# VNA.net
KiCad netlist of a schematic drawn in EAGLE
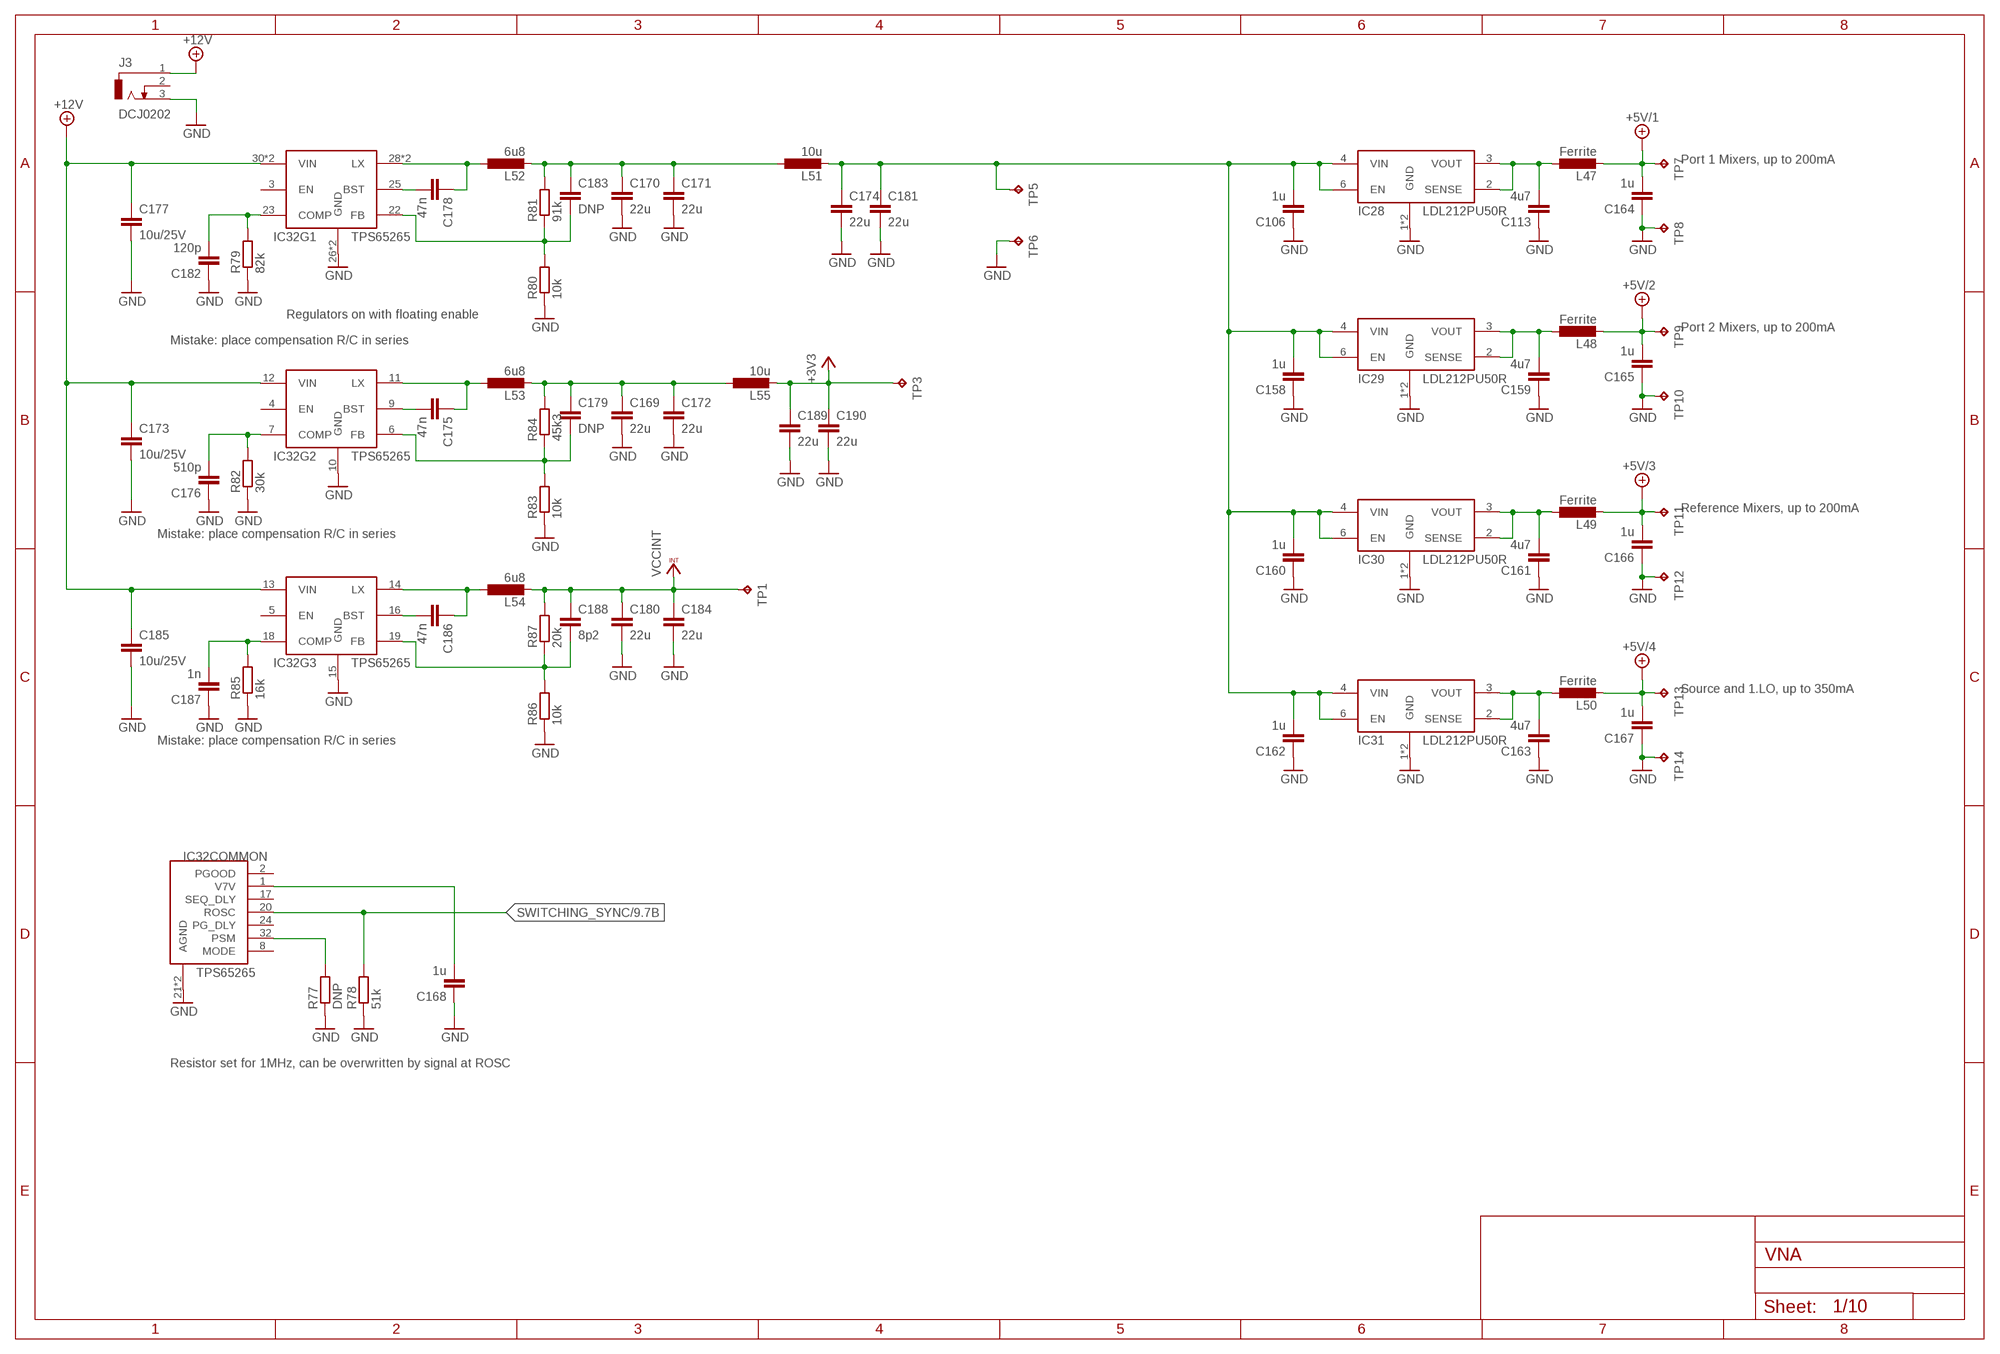
[diagram p0: schematic, sheet 1]
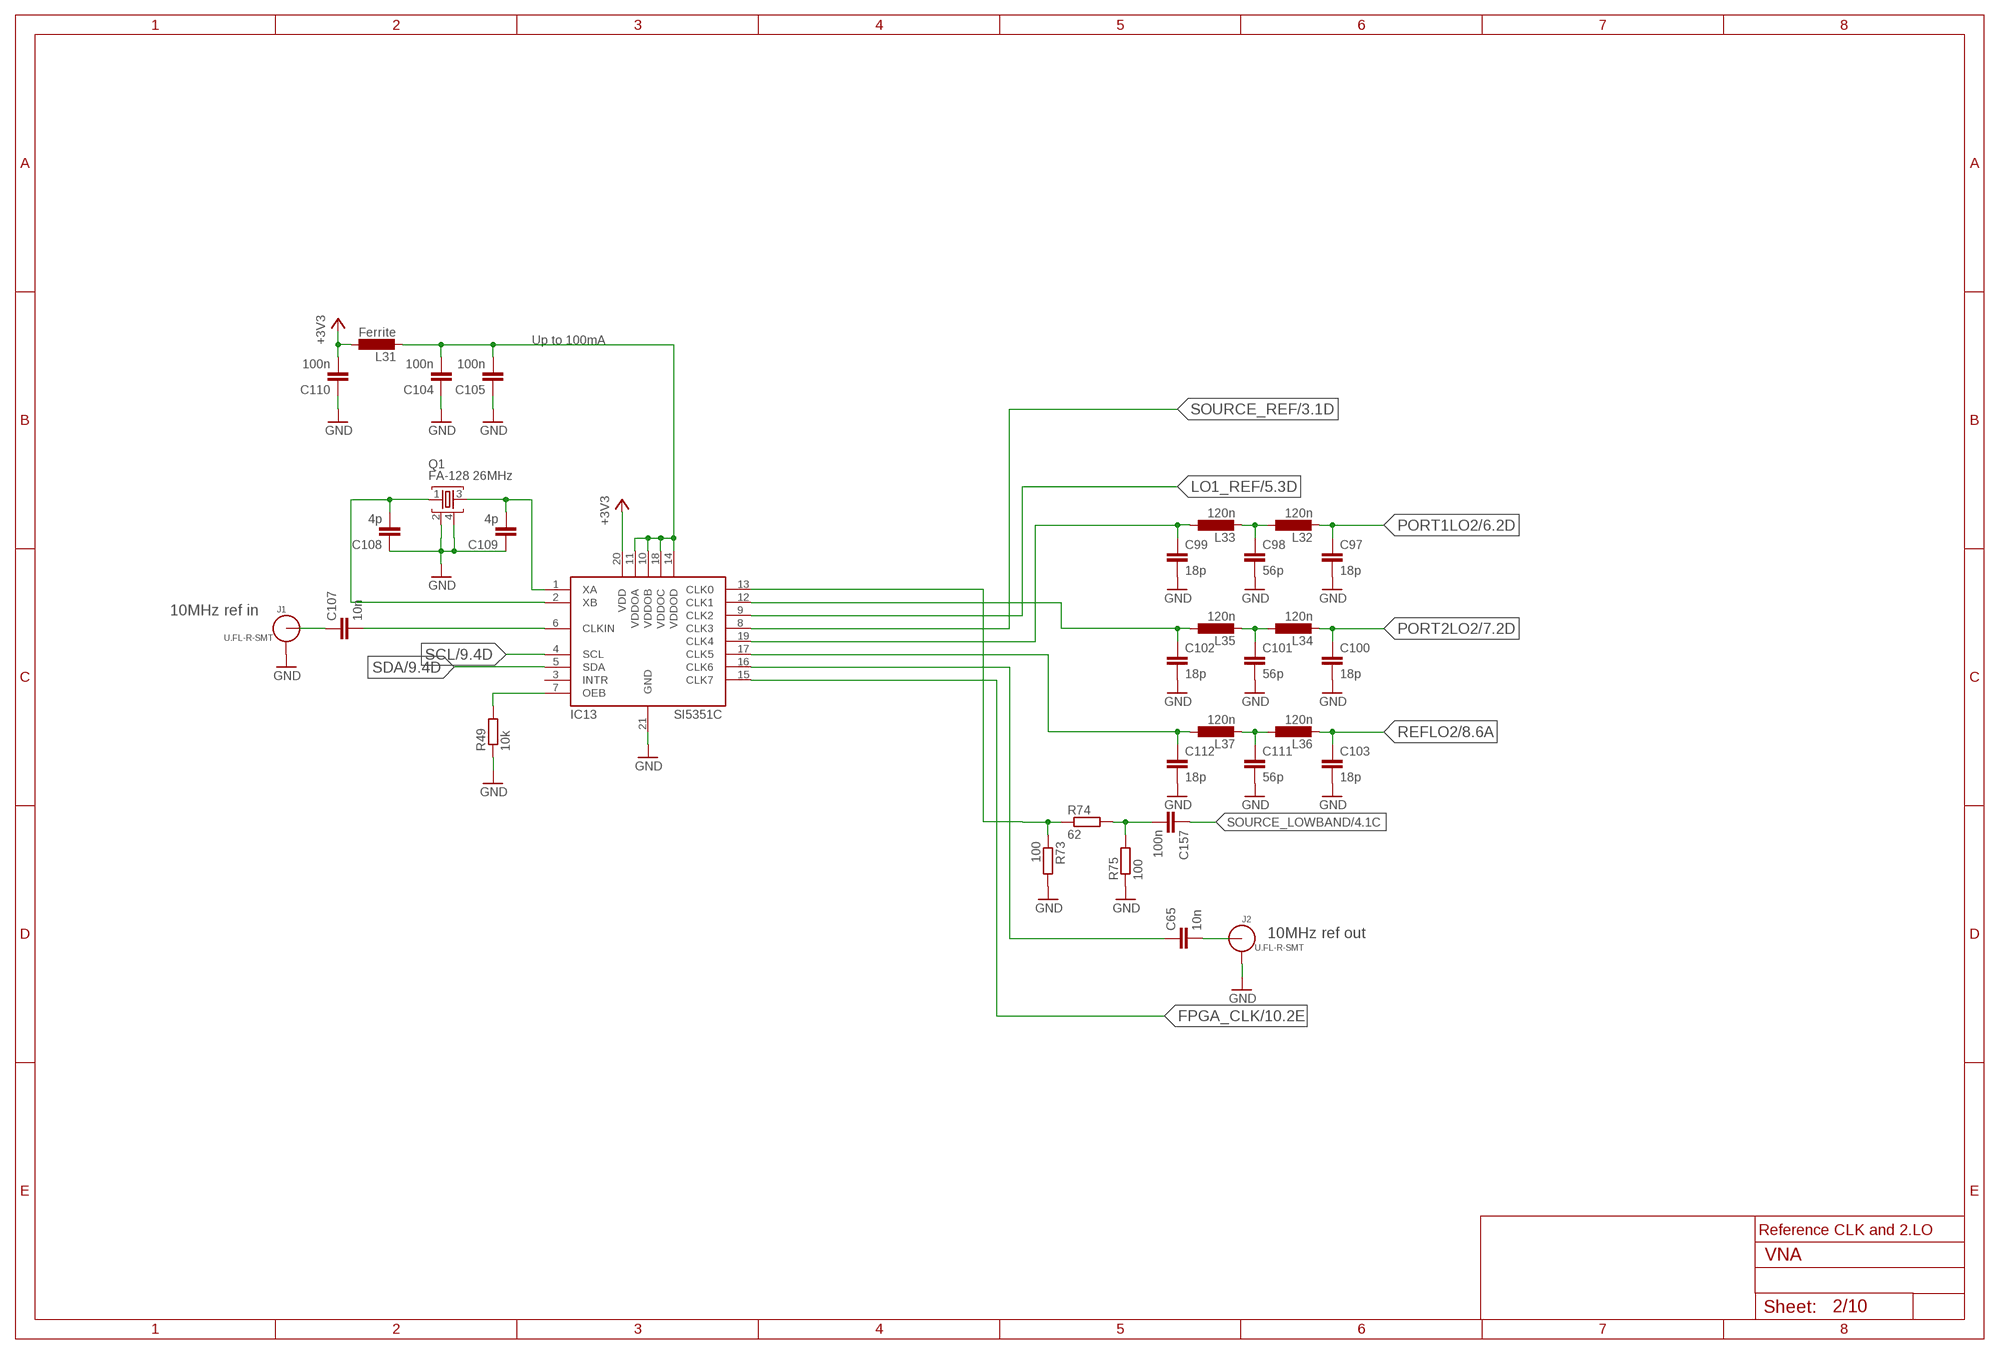
[diagram p1: schematic, sheet 2]
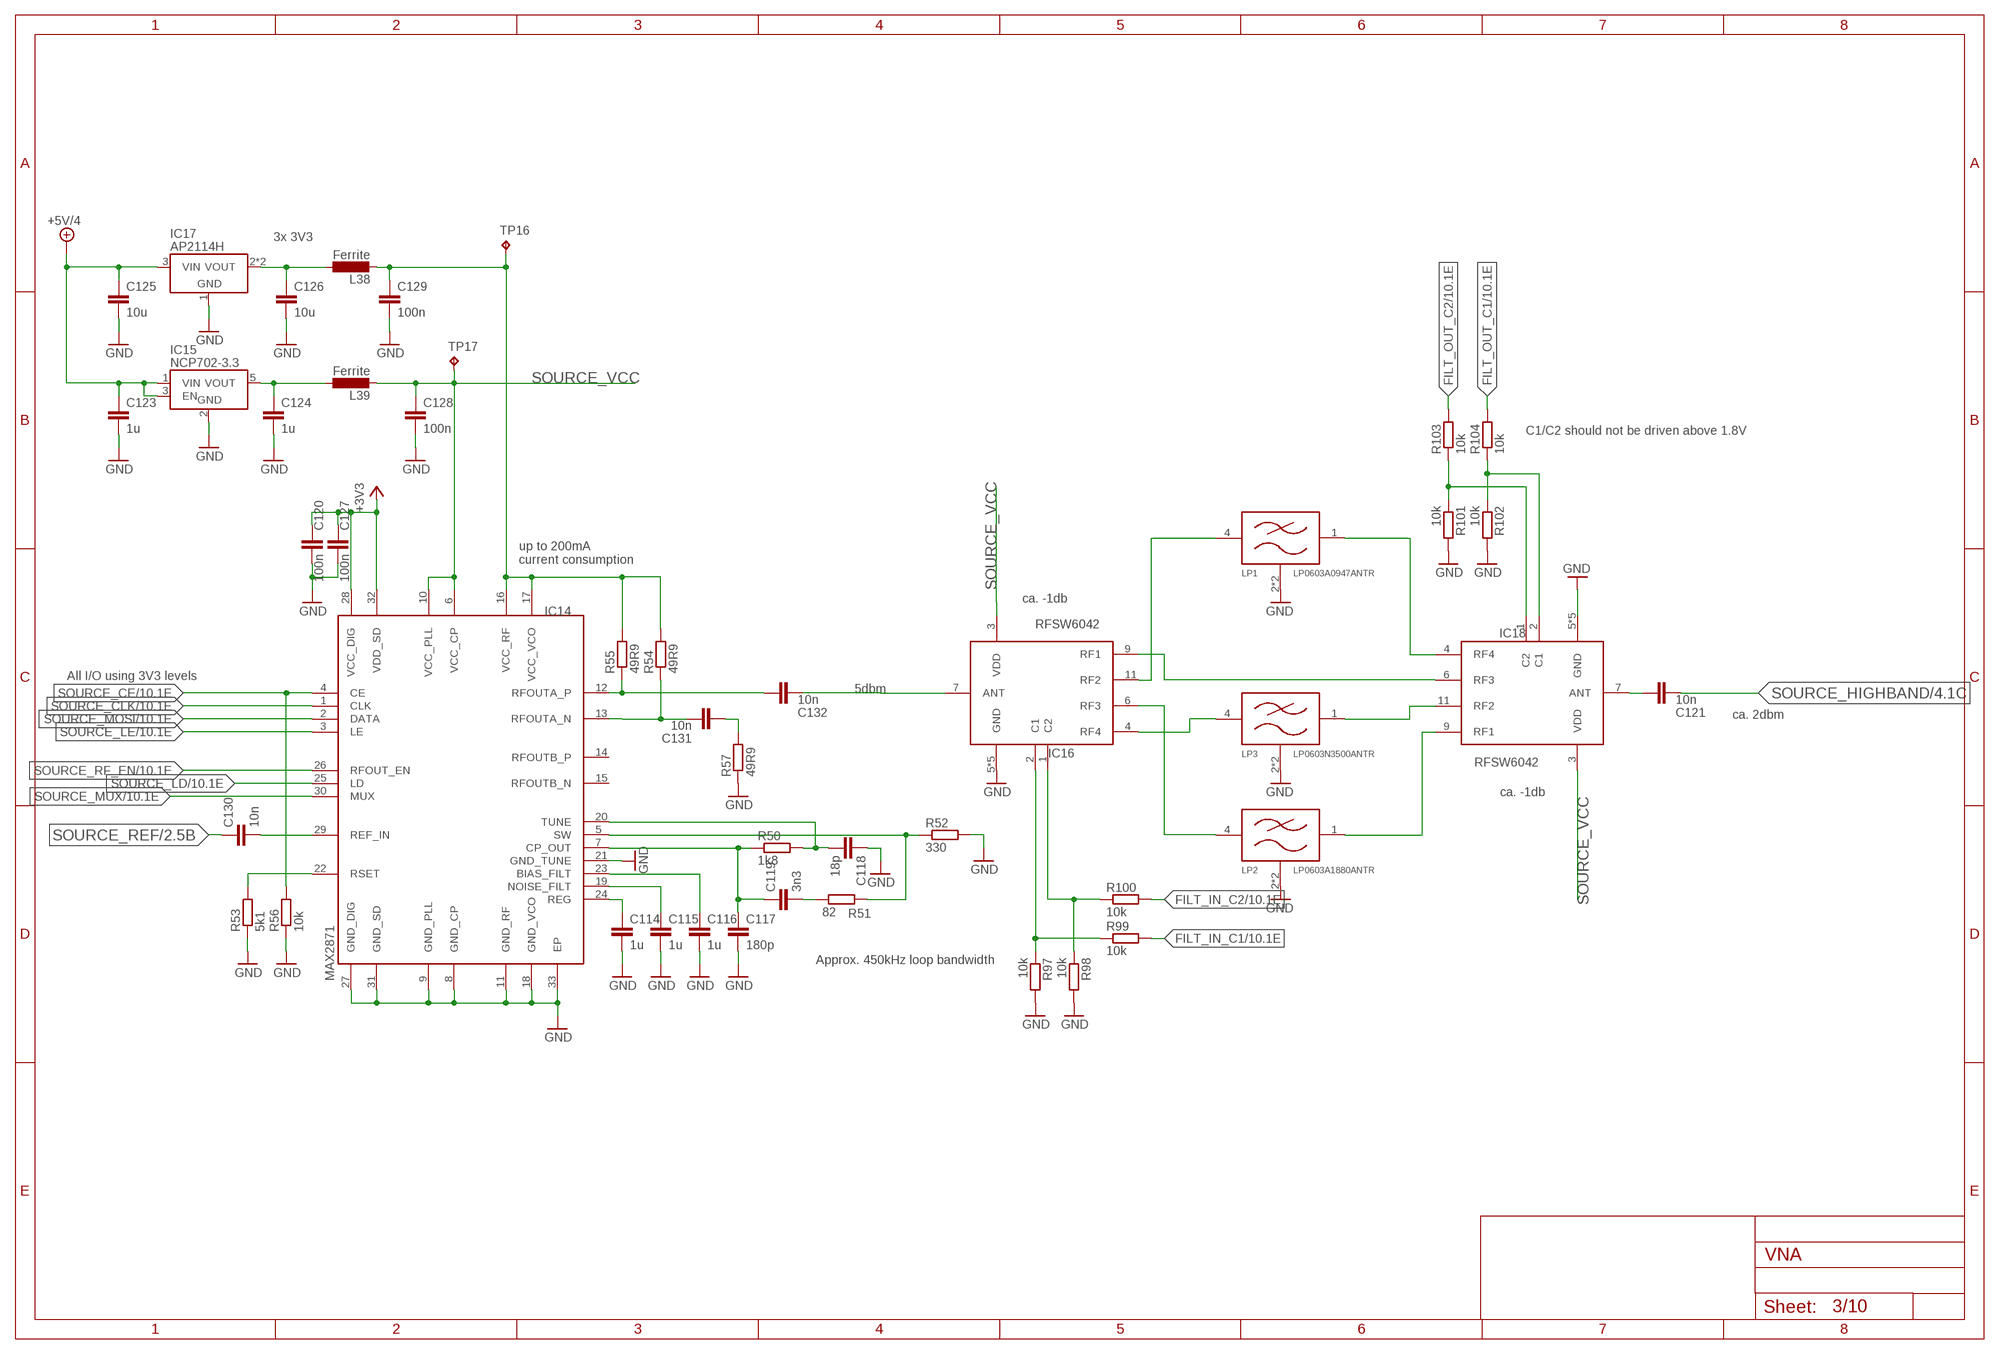
[diagram p2: schematic, sheet 3]
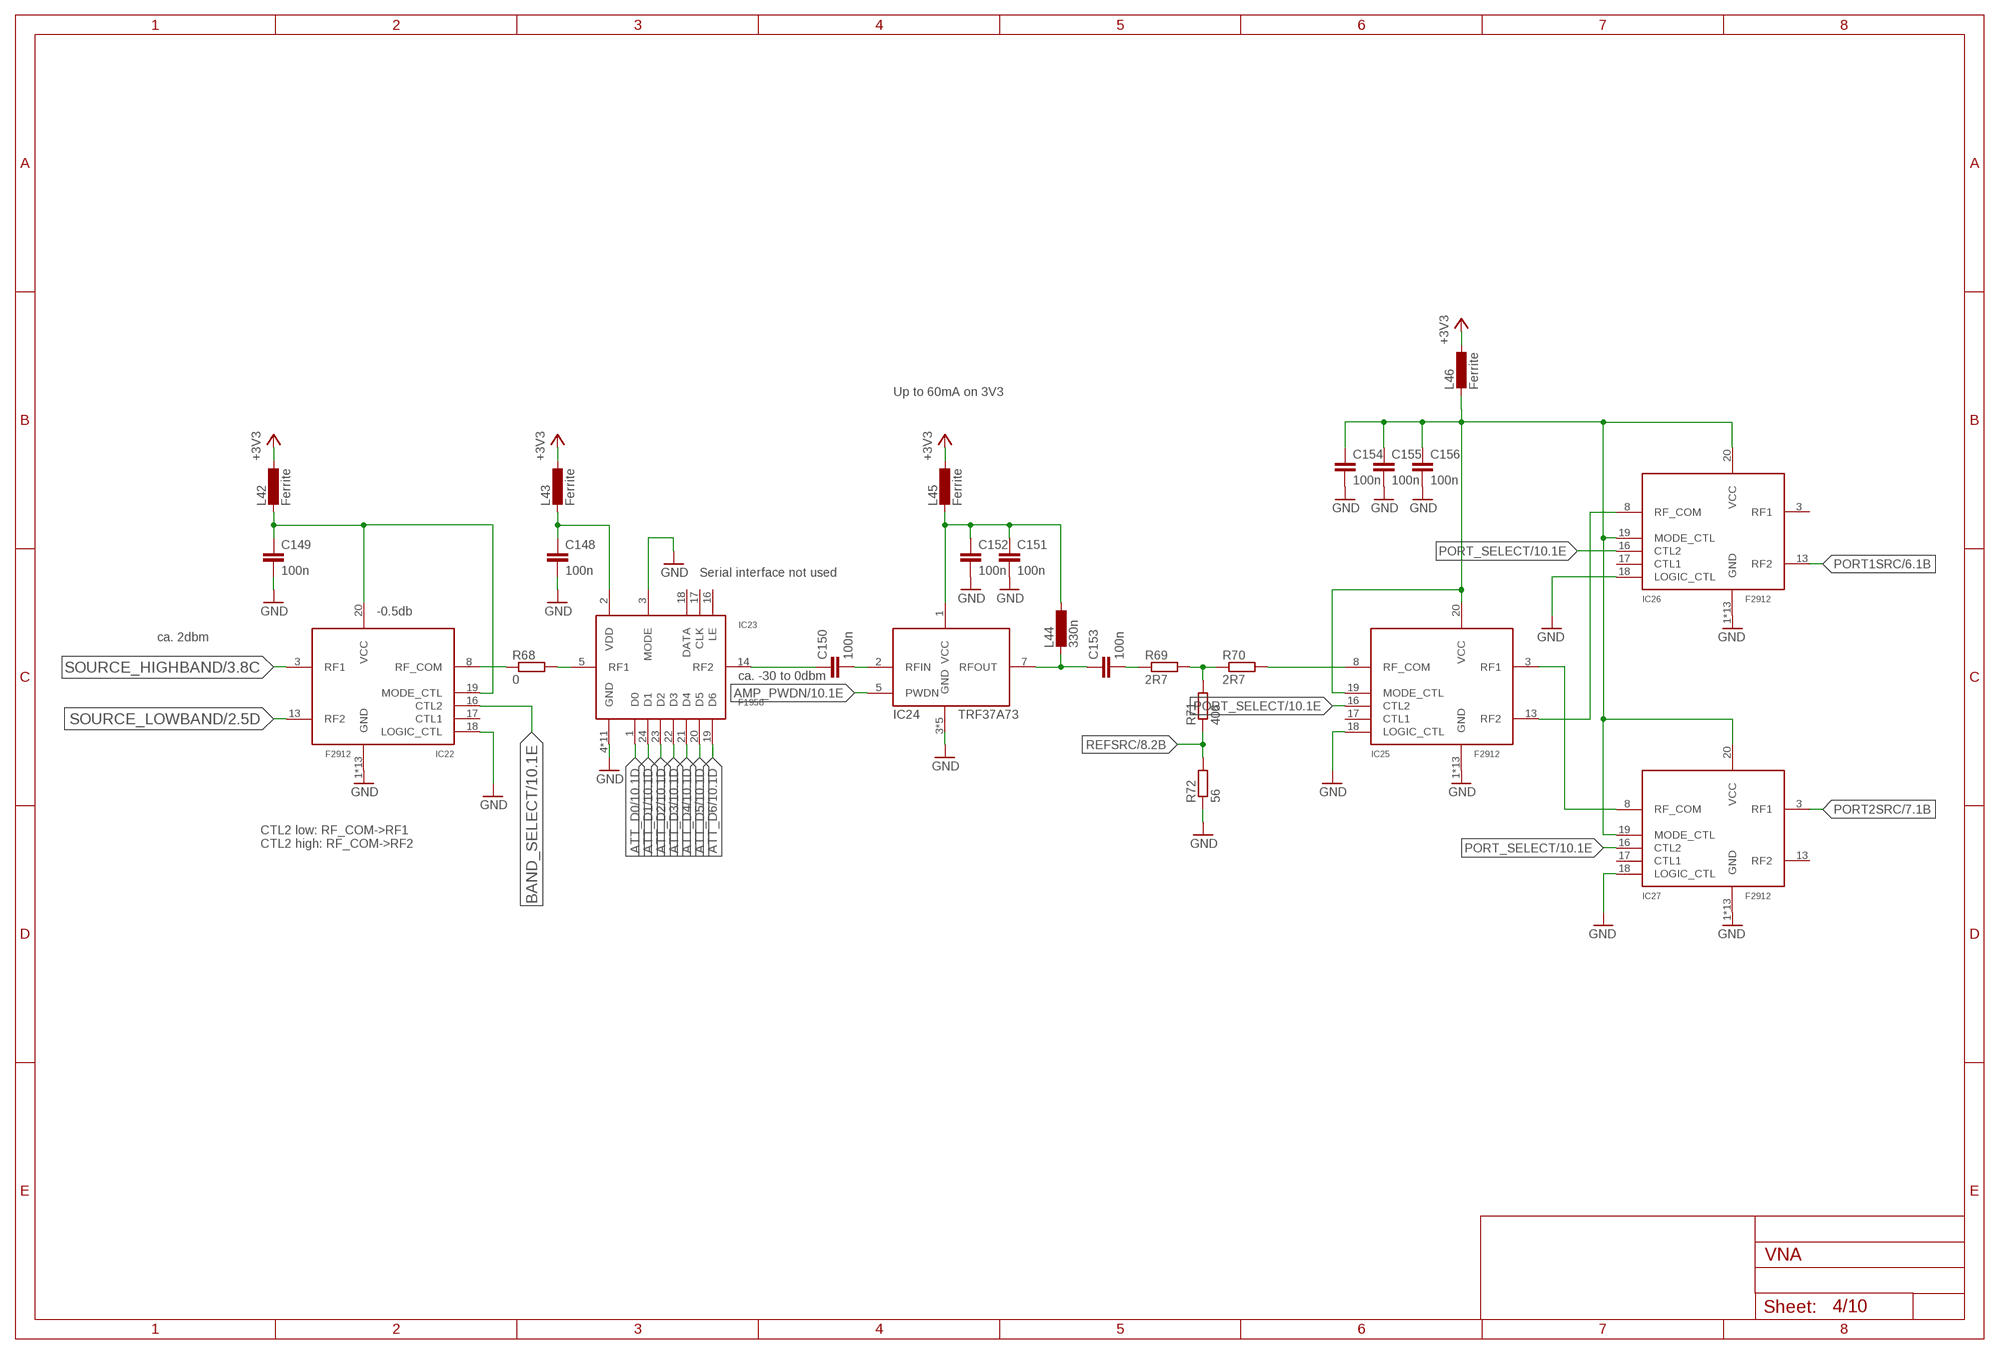
[diagram p3: schematic, sheet 4]
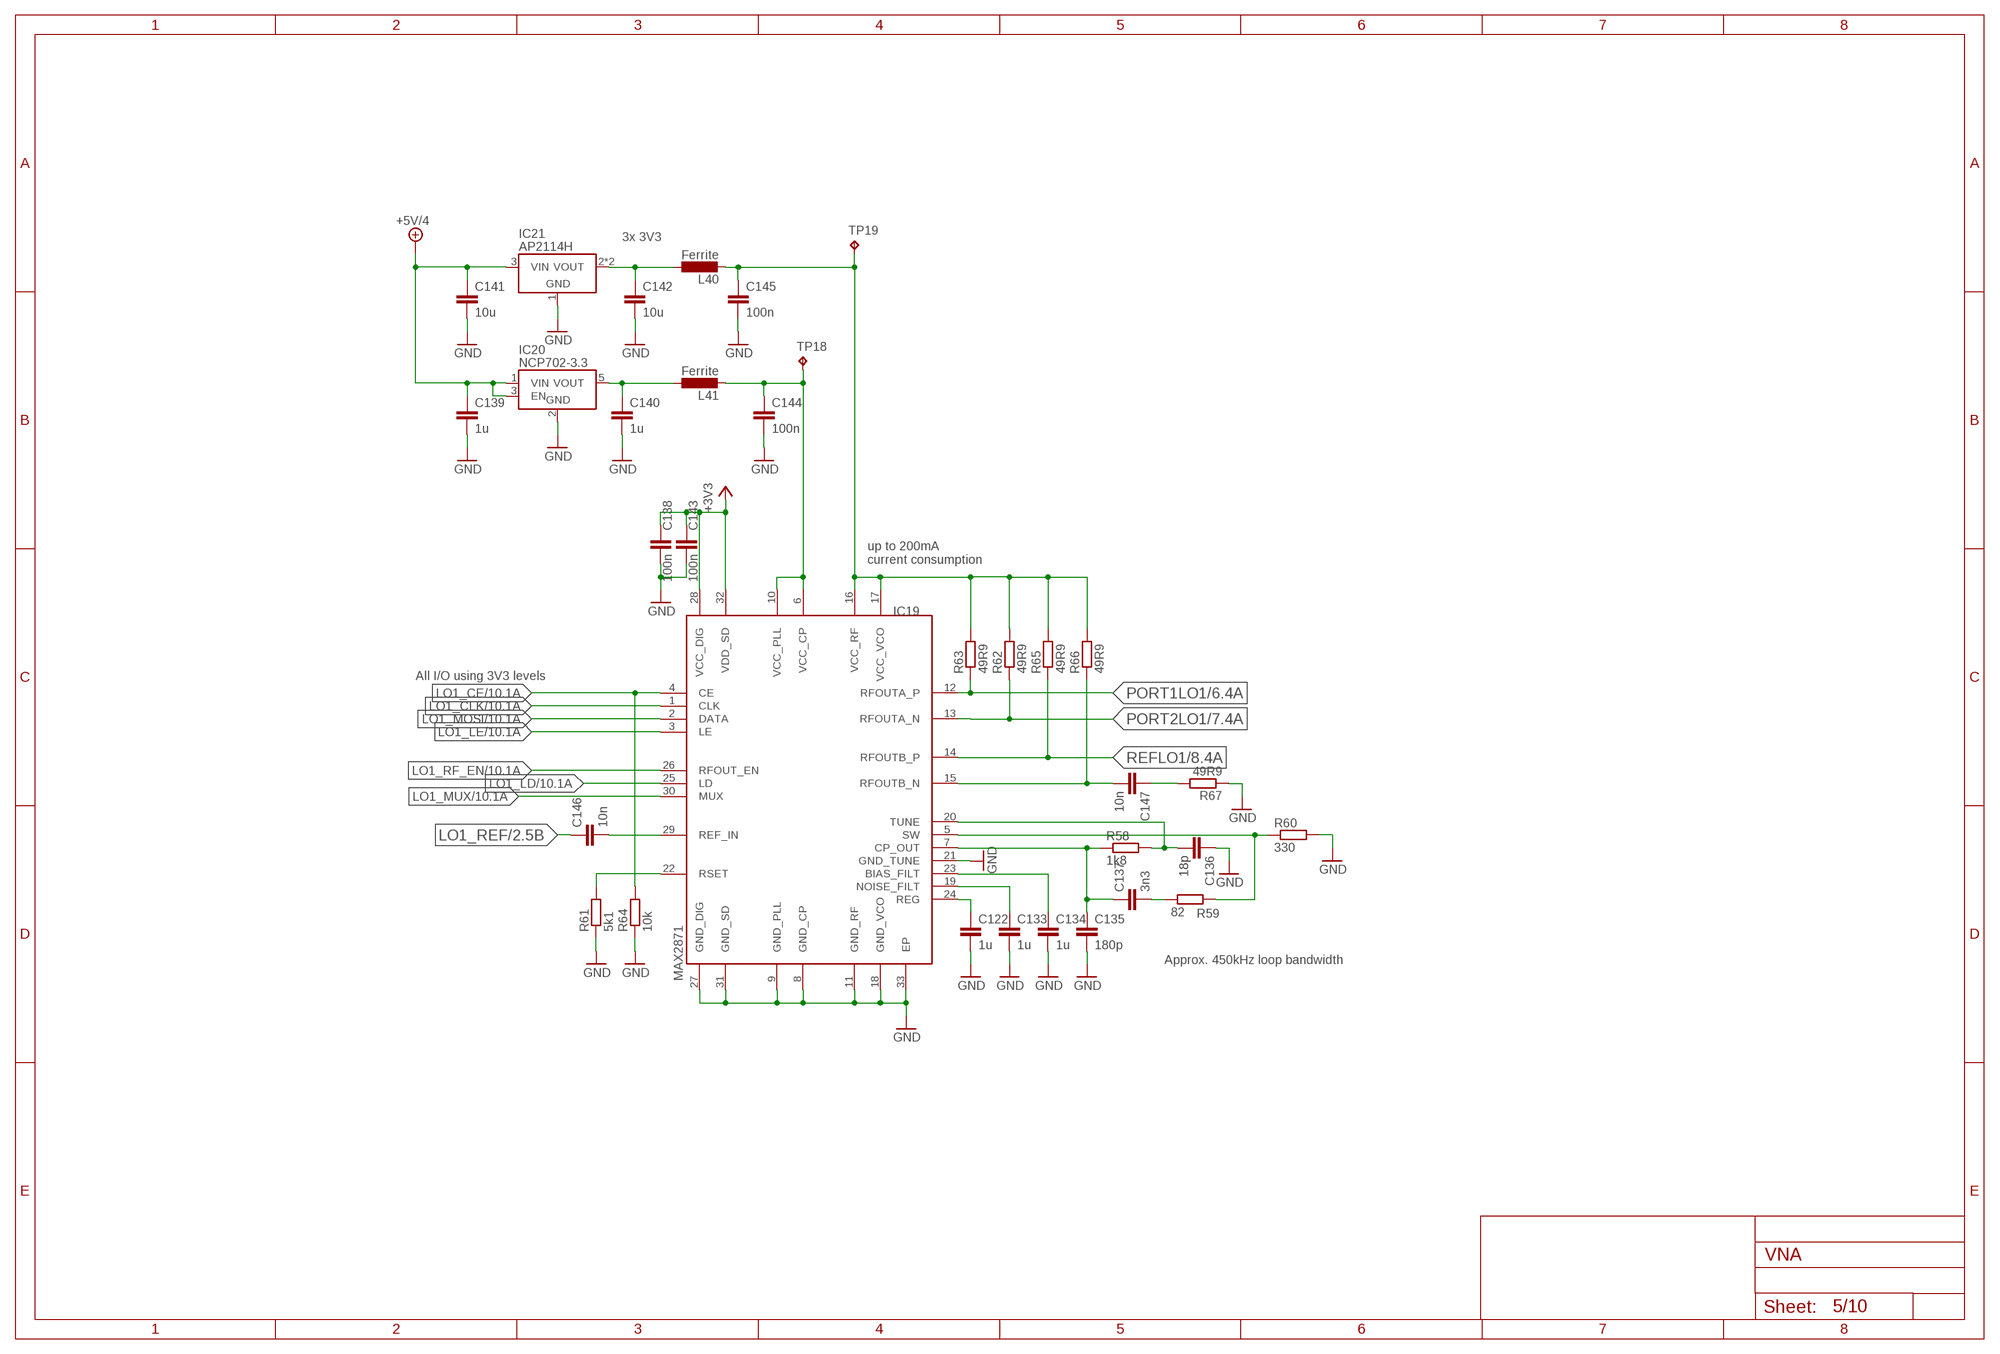
[diagram p4: schematic, sheet 5]
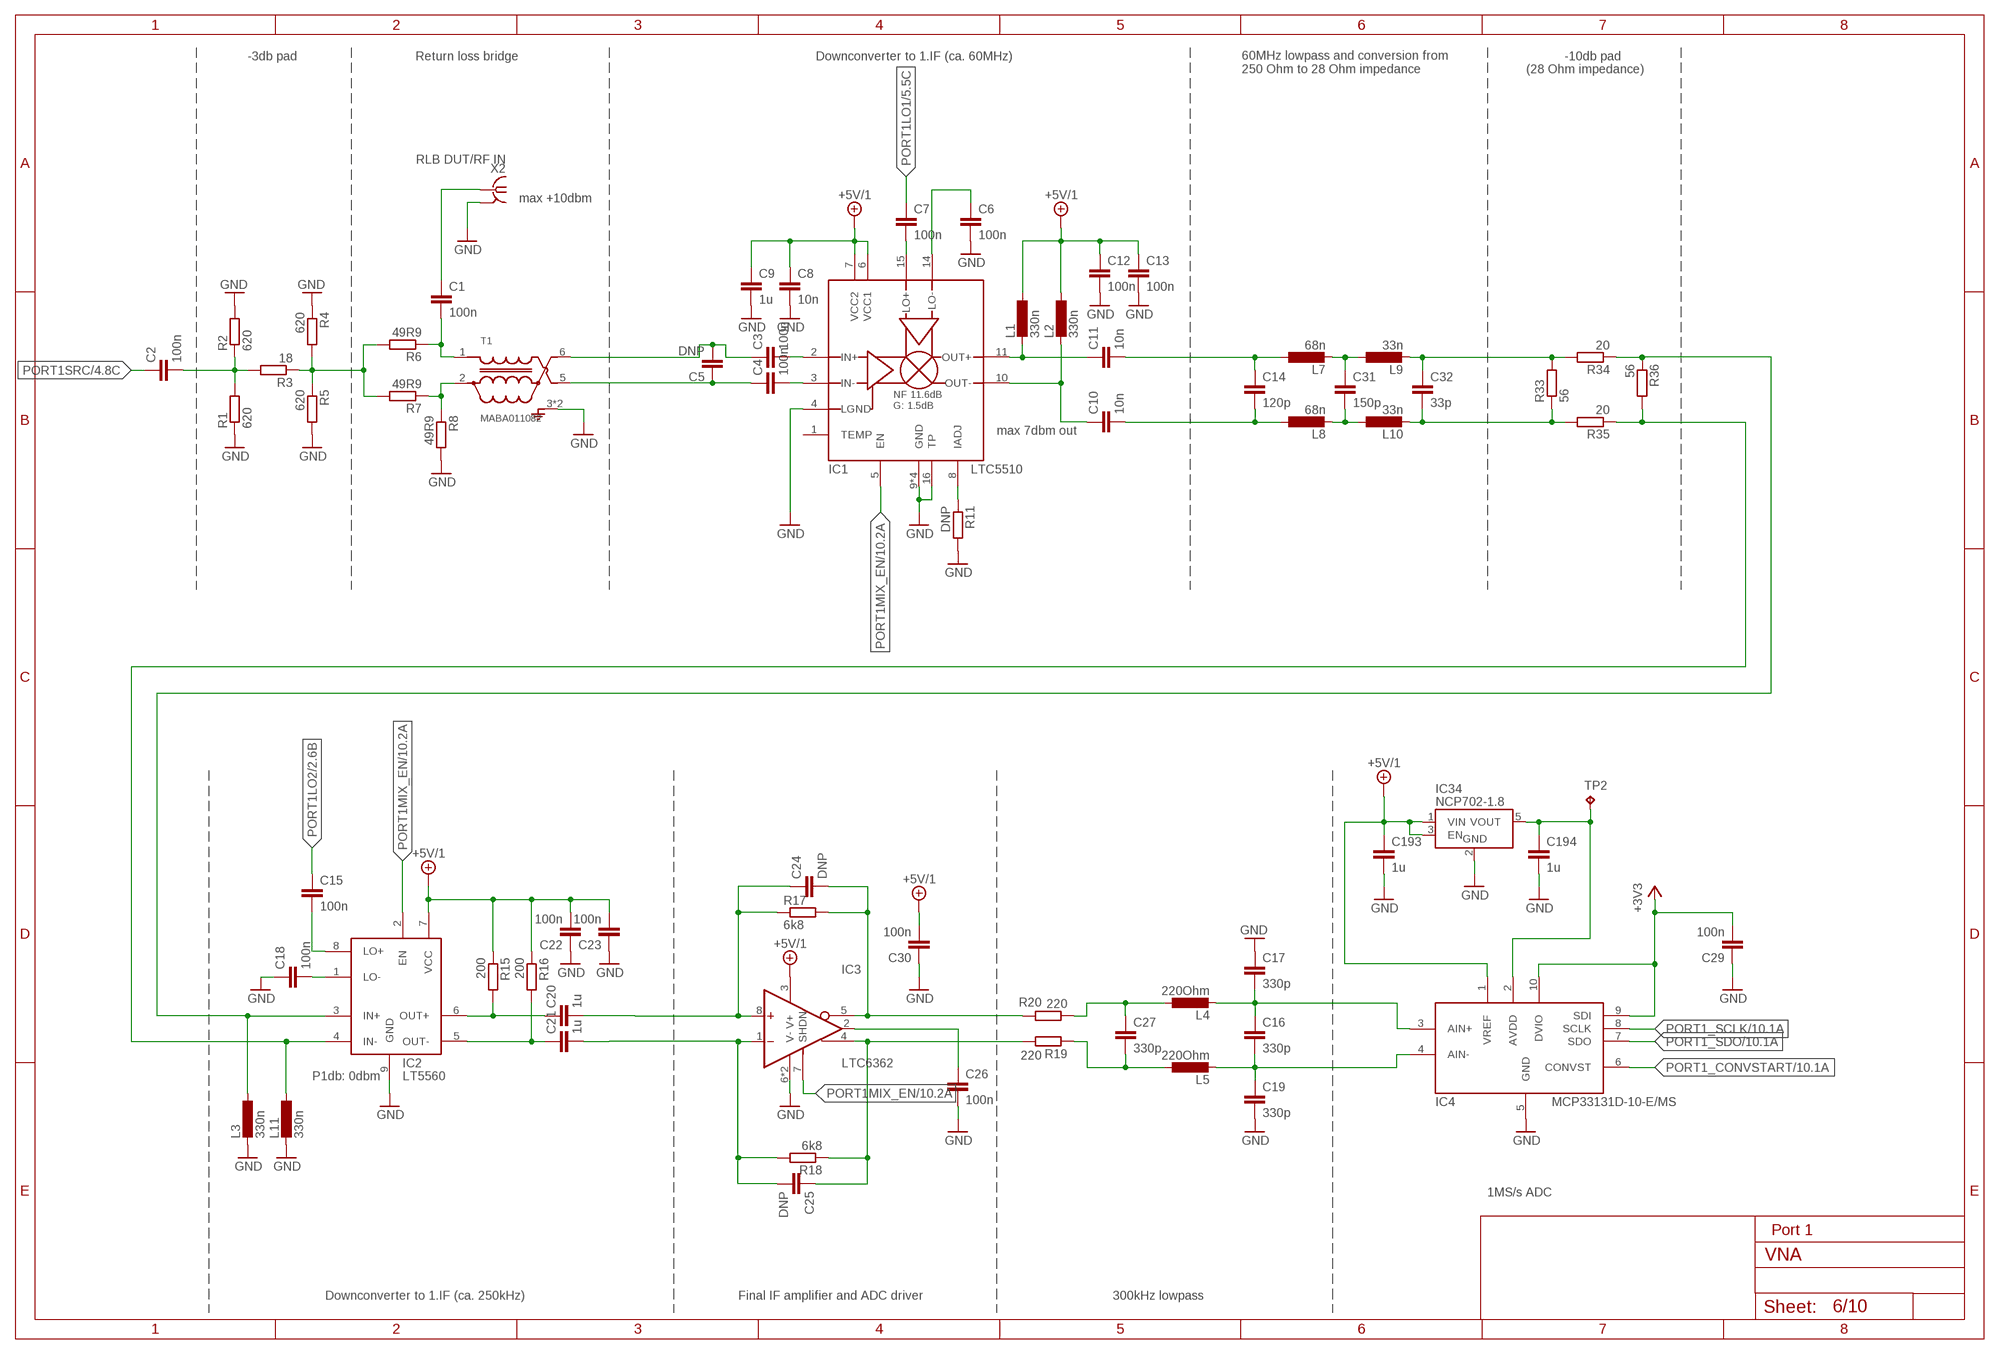
[diagram p5: schematic, sheet 6]
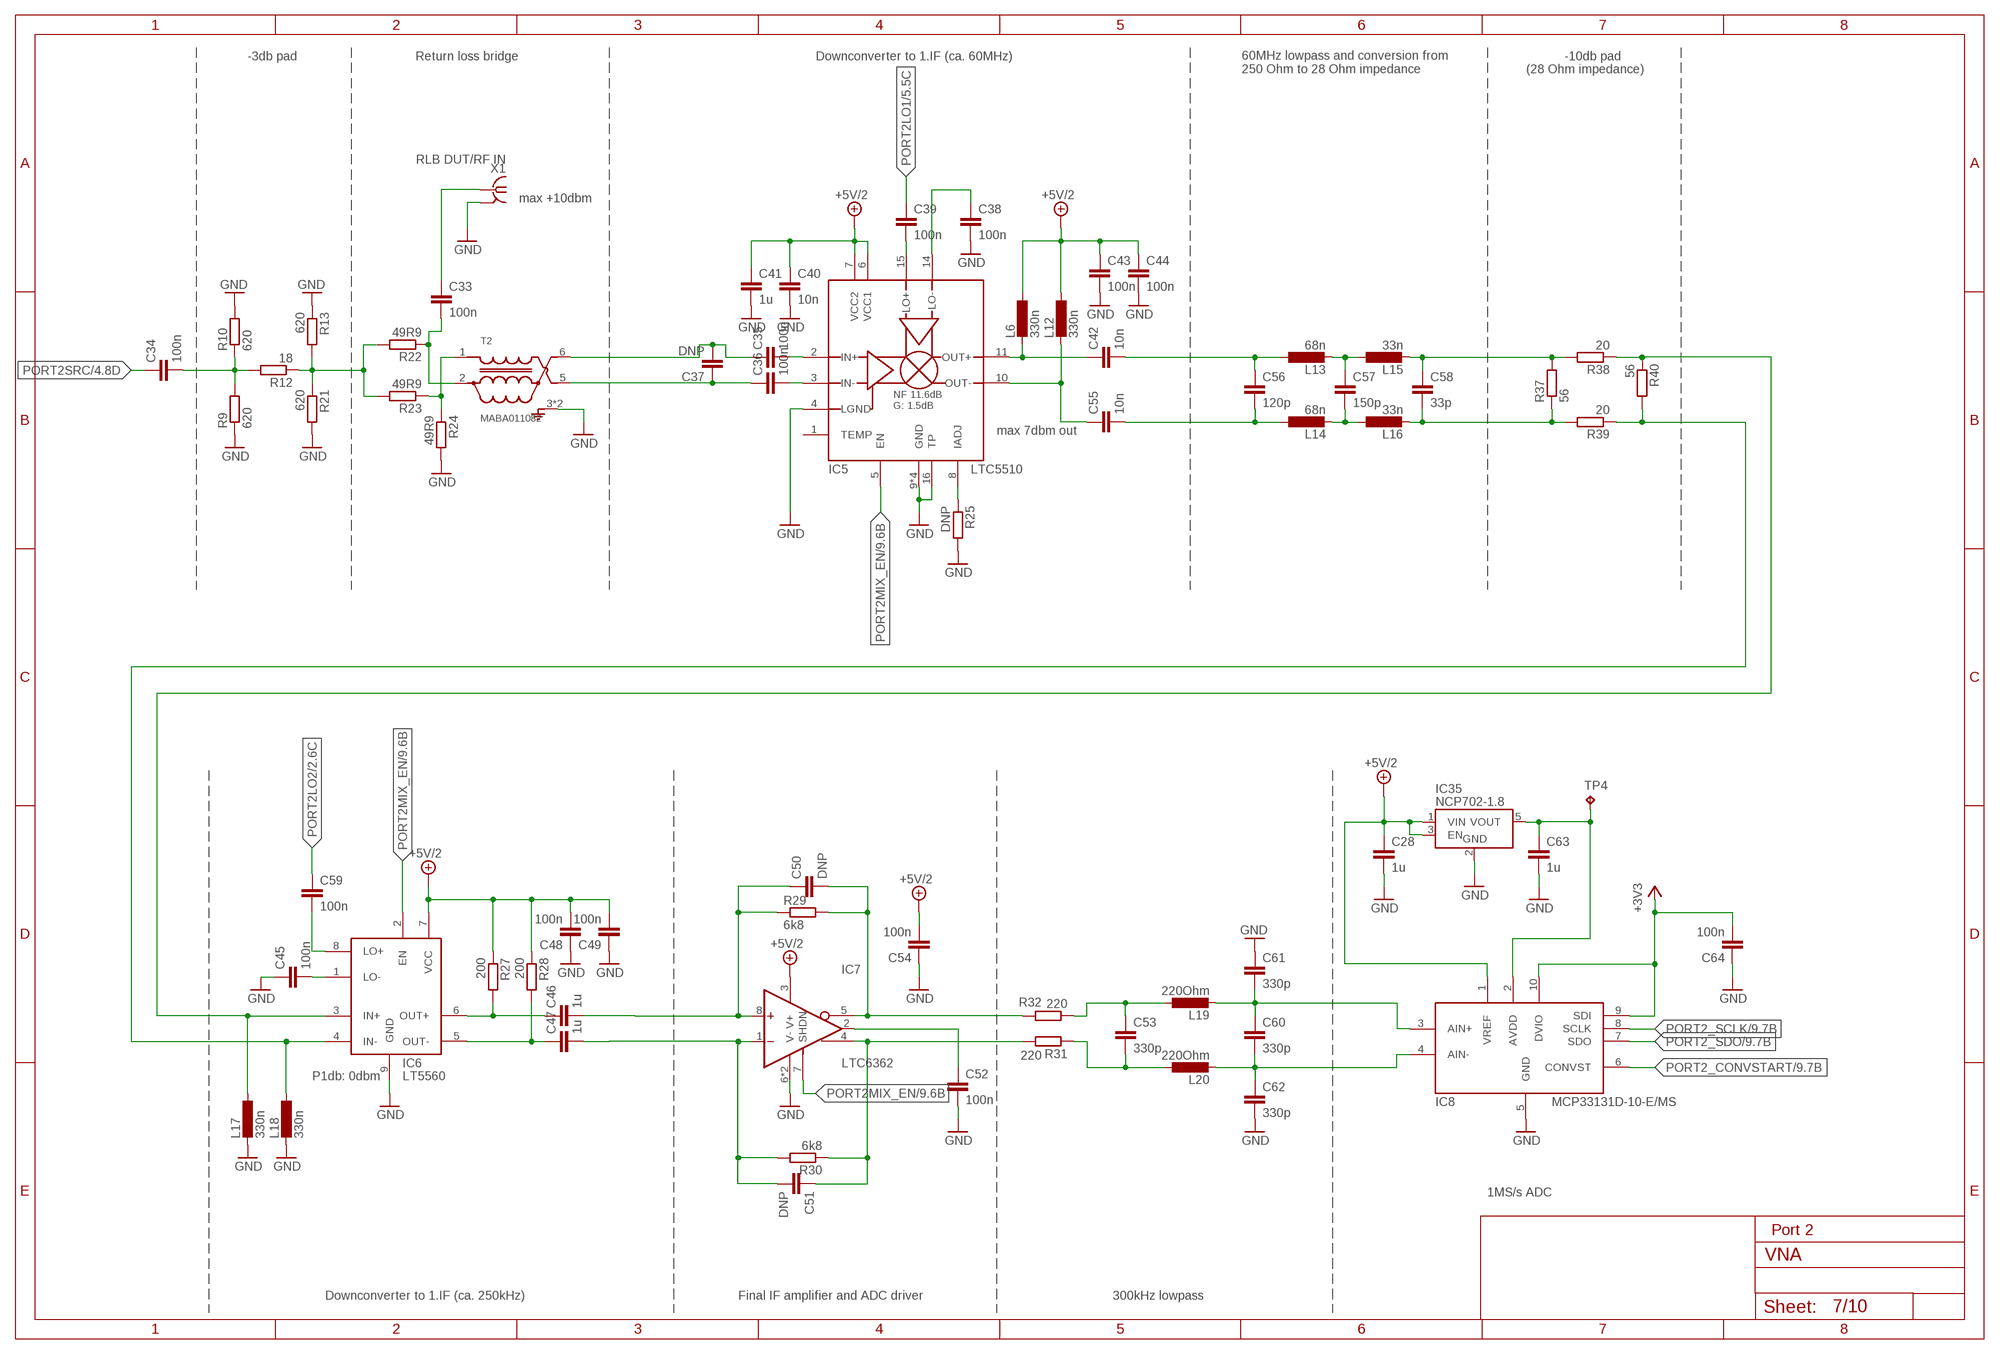
[diagram p6: schematic, sheet 7]
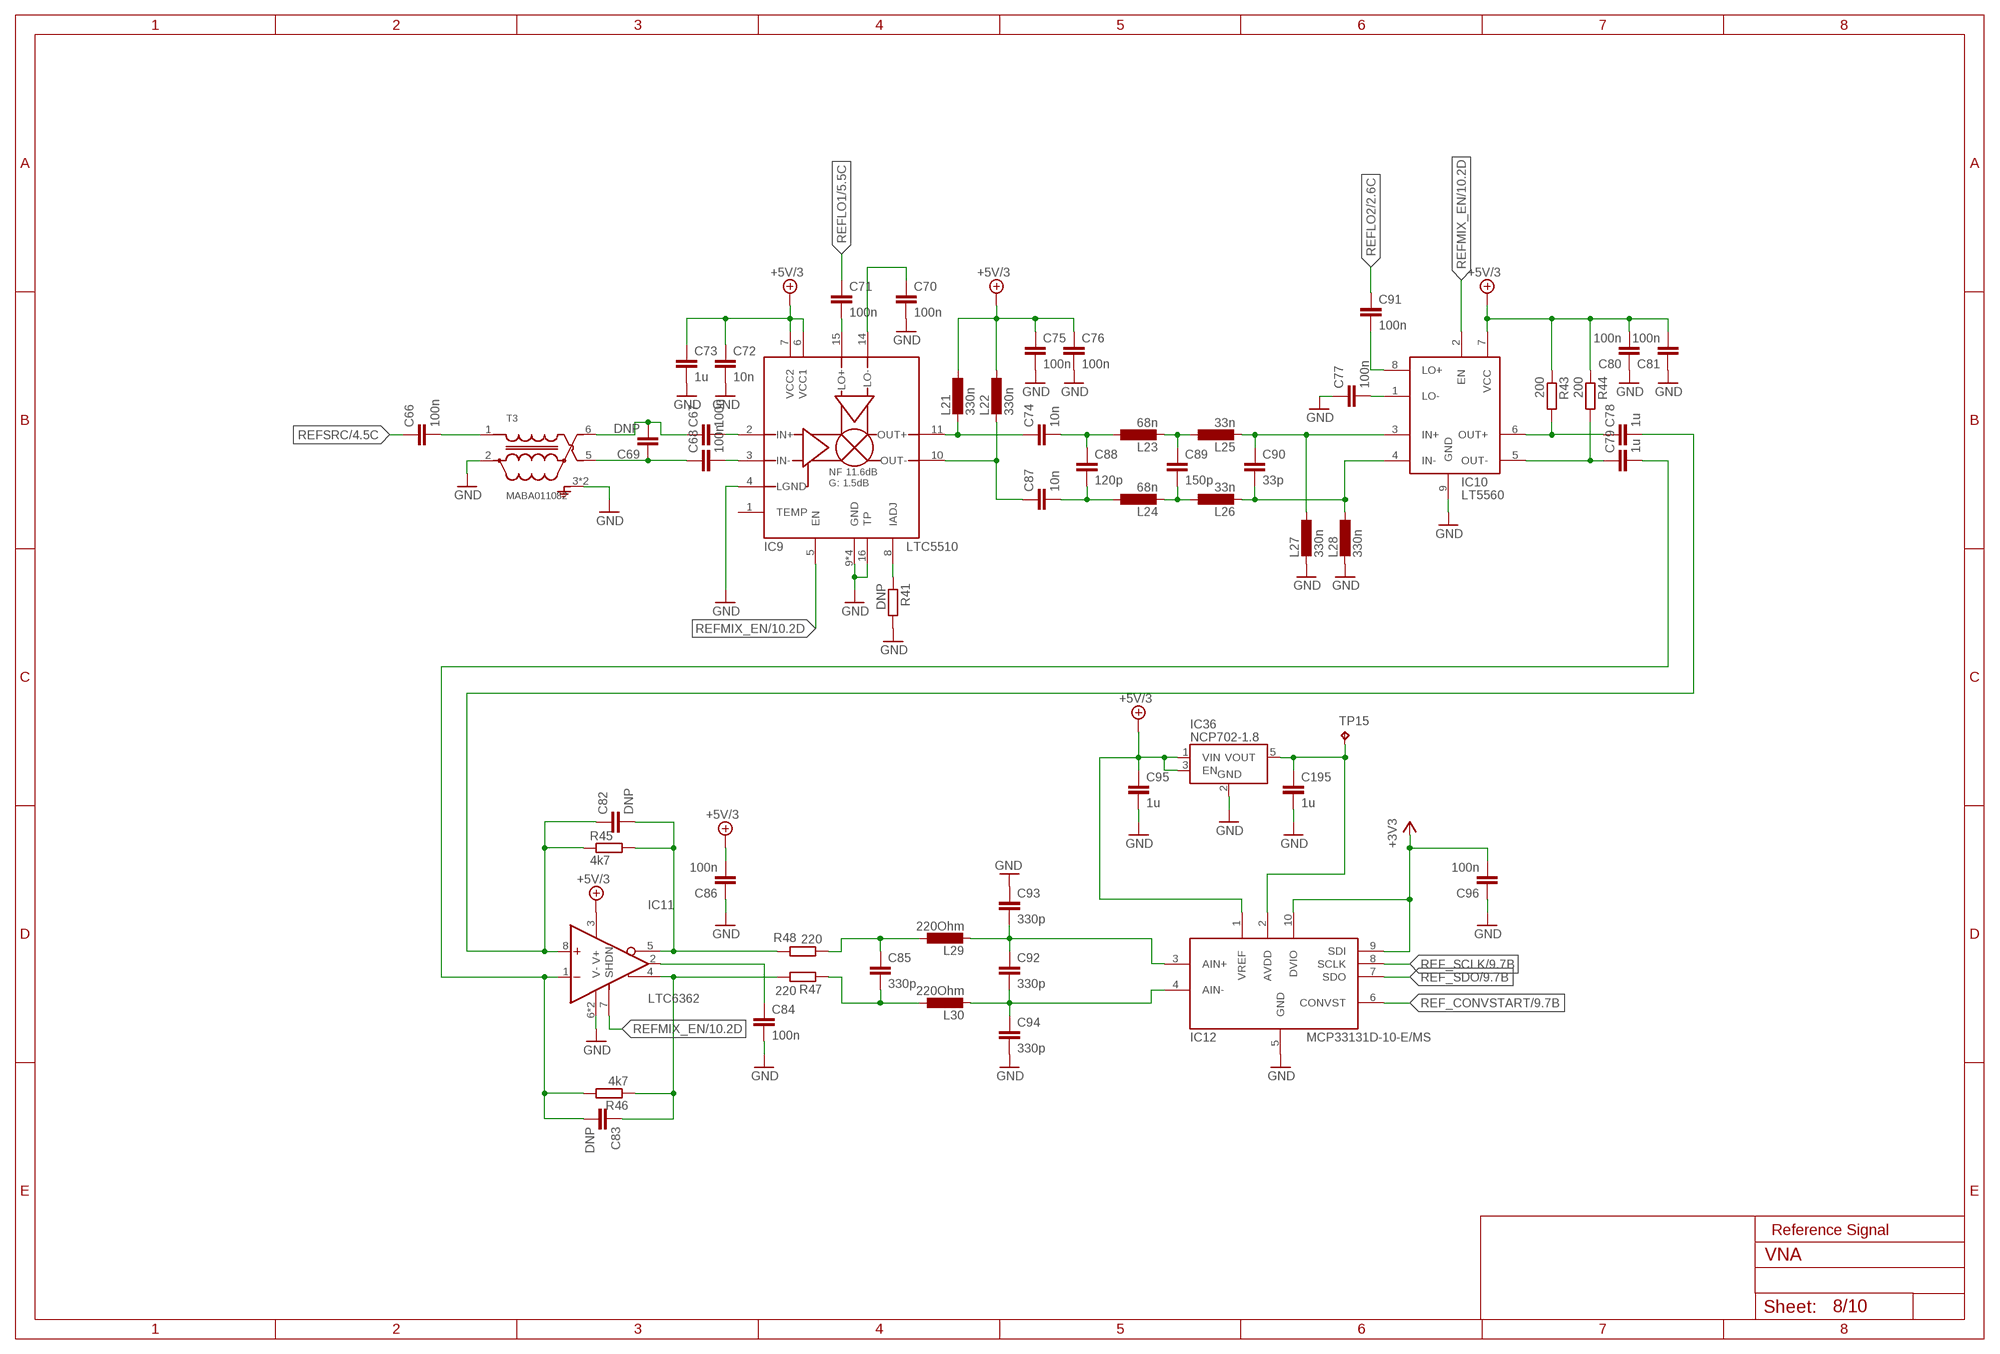
[diagram p7: schematic, sheet 8]
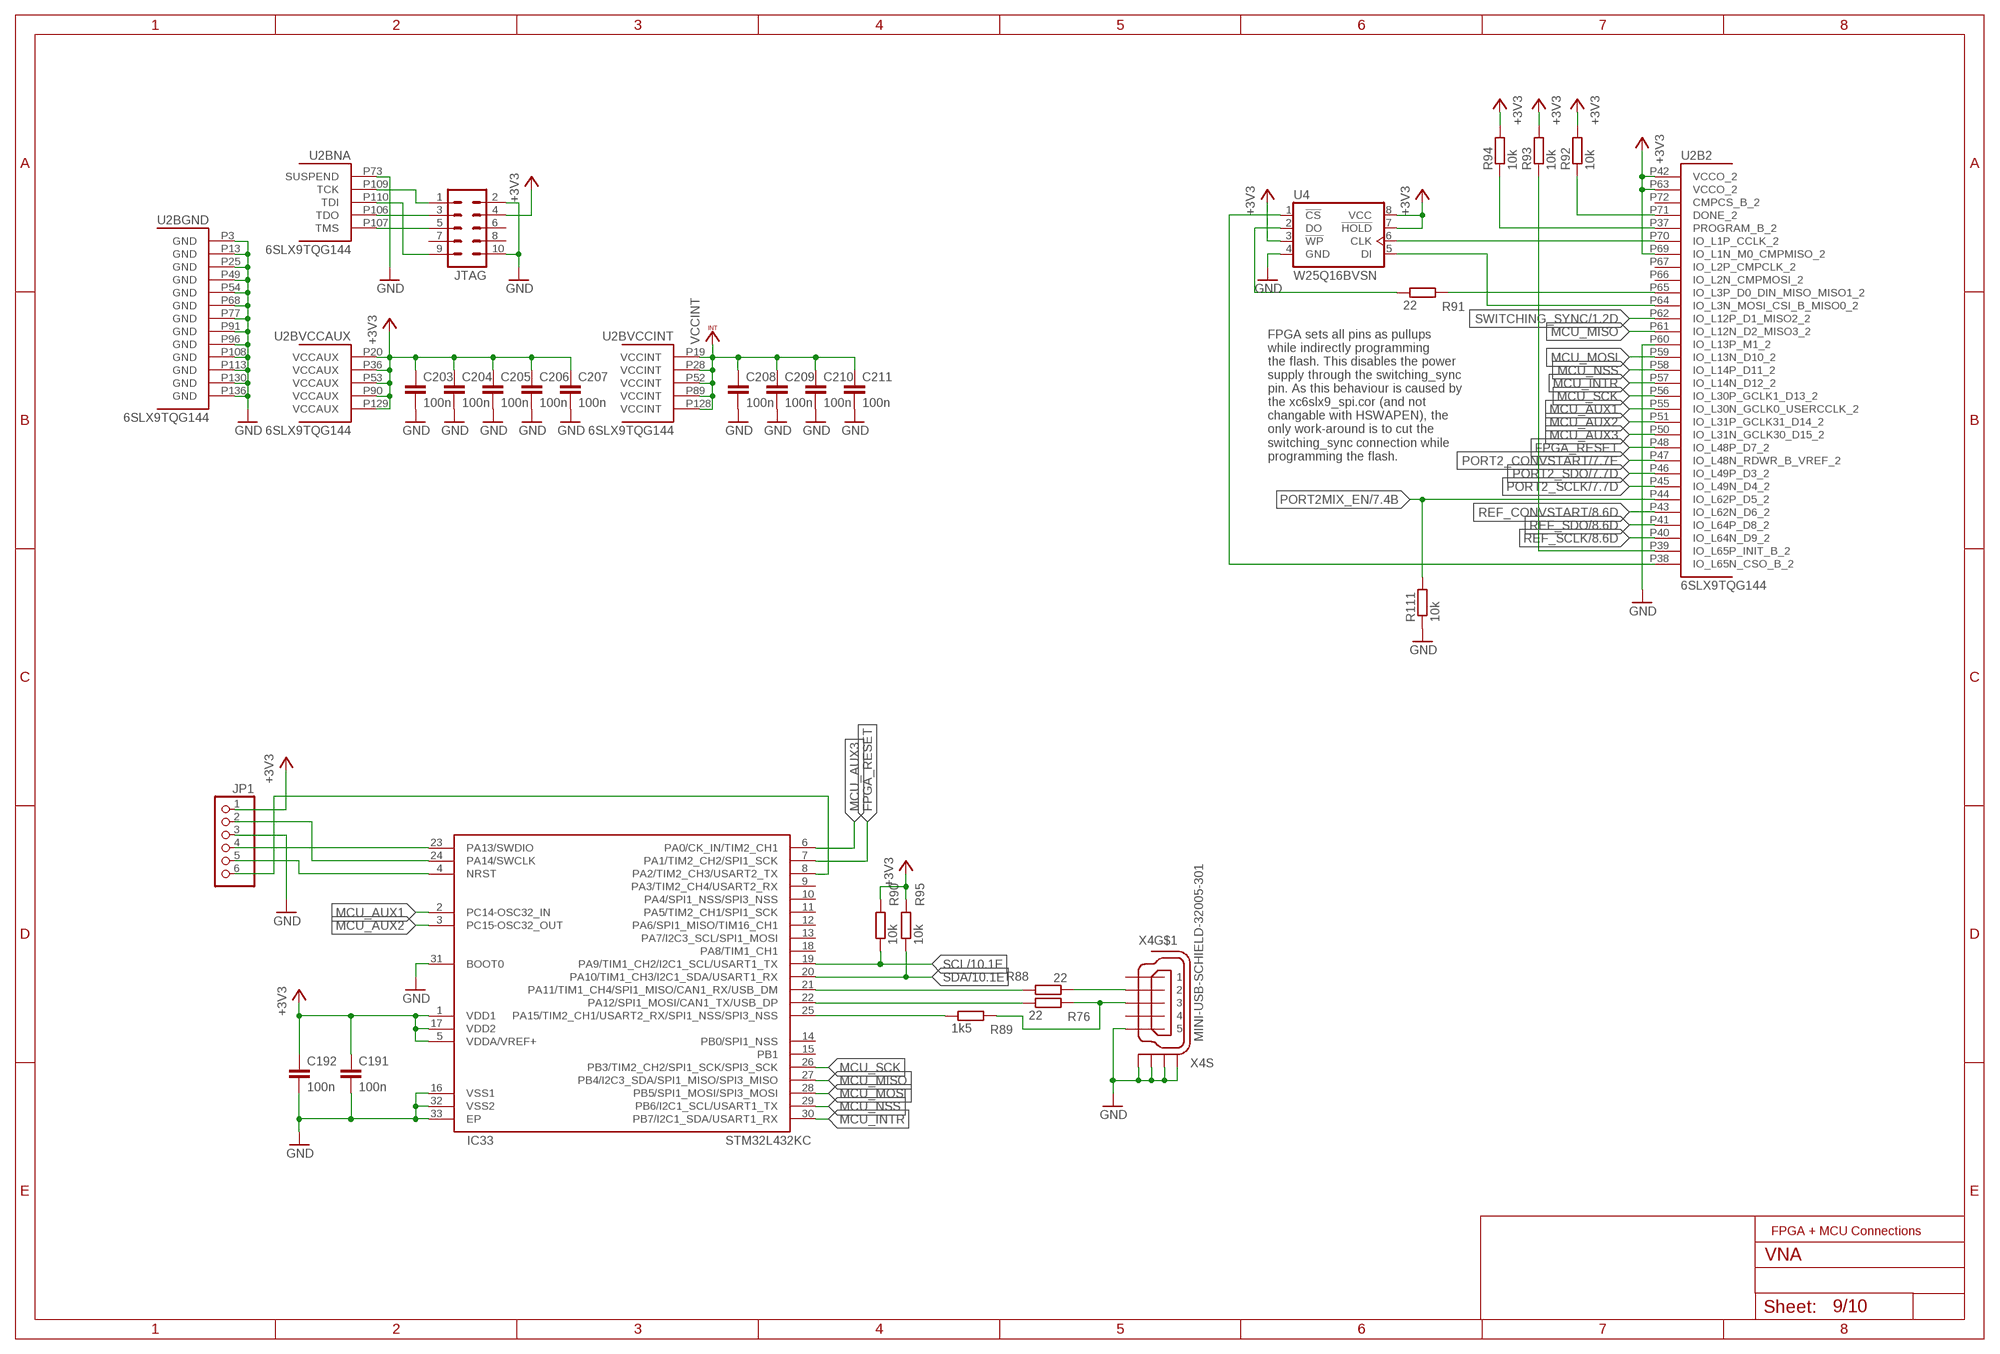
[diagram p8: schematic, sheet 9]
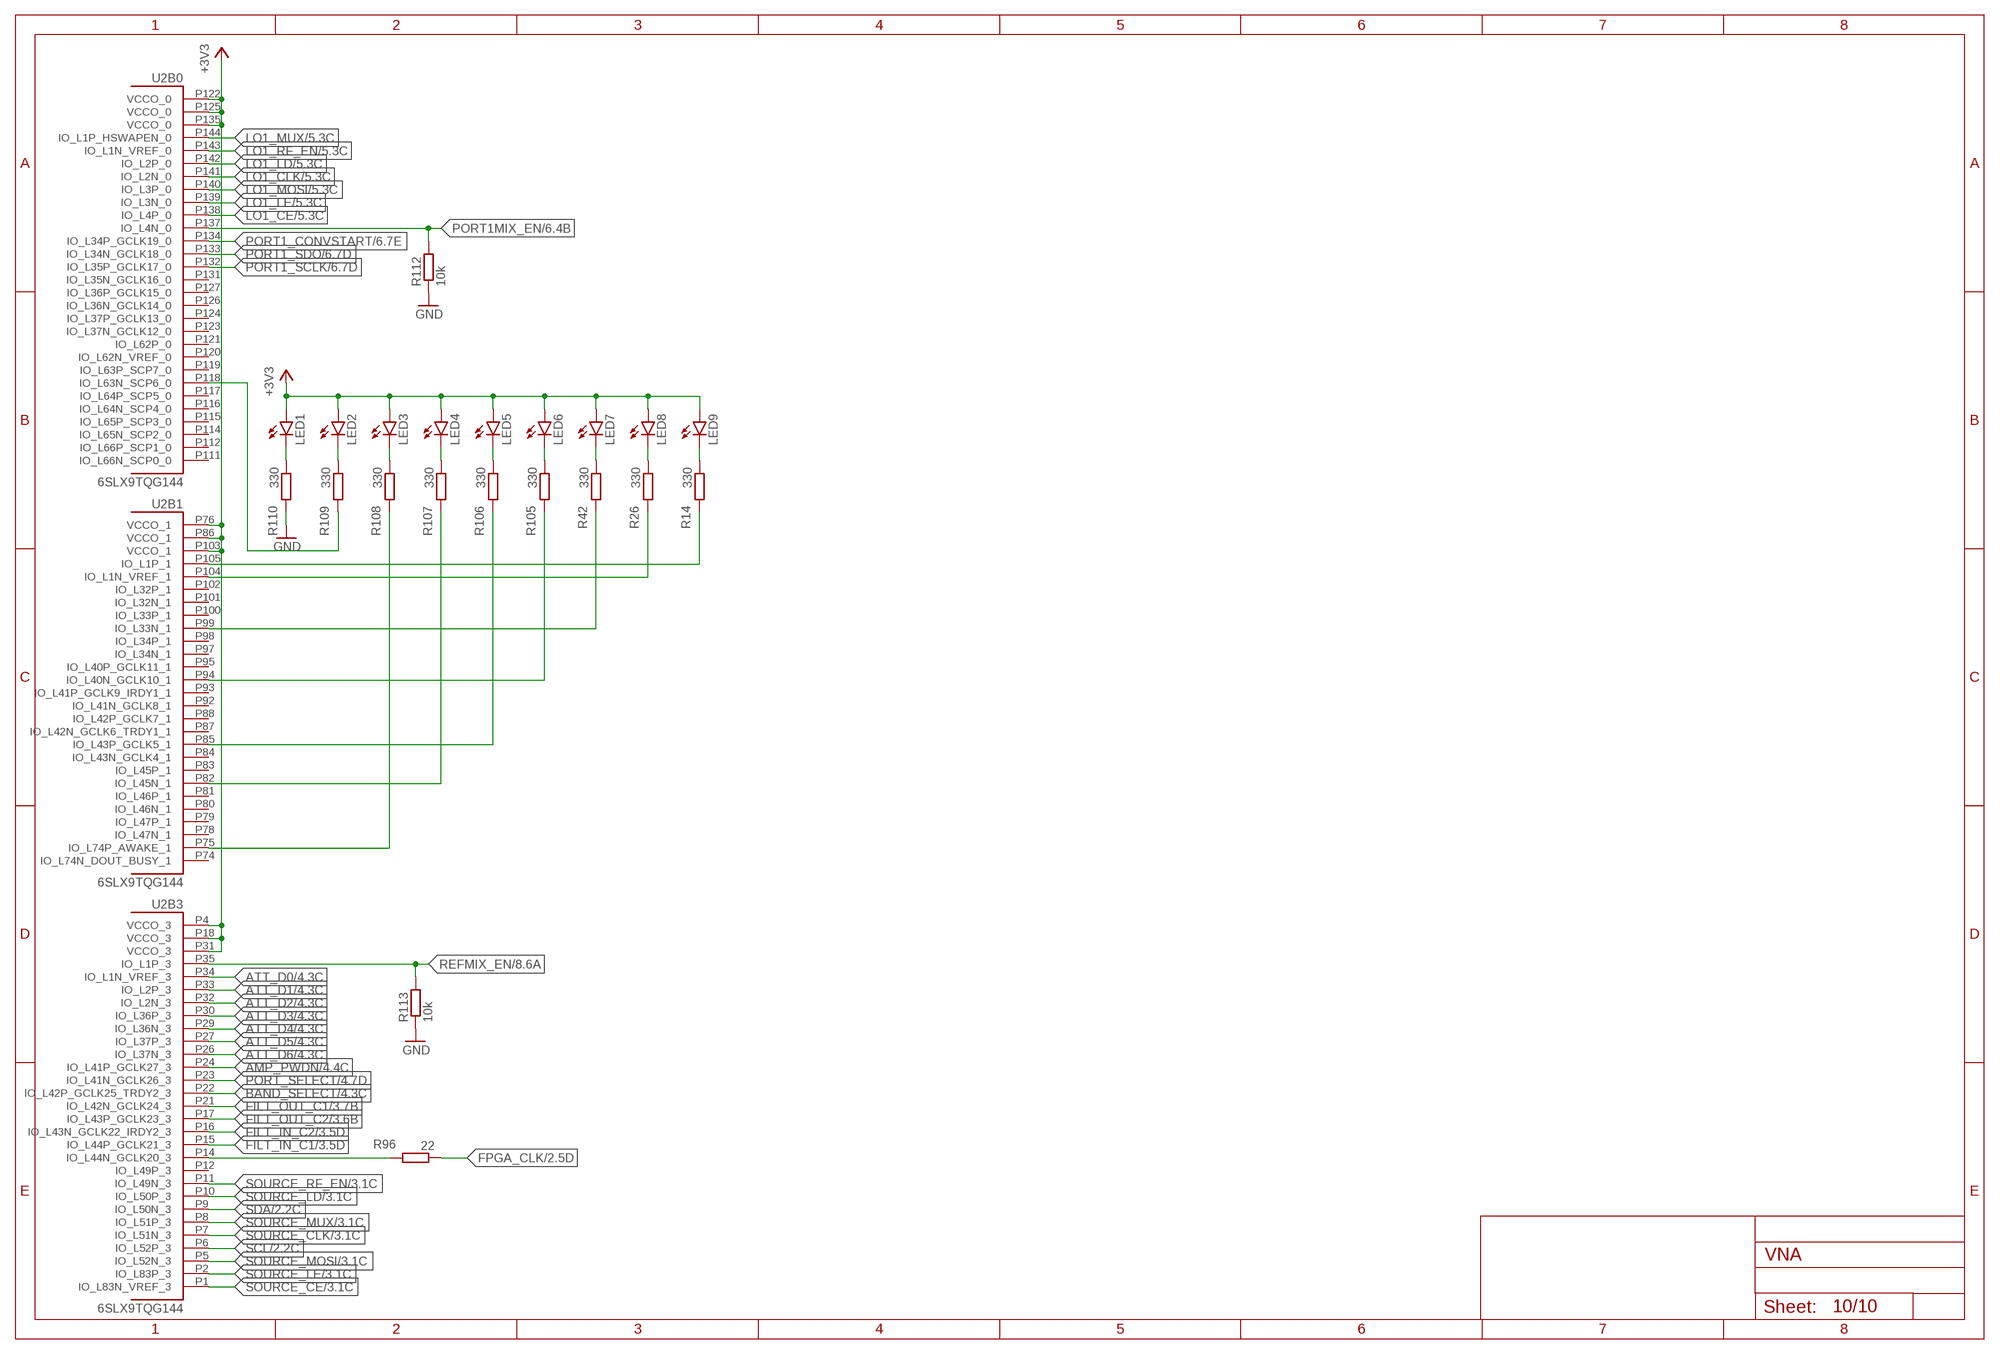
[diagram p9: schematic, sheet 10]

(export (version "E")
  (design (tool "Eeschema 10.0.6"))
  (components
    (comp (ref "C1")
      (value "100n")
      (footprint "eagle-import:C0603")
      (libsource (lib "eagle-import") (part "C-EU?C0603"))
    )
    (comp (ref "C2")
      (value "100n")
      (footprint "eagle-import:C0603")
      (libsource (lib "eagle-import") (part "C-EU?C0603"))
    )
    (comp (ref "C3")
      (value "100n")
      (footprint "eagle-import:C0603")
      (libsource (lib "eagle-import") (part "C-EU?C0603"))
    )
    (comp (ref "C4")
      (value "100n")
      (footprint "eagle-import:C0603")
      (libsource (lib "eagle-import") (part "C-EU?C0603"))
    )
    (comp (ref "C5")
      (value "DNP")
      (footprint "eagle-import:C0603")
      (libsource (lib "eagle-import") (part "C-EU?C0603"))
    )
    (comp (ref "C6")
      (value "100n")
      (footprint "eagle-import:C0603")
      (libsource (lib "eagle-import") (part "C-EU?C0603"))
    )
    (comp (ref "C7")
      (value "100n")
      (footprint "eagle-import:C0603")
      (libsource (lib "eagle-import") (part "C-EU?C0603"))
    )
    (comp (ref "C8")
      (value "10n")
      (footprint "eagle-import:C0603")
      (libsource (lib "eagle-import") (part "C-EU?C0603"))
    )
    (comp (ref "C9")
      (value "1u")
      (footprint "eagle-import:C0603")
      (libsource (lib "eagle-import") (part "C-EU?C0603"))
    )
    (comp (ref "C10")
      (value "10n")
      (footprint "eagle-import:C0603")
      (libsource (lib "eagle-import") (part "C-EU?C0603"))
    )
    (comp (ref "C11")
      (value "10n")
      (footprint "eagle-import:C0603")
      (libsource (lib "eagle-import") (part "C-EU?C0603"))
    )
    (comp (ref "C12")
      (value "100n")
      (footprint "eagle-import:C0603")
      (libsource (lib "eagle-import") (part "C-EU?C0603"))
    )
    (comp (ref "C13")
      (value "100n")
      (footprint "eagle-import:C0603")
      (libsource (lib "eagle-import") (part "C-EU?C0603"))
    )
    (comp (ref "C14")
      (value "120p")
      (footprint "eagle-import:C0603")
      (libsource (lib "eagle-import") (part "C-EU?C0603"))
    )
    (comp (ref "C15")
      (value "100n")
      (footprint "eagle-import:C0603")
      (libsource (lib "eagle-import") (part "C-EU?C0603"))
    )
    (comp (ref "C16")
      (value "330p")
      (footprint "eagle-import:C0603")
      (libsource (lib "eagle-import") (part "C-EU?C0603"))
    )
    (comp (ref "C17")
      (value "330p")
      (footprint "eagle-import:C0603")
      (libsource (lib "eagle-import") (part "C-EU?C0603"))
    )
    (comp (ref "C18")
      (value "100n")
      (footprint "eagle-import:C0603")
      (libsource (lib "eagle-import") (part "C-EU?C0603"))
    )
    (comp (ref "C19")
      (value "330p")
      (footprint "eagle-import:C0603")
      (libsource (lib "eagle-import") (part "C-EU?C0603"))
    )
    (comp (ref "C20")
      (value "1u")
      (footprint "eagle-import:C0603")
      (libsource (lib "eagle-import") (part "C-EU?C0603"))
    )
    (comp (ref "C21")
      (value "1u")
      (footprint "eagle-import:C0603")
      (libsource (lib "eagle-import") (part "C-EU?C0603"))
    )
    (comp (ref "C22")
      (value "100n")
      (footprint "eagle-import:C0603")
      (libsource (lib "eagle-import") (part "C-EU?C0603"))
    )
    (comp (ref "C23")
      (value "100n")
      (footprint "eagle-import:C0603")
      (libsource (lib "eagle-import") (part "C-EU?C0603"))
    )
    (comp (ref "C24")
      (value "DNP")
      (footprint "eagle-import:C0603")
      (libsource (lib "eagle-import") (part "C-EU?C0603"))
    )
    (comp (ref "C25")
      (value "DNP")
      (footprint "eagle-import:C0603")
      (libsource (lib "eagle-import") (part "C-EU?C0603"))
    )
    (comp (ref "C26")
      (value "100n")
      (footprint "eagle-import:C0603")
      (libsource (lib "eagle-import") (part "C-EU?C0603"))
    )
    (comp (ref "C27")
      (value "330p")
      (footprint "eagle-import:C0603")
      (libsource (lib "eagle-import") (part "C-EU?C0603"))
    )
    (comp (ref "C29")
      (value "100n")
      (footprint "eagle-import:C0603")
      (libsource (lib "eagle-import") (part "C-EU?C0603"))
    )
    (comp (ref "C30")
      (value "100n")
      (footprint "eagle-import:C0603")
      (libsource (lib "eagle-import") (part "C-EU?C0603"))
    )
    (comp (ref "C31")
      (value "150p")
      (footprint "eagle-import:C0603")
      (libsource (lib "eagle-import") (part "C-EU?C0603"))
    )
    (comp (ref "C32")
      (value "33p")
      (footprint "eagle-import:C0603")
      (libsource (lib "eagle-import") (part "C-EU?C0603"))
    )
    (comp (ref "C193")
      (value "1u")
      (footprint "eagle-import:C0603")
      (libsource (lib "eagle-import") (part "C-EU?C0603"))
    )
    (comp (ref "C194")
      (value "1u")
      (footprint "eagle-import:C0603")
      (libsource (lib "eagle-import") (part "C-EU?C0603"))
    )
    (comp (ref "IC1")
      (value "LTC5510")
      (footprint "eagle-import:QFN65P400X400X75-17T215N")
      (libsource (lib "eagle-import") (part "LTC5510"))
    )
    (comp (ref "IC2")
      (value "LT5560")
      (footprint "eagle-import:SON50P300X300X80-9T165X238")
      (libsource (lib "eagle-import") (part "LT5560"))
    )
    (comp (ref "IC3")
      (value "LTC6362")
      (footprint "eagle-import:SON50P300X300X80-9T165X238")
      (libsource (lib "eagle-import") (part "LTC6362"))
    )
    (comp (ref "IC4")
      (value "MCP33131D-10-E/MS")
      (footprint "eagle-import:SOP50P490X110-10N")
      (libsource (lib "eagle-import") (part "MCP33131D-10-E/MS"))
    )
    (comp (ref "IC34")
      (value "NCP702-1.8")
      (footprint "eagle-import:SOT95P240X110-5")
      (libsource (lib "eagle-import") (part "NCP702"))
    )
    (comp (ref "L1")
      (value "330n")
      (footprint "eagle-import:R0603")
      (libsource (lib "eagle-import") (part "INDUCTOR0603"))
    )
    (comp (ref "L2")
      (value "330n")
      (footprint "eagle-import:R0603")
      (libsource (lib "eagle-import") (part "INDUCTOR0603"))
    )
    (comp (ref "L3")
      (value "330n")
      (footprint "eagle-import:R0603")
      (libsource (lib "eagle-import") (part "INDUCTOR0603"))
    )
    (comp (ref "L4")
      (value "220Ohm")
      (footprint "eagle-import:R0603")
      (libsource (lib "eagle-import") (part "INDUCTOR0603"))
    )
    (comp (ref "L5")
      (value "220Ohm")
      (footprint "eagle-import:R0603")
      (libsource (lib "eagle-import") (part "INDUCTOR0603"))
    )
    (comp (ref "L7")
      (value "68n")
      (footprint "eagle-import:R0603")
      (libsource (lib "eagle-import") (part "INDUCTOR0603"))
    )
    (comp (ref "L8")
      (value "68n")
      (footprint "eagle-import:R0603")
      (libsource (lib "eagle-import") (part "INDUCTOR0603"))
    )
    (comp (ref "L9")
      (value "33n")
      (footprint "eagle-import:R0603")
      (libsource (lib "eagle-import") (part "INDUCTOR0603"))
    )
    (comp (ref "L10")
      (value "33n")
      (footprint "eagle-import:R0603")
      (libsource (lib "eagle-import") (part "INDUCTOR0603"))
    )
    (comp (ref "L11")
      (value "330n")
      (footprint "eagle-import:R0603")
      (libsource (lib "eagle-import") (part "INDUCTOR0603"))
    )
    (comp (ref "R1")
      (value "620")
      (footprint "eagle-import:R0603")
      (libsource (lib "eagle-import") (part "R-EU_R0603"))
    )
    (comp (ref "R2")
      (value "620")
      (footprint "eagle-import:R0603")
      (libsource (lib "eagle-import") (part "R-EU_R0603"))
    )
    (comp (ref "R3")
      (value "18")
      (footprint "eagle-import:R0603")
      (libsource (lib "eagle-import") (part "R-EU_R0603"))
    )
    (comp (ref "R4")
      (value "620")
      (footprint "eagle-import:R0603")
      (libsource (lib "eagle-import") (part "R-EU_R0603"))
    )
    (comp (ref "R5")
      (value "620")
      (footprint "eagle-import:R0603")
      (libsource (lib "eagle-import") (part "R-EU_R0603"))
    )
    (comp (ref "R6")
      (value "49R9")
      (footprint "eagle-import:R0603")
      (libsource (lib "eagle-import") (part "R-EU_R0603"))
    )
    (comp (ref "R7")
      (value "49R9")
      (footprint "eagle-import:R0603")
      (libsource (lib "eagle-import") (part "R-EU_R0603"))
    )
    (comp (ref "R8")
      (value "49R9")
      (footprint "eagle-import:R0603")
      (libsource (lib "eagle-import") (part "R-EU_R0603"))
    )
    (comp (ref "R11")
      (value "DNP")
      (footprint "eagle-import:R0603")
      (libsource (lib "eagle-import") (part "R-EU_R0603"))
    )
    (comp (ref "R15")
      (value "200")
      (footprint "eagle-import:R0603")
      (libsource (lib "eagle-import") (part "R-EU_R0603"))
    )
    (comp (ref "R16")
      (value "200")
      (footprint "eagle-import:R0603")
      (libsource (lib "eagle-import") (part "R-EU_R0603"))
    )
    (comp (ref "R17")
      (value "6k8")
      (footprint "eagle-import:R0603")
      (libsource (lib "eagle-import") (part "R-EU_R0603"))
    )
    (comp (ref "R18")
      (value "6k8")
      (footprint "eagle-import:R0603")
      (libsource (lib "eagle-import") (part "R-EU_R0603"))
    )
    (comp (ref "R19")
      (value "220")
      (footprint "eagle-import:R0603")
      (libsource (lib "eagle-import") (part "R-EU_R0603"))
    )
    (comp (ref "R20")
      (value "220")
      (footprint "eagle-import:R0603")
      (libsource (lib "eagle-import") (part "R-EU_R0603"))
    )
    (comp (ref "R33")
      (value "56")
      (footprint "eagle-import:R0603")
      (libsource (lib "eagle-import") (part "R-EU_R0603"))
    )
    (comp (ref "R34")
      (value "20")
      (footprint "eagle-import:R0603")
      (libsource (lib "eagle-import") (part "R-EU_R0603"))
    )
    (comp (ref "R35")
      (value "20")
      (footprint "eagle-import:R0603")
      (libsource (lib "eagle-import") (part "R-EU_R0603"))
    )
    (comp (ref "R36")
      (value "56")
      (footprint "eagle-import:R0603")
      (libsource (lib "eagle-import") (part "R-EU_R0603"))
    )
    (comp (ref "T1")
      (value "MABA011082")
      (footprint "eagle-import:MACOM_BALUN")
      (libsource (lib "eagle-import") (part "MABA011082"))
    )
    (comp (ref "TP2")
      (value "TPB1,27")
      (footprint "eagle-import:B1,27")
      (libsource (lib "eagle-import") (part "TPB1,27"))
    )
    (comp (ref "X2")
      (value "RLB DUT/RF IN")
      (footprint "eagle-import:J502-ND-142-0711-821_826")
      (libsource (lib "eagle-import") (part "SMA_CONNECTOR"))
    )
    (comp (ref "C28")
      (value "1u")
      (footprint "eagle-import:C0603")
      (libsource (lib "eagle-import") (part "C-EU?C0603"))
    )
    (comp (ref "C33")
      (value "100n")
      (footprint "eagle-import:C0603")
      (libsource (lib "eagle-import") (part "C-EU?C0603"))
    )
    (comp (ref "C34")
      (value "100n")
      (footprint "eagle-import:C0603")
      (libsource (lib "eagle-import") (part "C-EU?C0603"))
    )
    (comp (ref "C35")
      (value "100n")
      (footprint "eagle-import:C0603")
      (libsource (lib "eagle-import") (part "C-EU?C0603"))
    )
    (comp (ref "C36")
      (value "100n")
      (footprint "eagle-import:C0603")
      (libsource (lib "eagle-import") (part "C-EU?C0603"))
    )
    (comp (ref "C37")
      (value "DNP")
      (footprint "eagle-import:C0603")
      (libsource (lib "eagle-import") (part "C-EU?C0603"))
    )
    (comp (ref "C38")
      (value "100n")
      (footprint "eagle-import:C0603")
      (libsource (lib "eagle-import") (part "C-EU?C0603"))
    )
    (comp (ref "C39")
      (value "100n")
      (footprint "eagle-import:C0603")
      (libsource (lib "eagle-import") (part "C-EU?C0603"))
    )
    (comp (ref "C40")
      (value "10n")
      (footprint "eagle-import:C0603")
      (libsource (lib "eagle-import") (part "C-EU?C0603"))
    )
    (comp (ref "C41")
      (value "1u")
      (footprint "eagle-import:C0603")
      (libsource (lib "eagle-import") (part "C-EU?C0603"))
    )
    (comp (ref "C42")
      (value "10n")
      (footprint "eagle-import:C0603")
      (libsource (lib "eagle-import") (part "C-EU?C0603"))
    )
    (comp (ref "C43")
      (value "100n")
      (footprint "eagle-import:C0603")
      (libsource (lib "eagle-import") (part "C-EU?C0603"))
    )
    (comp (ref "C44")
      (value "100n")
      (footprint "eagle-import:C0603")
      (libsource (lib "eagle-import") (part "C-EU?C0603"))
    )
    (comp (ref "C45")
      (value "100n")
      (footprint "eagle-import:C0603")
      (libsource (lib "eagle-import") (part "C-EU?C0603"))
    )
    (comp (ref "C46")
      (value "1u")
      (footprint "eagle-import:C0603")
      (libsource (lib "eagle-import") (part "C-EU?C0603"))
    )
    (comp (ref "C47")
      (value "1u")
      (footprint "eagle-import:C0603")
      (libsource (lib "eagle-import") (part "C-EU?C0603"))
    )
    (comp (ref "C48")
      (value "100n")
      (footprint "eagle-import:C0603")
      (libsource (lib "eagle-import") (part "C-EU?C0603"))
    )
    (comp (ref "C49")
      (value "100n")
      (footprint "eagle-import:C0603")
      (libsource (lib "eagle-import") (part "C-EU?C0603"))
    )
    (comp (ref "C50")
      (value "DNP")
      (footprint "eagle-import:C0603")
      (libsource (lib "eagle-import") (part "C-EU?C0603"))
    )
    (comp (ref "C51")
      (value "DNP")
      (footprint "eagle-import:C0603")
      (libsource (lib "eagle-import") (part "C-EU?C0603"))
    )
    (comp (ref "C52")
      (value "100n")
      (footprint "eagle-import:C0603")
      (libsource (lib "eagle-import") (part "C-EU?C0603"))
    )
    (comp (ref "C53")
      (value "330p")
      (footprint "eagle-import:C0603")
      (libsource (lib "eagle-import") (part "C-EU?C0603"))
    )
    (comp (ref "C54")
      (value "100n")
      (footprint "eagle-import:C0603")
      (libsource (lib "eagle-import") (part "C-EU?C0603"))
    )
    (comp (ref "C55")
      (value "10n")
      (footprint "eagle-import:C0603")
      (libsource (lib "eagle-import") (part "C-EU?C0603"))
    )
    (comp (ref "C56")
      (value "120p")
      (footprint "eagle-import:C0603")
      (libsource (lib "eagle-import") (part "C-EU?C0603"))
    )
    (comp (ref "C57")
      (value "150p")
      (footprint "eagle-import:C0603")
      (libsource (lib "eagle-import") (part "C-EU?C0603"))
    )
    (comp (ref "C58")
      (value "33p")
      (footprint "eagle-import:C0603")
      (libsource (lib "eagle-import") (part "C-EU?C0603"))
    )
    (comp (ref "C59")
      (value "100n")
      (footprint "eagle-import:C0603")
      (libsource (lib "eagle-import") (part "C-EU?C0603"))
    )
    (comp (ref "C60")
      (value "330p")
      (footprint "eagle-import:C0603")
      (libsource (lib "eagle-import") (part "C-EU?C0603"))
    )
    (comp (ref "C61")
      (value "330p")
      (footprint "eagle-import:C0603")
      (libsource (lib "eagle-import") (part "C-EU?C0603"))
    )
    (comp (ref "C62")
      (value "330p")
      (footprint "eagle-import:C0603")
      (libsource (lib "eagle-import") (part "C-EU?C0603"))
    )
    (comp (ref "C63")
      (value "1u")
      (footprint "eagle-import:C0603")
      (libsource (lib "eagle-import") (part "C-EU?C0603"))
    )
    (comp (ref "C64")
      (value "100n")
      (footprint "eagle-import:C0603")
      (libsource (lib "eagle-import") (part "C-EU?C0603"))
    )
    (comp (ref "IC5")
      (value "LTC5510")
      (footprint "eagle-import:QFN65P400X400X75-17T215N")
      (libsource (lib "eagle-import") (part "LTC5510"))
    )
    (comp (ref "IC6")
      (value "LT5560")
      (footprint "eagle-import:SON50P300X300X80-9T165X238")
      (libsource (lib "eagle-import") (part "LT5560"))
    )
    (comp (ref "IC7")
      (value "LTC6362")
      (footprint "eagle-import:SON50P300X300X80-9T165X238")
      (libsource (lib "eagle-import") (part "LTC6362"))
    )
    (comp (ref "IC8")
      (value "MCP33131D-10-E/MS")
      (footprint "eagle-import:SOP50P490X110-10N")
      (libsource (lib "eagle-import") (part "MCP33131D-10-E/MS"))
    )
    (comp (ref "IC35")
      (value "NCP702-1.8")
      (footprint "eagle-import:SOT95P240X110-5")
      (libsource (lib "eagle-import") (part "NCP702"))
    )
    (comp (ref "L6")
      (value "330n")
      (footprint "eagle-import:R0603")
      (libsource (lib "eagle-import") (part "INDUCTOR0603"))
    )
    (comp (ref "L12")
      (value "330n")
      (footprint "eagle-import:R0603")
      (libsource (lib "eagle-import") (part "INDUCTOR0603"))
    )
    (comp (ref "L13")
      (value "68n")
      (footprint "eagle-import:R0603")
      (libsource (lib "eagle-import") (part "INDUCTOR0603"))
    )
    (comp (ref "L14")
      (value "68n")
      (footprint "eagle-import:R0603")
      (libsource (lib "eagle-import") (part "INDUCTOR0603"))
    )
    (comp (ref "L15")
      (value "33n")
      (footprint "eagle-import:R0603")
      (libsource (lib "eagle-import") (part "INDUCTOR0603"))
    )
    (comp (ref "L16")
      (value "33n")
      (footprint "eagle-import:R0603")
      (libsource (lib "eagle-import") (part "INDUCTOR0603"))
    )
    (comp (ref "L17")
      (value "330n")
      (footprint "eagle-import:R0603")
      (libsource (lib "eagle-import") (part "INDUCTOR0603"))
    )
    (comp (ref "L18")
      (value "330n")
      (footprint "eagle-import:R0603")
      (libsource (lib "eagle-import") (part "INDUCTOR0603"))
    )
    (comp (ref "L19")
      (value "220Ohm")
      (footprint "eagle-import:R0603")
      (libsource (lib "eagle-import") (part "INDUCTOR0603"))
    )
    (comp (ref "L20")
      (value "220Ohm")
      (footprint "eagle-import:R0603")
      (libsource (lib "eagle-import") (part "INDUCTOR0603"))
    )
    (comp (ref "R9")
      (value "620")
      (footprint "eagle-import:R0603")
      (libsource (lib "eagle-import") (part "R-EU_R0603"))
    )
    (comp (ref "R10")
      (value "620")
      (footprint "eagle-import:R0603")
      (libsource (lib "eagle-import") (part "R-EU_R0603"))
    )
    (comp (ref "R12")
      (value "18")
      (footprint "eagle-import:R0603")
      (libsource (lib "eagle-import") (part "R-EU_R0603"))
    )
    (comp (ref "R13")
      (value "620")
      (footprint "eagle-import:R0603")
      (libsource (lib "eagle-import") (part "R-EU_R0603"))
    )
    (comp (ref "R21")
      (value "620")
      (footprint "eagle-import:R0603")
      (libsource (lib "eagle-import") (part "R-EU_R0603"))
    )
    (comp (ref "R22")
      (value "49R9")
      (footprint "eagle-import:R0603")
      (libsource (lib "eagle-import") (part "R-EU_R0603"))
    )
    (comp (ref "R23")
      (value "49R9")
      (footprint "eagle-import:R0603")
      (libsource (lib "eagle-import") (part "R-EU_R0603"))
    )
    (comp (ref "R24")
      (value "49R9")
      (footprint "eagle-import:R0603")
      (libsource (lib "eagle-import") (part "R-EU_R0603"))
    )
    (comp (ref "R25")
      (value "DNP")
      (footprint "eagle-import:R0603")
      (libsource (lib "eagle-import") (part "R-EU_R0603"))
    )
    (comp (ref "R27")
      (value "200")
      (footprint "eagle-import:R0603")
      (libsource (lib "eagle-import") (part "R-EU_R0603"))
    )
    (comp (ref "R28")
      (value "200")
      (footprint "eagle-import:R0603")
      (libsource (lib "eagle-import") (part "R-EU_R0603"))
    )
    (comp (ref "R29")
      (value "6k8")
      (footprint "eagle-import:R0603")
      (libsource (lib "eagle-import") (part "R-EU_R0603"))
    )
    (comp (ref "R30")
      (value "6k8")
      (footprint "eagle-import:R0603")
      (libsource (lib "eagle-import") (part "R-EU_R0603"))
    )
    (comp (ref "R31")
      (value "220")
      (footprint "eagle-import:R0603")
      (libsource (lib "eagle-import") (part "R-EU_R0603"))
    )
    (comp (ref "R32")
      (value "220")
      (footprint "eagle-import:R0603")
      (libsource (lib "eagle-import") (part "R-EU_R0603"))
    )
    (comp (ref "R37")
      (value "56")
      (footprint "eagle-import:R0603")
      (libsource (lib "eagle-import") (part "R-EU_R0603"))
    )
    (comp (ref "R38")
      (value "20")
      (footprint "eagle-import:R0603")
      (libsource (lib "eagle-import") (part "R-EU_R0603"))
    )
    (comp (ref "R39")
      (value "20")
      (footprint "eagle-import:R0603")
      (libsource (lib "eagle-import") (part "R-EU_R0603"))
    )
    (comp (ref "R40")
      (value "56")
      (footprint "eagle-import:R0603")
      (libsource (lib "eagle-import") (part "R-EU_R0603"))
    )
    (comp (ref "T2")
      (value "MABA011082")
      (footprint "eagle-import:MACOM_BALUN")
      (libsource (lib "eagle-import") (part "MABA011082"))
    )
    (comp (ref "TP4")
      (value "TPB1,27")
      (footprint "eagle-import:B1,27")
      (libsource (lib "eagle-import") (part "TPB1,27"))
    )
    (comp (ref "X1")
      (value "RLB DUT/RF IN")
      (footprint "eagle-import:J502-ND-142-0711-821_826")
      (libsource (lib "eagle-import") (part "SMA_CONNECTOR"))
    )
    (comp (ref "C106")
      (value "1u")
      (footprint "eagle-import:C0603")
      (libsource (lib "eagle-import") (part "C-EUC0603"))
    )
    (comp (ref "C113")
      (value "4u7")
      (footprint "eagle-import:C0603")
      (libsource (lib "eagle-import") (part "C-EU?C0603"))
    )
    (comp (ref "C158")
      (value "1u")
      (footprint "eagle-import:C0603")
      (libsource (lib "eagle-import") (part "C-EU?C0603"))
    )
    (comp (ref "C159")
      (value "4u7")
      (footprint "eagle-import:C0603")
      (libsource (lib "eagle-import") (part "C-EU?C0603"))
    )
    (comp (ref "C160")
      (value "1u")
      (footprint "eagle-import:C0603")
      (libsource (lib "eagle-import") (part "C-EU?C0603"))
    )
    (comp (ref "C161")
      (value "4u7")
      (footprint "eagle-import:C0603")
      (libsource (lib "eagle-import") (part "C-EU?C0603"))
    )
    (comp (ref "C162")
      (value "1u")
      (footprint "eagle-import:C0603")
      (libsource (lib "eagle-import") (part "C-EU?C0603"))
    )
    (comp (ref "C163")
      (value "4u7")
      (footprint "eagle-import:C0603")
      (libsource (lib "eagle-import") (part "C-EU?C0603"))
    )
    (comp (ref "C164")
      (value "1u")
      (footprint "eagle-import:C0603")
      (libsource (lib "eagle-import") (part "C-EU?C0603"))
    )
    (comp (ref "C165")
      (value "1u")
      (footprint "eagle-import:C0603")
      (libsource (lib "eagle-import") (part "C-EU?C0603"))
    )
    (comp (ref "C166")
      (value "1u")
      (footprint "eagle-import:C0603")
      (libsource (lib "eagle-import") (part "C-EU?C0603"))
    )
    (comp (ref "C167")
      (value "1u")
      (footprint "eagle-import:C0603")
      (libsource (lib "eagle-import") (part "C-EU?C0603"))
    )
    (comp (ref "C168")
      (value "1u")
      (footprint "eagle-import:C0603")
      (libsource (lib "eagle-import") (part "C-EU?C0603"))
    )
    (comp (ref "C169")
      (value "22u")
      (footprint "eagle-import:C1206")
      (libsource (lib "eagle-import") (part "C-EUC1206"))
    )
    (comp (ref "C170")
      (value "22u")
      (footprint "eagle-import:C1206")
      (libsource (lib "eagle-import") (part "C-EUC1206"))
    )
    (comp (ref "C171")
      (value "22u")
      (footprint "eagle-import:C1206")
      (libsource (lib "eagle-import") (part "C-EUC1206"))
    )
    (comp (ref "C172")
      (value "22u")
      (footprint "eagle-import:C1206")
      (libsource (lib "eagle-import") (part "C-EUC1206"))
    )
    (comp (ref "C173")
      (value "10u/25V")
      (footprint "eagle-import:C1206")
      (libsource (lib "eagle-import") (part "C-EUC1206"))
    )
    (comp (ref "C174")
      (value "22u")
      (footprint "eagle-import:C1206")
      (libsource (lib "eagle-import") (part "C-EUC1206"))
    )
    (comp (ref "C175")
      (value "47n")
      (footprint "eagle-import:C0603")
      (libsource (lib "eagle-import") (part "C-EU?C0603"))
    )
    (comp (ref "C176")
      (value "510p")
      (footprint "eagle-import:C0603")
      (libsource (lib "eagle-import") (part "C-EU?C0603"))
    )
    (comp (ref "C177")
      (value "10u/25V")
      (footprint "eagle-import:C1206")
      (libsource (lib "eagle-import") (part "C-EUC1206"))
    )
    (comp (ref "C178")
      (value "47n")
      (footprint "eagle-import:C0603")
      (libsource (lib "eagle-import") (part "C-EU?C0603"))
    )
    (comp (ref "C179")
      (value "DNP")
      (footprint "eagle-import:C0603")
      (libsource (lib "eagle-import") (part "C-EU?C0603"))
    )
    (comp (ref "C180")
      (value "22u")
      (footprint "eagle-import:C1206")
      (libsource (lib "eagle-import") (part "C-EUC1206"))
    )
    (comp (ref "C181")
      (value "22u")
      (footprint "eagle-import:C1206")
      (libsource (lib "eagle-import") (part "C-EUC1206"))
    )
    (comp (ref "C182")
      (value "120p")
      (footprint "eagle-import:C0603")
      (libsource (lib "eagle-import") (part "C-EU?C0603"))
    )
    (comp (ref "C183")
      (value "DNP")
      (footprint "eagle-import:C0603")
      (libsource (lib "eagle-import") (part "C-EU?C0603"))
    )
    (comp (ref "C184")
      (value "22u")
      (footprint "eagle-import:C1206")
      (libsource (lib "eagle-import") (part "C-EUC1206"))
    )
    (comp (ref "C185")
      (value "10u/25V")
      (footprint "eagle-import:C1206")
      (libsource (lib "eagle-import") (part "C-EUC1206"))
    )
    (comp (ref "C186")
      (value "47n")
      (footprint "eagle-import:C0603")
      (libsource (lib "eagle-import") (part "C-EU?C0603"))
    )
    (comp (ref "C187")
      (value "1n")
      (footprint "eagle-import:C0603")
      (libsource (lib "eagle-import") (part "C-EU?C0603"))
    )
    (comp (ref "C188")
      (value "8p2")
      (footprint "eagle-import:C0603")
      (libsource (lib "eagle-import") (part "C-EU?C0603"))
    )
    (comp (ref "C189")
      (value "22u")
      (footprint "eagle-import:C1206")
      (libsource (lib "eagle-import") (part "C-EUC1206"))
    )
    (comp (ref "C190")
      (value "22u")
      (footprint "eagle-import:C1206")
      (libsource (lib "eagle-import") (part "C-EUC1206"))
    )
    (comp (ref "IC28")
      (value "LDL212PU50R")
      (footprint "eagle-import:SON95P300X300X100-7T170X240N")
      (libsource (lib "eagle-import") (part "LDL212PU50R"))
    )
    (comp (ref "IC29")
      (value "LDL212PU50R")
      (footprint "eagle-import:SON95P300X300X100-7T170X240N")
      (libsource (lib "eagle-import") (part "LDL212PU50R"))
    )
    (comp (ref "IC30")
      (value "LDL212PU50R")
      (footprint "eagle-import:SON95P300X300X100-7T170X240N")
      (libsource (lib "eagle-import") (part "LDL212PU50R"))
    )
    (comp (ref "IC31")
      (value "LDL212PU50R")
      (footprint "eagle-import:SON95P300X300X100-7T170X240N")
      (libsource (lib "eagle-import") (part "LDL212PU50R"))
    )
    (comp (ref "IC32")
      (value "TPS65265")
      (footprint "eagle-import:QFN50P500X500X100-33T345N")
      (libsource (lib "eagle-import") (part "TPS65265"))
    )
    (comp (ref "J3")
      (value "DCJ0202")
      (footprint "eagle-import:DCJ0202")
      (libsource (lib "eagle-import") (part "DCJ0202"))
    )
    (comp (ref "L47")
      (value "Ferrite")
      (footprint "eagle-import:R0603")
      (libsource (lib "eagle-import") (part "INDUCTOR0603"))
    )
    (comp (ref "L48")
      (value "Ferrite")
      (footprint "eagle-import:R0603")
      (libsource (lib "eagle-import") (part "INDUCTOR0603"))
    )
    (comp (ref "L49")
      (value "Ferrite")
      (footprint "eagle-import:R0603")
      (libsource (lib "eagle-import") (part "INDUCTOR0603"))
    )
    (comp (ref "L50")
      (value "Ferrite")
      (footprint "eagle-import:R0603")
      (libsource (lib "eagle-import") (part "INDUCTOR0603"))
    )
    (comp (ref "L51")
      (value "10u")
      (footprint "eagle-import:SRN5040")
      (libsource (lib "eagle-import") (part "SRN5040"))
    )
    (comp (ref "L52")
      (value "6u8")
      (footprint "eagle-import:SRN5040")
      (libsource (lib "eagle-import") (part "SRN5040"))
    )
    (comp (ref "L53")
      (value "6u8")
      (footprint "eagle-import:SRN5040")
      (libsource (lib "eagle-import") (part "SRN5040"))
    )
    (comp (ref "L54")
      (value "6u8")
      (footprint "eagle-import:SRN5040")
      (libsource (lib "eagle-import") (part "SRN5040"))
    )
    (comp (ref "L55")
      (value "10u")
      (footprint "eagle-import:SRN5040")
      (libsource (lib "eagle-import") (part "SRN5040"))
    )
    (comp (ref "R77")
      (value "DNP")
      (footprint "eagle-import:R0603")
      (libsource (lib "eagle-import") (part "R-EU_R0603"))
    )
    (comp (ref "R78")
      (value "51k")
      (footprint "eagle-import:R0603")
      (libsource (lib "eagle-import") (part "R-EU_R0603"))
    )
    (comp (ref "R79")
      (value "82k")
      (footprint "eagle-import:R0603")
      (libsource (lib "eagle-import") (part "R-EU_R0603"))
    )
    (comp (ref "R80")
      (value "10k")
      (footprint "eagle-import:R0603")
      (libsource (lib "eagle-import") (part "R-EU_R0603"))
    )
    (comp (ref "R81")
      (value "91k")
      (footprint "eagle-import:R0603")
      (libsource (lib "eagle-import") (part "R-EU_R0603"))
    )
    (comp (ref "R82")
      (value "30k")
      (footprint "eagle-import:R0603")
      (libsource (lib "eagle-import") (part "R-EU_R0603"))
    )
    (comp (ref "R83")
      (value "10k")
      (footprint "eagle-import:R0603")
      (libsource (lib "eagle-import") (part "R-EU_R0603"))
    )
    (comp (ref "R84")
      (value "45k3")
      (footprint "eagle-import:R0603")
      (libsource (lib "eagle-import") (part "R-EU_R0603"))
    )
    (comp (ref "R85")
      (value "16k")
      (footprint "eagle-import:R0603")
      (libsource (lib "eagle-import") (part "R-EU_R0603"))
    )
    (comp (ref "R86")
      (value "10k")
      (footprint "eagle-import:R0603")
      (libsource (lib "eagle-import") (part "R-EU_R0603"))
    )
    (comp (ref "R87")
      (value "20k")
      (footprint "eagle-import:R0603")
      (libsource (lib "eagle-import") (part "R-EU_R0603"))
    )
    (comp (ref "TP1")
      (value "TPB1,27")
      (footprint "eagle-import:B1,27")
      (libsource (lib "eagle-import") (part "TPB1,27"))
    )
    (comp (ref "TP3")
      (value "TPB1,27")
      (footprint "eagle-import:B1,27")
      (libsource (lib "eagle-import") (part "TPB1,27"))
    )
    (comp (ref "TP5")
      (value "TPB1,27")
      (footprint "eagle-import:B1,27")
      (libsource (lib "eagle-import") (part "TPB1,27"))
    )
    (comp (ref "TP6")
      (value "TPB1,27")
      (footprint "eagle-import:B1,27")
      (libsource (lib "eagle-import") (part "TPB1,27"))
    )
    (comp (ref "TP7")
      (value "TPB1,27")
      (footprint "eagle-import:B1,27")
      (libsource (lib "eagle-import") (part "TPB1,27"))
    )
    (comp (ref "TP8")
      (value "TPB1,27")
      (footprint "eagle-import:B1,27")
      (libsource (lib "eagle-import") (part "TPB1,27"))
    )
    (comp (ref "TP9")
      (value "TPB1,27")
      (footprint "eagle-import:B1,27")
      (libsource (lib "eagle-import") (part "TPB1,27"))
    )
    (comp (ref "TP10")
      (value "TPB1,27")
      (footprint "eagle-import:B1,27")
      (libsource (lib "eagle-import") (part "TPB1,27"))
    )
    (comp (ref "TP11")
      (value "TPB1,27")
      (footprint "eagle-import:B1,27")
      (libsource (lib "eagle-import") (part "TPB1,27"))
    )
    (comp (ref "TP12")
      (value "TPB1,27")
      (footprint "eagle-import:B1,27")
      (libsource (lib "eagle-import") (part "TPB1,27"))
    )
    (comp (ref "TP13")
      (value "TPB1,27")
      (footprint "eagle-import:B1,27")
      (libsource (lib "eagle-import") (part "TPB1,27"))
    )
    (comp (ref "TP14")
      (value "TPB1,27")
      (footprint "eagle-import:B1,27")
      (libsource (lib "eagle-import") (part "TPB1,27"))
    )
    (comp (ref "LED1")
      (value "LEDCHIPLED_0603")
      (footprint "eagle-import:CHIPLED_0603")
      (libsource (lib "eagle-import") (part "LEDCHIPLED_0603"))
    )
    (comp (ref "LED2")
      (value "LEDCHIPLED_0603")
      (footprint "eagle-import:CHIPLED_0603")
      (libsource (lib "eagle-import") (part "LEDCHIPLED_0603"))
    )
    (comp (ref "LED3")
      (value "LEDCHIPLED_0603")
      (footprint "eagle-import:CHIPLED_0603")
      (libsource (lib "eagle-import") (part "LEDCHIPLED_0603"))
    )
    (comp (ref "LED4")
      (value "LEDCHIPLED_0603")
      (footprint "eagle-import:CHIPLED_0603")
      (libsource (lib "eagle-import") (part "LEDCHIPLED_0603"))
    )
    (comp (ref "LED5")
      (value "LEDCHIPLED_0603")
      (footprint "eagle-import:CHIPLED_0603")
      (libsource (lib "eagle-import") (part "LEDCHIPLED_0603"))
    )
    (comp (ref "LED6")
      (value "LEDCHIPLED_0603")
      (footprint "eagle-import:CHIPLED_0603")
      (libsource (lib "eagle-import") (part "LEDCHIPLED_0603"))
    )
    (comp (ref "LED7")
      (value "LEDCHIPLED_0603")
      (footprint "eagle-import:CHIPLED_0603")
      (libsource (lib "eagle-import") (part "LEDCHIPLED_0603"))
    )
    (comp (ref "LED8")
      (value "LEDCHIPLED_0603")
      (footprint "eagle-import:CHIPLED_0603")
      (libsource (lib "eagle-import") (part "LEDCHIPLED_0603"))
    )
    (comp (ref "LED9")
      (value "LEDCHIPLED_0603")
      (footprint "eagle-import:CHIPLED_0603")
      (libsource (lib "eagle-import") (part "LEDCHIPLED_0603"))
    )
    (comp (ref "R14")
      (value "330")
      (footprint "eagle-import:R0603")
      (libsource (lib "eagle-import") (part "R-EU_R0603"))
    )
    (comp (ref "R26")
      (value "330")
      (footprint "eagle-import:R0603")
      (libsource (lib "eagle-import") (part "R-EU_R0603"))
    )
    (comp (ref "R42")
      (value "330")
      (footprint "eagle-import:R0603")
      (libsource (lib "eagle-import") (part "R-EU_R0603"))
    )
    (comp (ref "R96")
      (value "22")
      (footprint "eagle-import:R0603")
      (libsource (lib "eagle-import") (part "R-EU_R0603"))
    )
    (comp (ref "R105")
      (value "330")
      (footprint "eagle-import:R0603")
      (libsource (lib "eagle-import") (part "R-EU_R0603"))
    )
    (comp (ref "R106")
      (value "330")
      (footprint "eagle-import:R0603")
      (libsource (lib "eagle-import") (part "R-EU_R0603"))
    )
    (comp (ref "R107")
      (value "330")
      (footprint "eagle-import:R0603")
      (libsource (lib "eagle-import") (part "R-EU_R0603"))
    )
    (comp (ref "R108")
      (value "330")
      (footprint "eagle-import:R0603")
      (libsource (lib "eagle-import") (part "R-EU_R0603"))
    )
    (comp (ref "R109")
      (value "330")
      (footprint "eagle-import:R0603")
      (libsource (lib "eagle-import") (part "R-EU_R0603"))
    )
    (comp (ref "R110")
      (value "330")
      (footprint "eagle-import:R0603")
      (libsource (lib "eagle-import") (part "R-EU_R0603"))
    )
    (comp (ref "R112")
      (value "10k")
      (footprint "eagle-import:R0603")
      (libsource (lib "eagle-import") (part "R-EU_R0603"))
    )
    (comp (ref "R113")
      (value "10k")
      (footprint "eagle-import:R0603")
      (libsource (lib "eagle-import") (part "R-EU_R0603"))
    )
    (comp (ref "U2")
      (value "6SLX9TQG144")
      (footprint "eagle-import:TQ144")
      (libsource (lib "eagle-import") (part "6SLX9TQG144"))
    )
    (comp (ref "C122")
      (value "1u")
      (footprint "eagle-import:C0603")
      (libsource (lib "eagle-import") (part "C-EU?C0603"))
    )
    (comp (ref "C133")
      (value "1u")
      (footprint "eagle-import:C0603")
      (libsource (lib "eagle-import") (part "C-EU?C0603"))
    )
    (comp (ref "C134")
      (value "1u")
      (footprint "eagle-import:C0603")
      (libsource (lib "eagle-import") (part "C-EU?C0603"))
    )
    (comp (ref "C135")
      (value "180p")
      (footprint "eagle-import:C0603")
      (libsource (lib "eagle-import") (part "C-EU?C0603"))
    )
    (comp (ref "C136")
      (value "18p")
      (footprint "eagle-import:C0603")
      (libsource (lib "eagle-import") (part "C-EU?C0603"))
    )
    (comp (ref "C137")
      (value "3n3")
      (footprint "eagle-import:C0603")
      (libsource (lib "eagle-import") (part "C-EU?C0603"))
    )
    (comp (ref "C138")
      (value "100n")
      (footprint "eagle-import:C0603")
      (libsource (lib "eagle-import") (part "C-EU?C0603"))
    )
    (comp (ref "C139")
      (value "1u")
      (footprint "eagle-import:C0603")
      (libsource (lib "eagle-import") (part "C-EU?C0603"))
    )
    (comp (ref "C140")
      (value "1u")
      (footprint "eagle-import:C0603")
      (libsource (lib "eagle-import") (part "C-EU?C0603"))
    )
    (comp (ref "C141")
      (value "10u")
      (footprint "eagle-import:C1206")
      (libsource (lib "eagle-import") (part "C-EUC1206"))
    )
    (comp (ref "C142")
      (value "10u")
      (footprint "eagle-import:C1206")
      (libsource (lib "eagle-import") (part "C-EUC1206"))
    )
    (comp (ref "C143")
      (value "100n")
      (footprint "eagle-import:C0603")
      (libsource (lib "eagle-import") (part "C-EU?C0603"))
    )
    (comp (ref "C144")
      (value "100n")
      (footprint "eagle-import:C0603")
      (libsource (lib "eagle-import") (part "C-EU?C0603"))
    )
    (comp (ref "C145")
      (value "100n")
      (footprint "eagle-import:C0603")
      (libsource (lib "eagle-import") (part "C-EU?C0603"))
    )
    (comp (ref "C146")
      (value "10n")
      (footprint "eagle-import:C0603")
      (libsource (lib "eagle-import") (part "C-EU?C0603"))
    )
    (comp (ref "C147")
      (value "10n")
      (footprint "eagle-import:C0603")
      (libsource (lib "eagle-import") (part "C-EU?C0603"))
    )
    (comp (ref "IC19")
      (value "MAX2871")
      (footprint "eagle-import:QFN50P500X500X80-33T310")
      (libsource (lib "eagle-import") (part "MAX2871"))
    )
    (comp (ref "IC20")
      (value "NCP702-3.3")
      (footprint "eagle-import:SOT95P240X110-5")
      (libsource (lib "eagle-import") (part "NCP702"))
    )
    (comp (ref "IC21")
      (value "AP2114H")
      (footprint "eagle-import:SOT230P700X180-4")
      (libsource (lib "eagle-import") (part "AP2114H"))
    )
    (comp (ref "L40")
      (value "Ferrite")
      (footprint "eagle-import:R0603")
      (libsource (lib "eagle-import") (part "INDUCTOR0603"))
    )
    (comp (ref "L41")
      (value "Ferrite")
      (footprint "eagle-import:R0603")
      (libsource (lib "eagle-import") (part "INDUCTOR0603"))
    )
    (comp (ref "R58")
      (value "1k8")
      (footprint "eagle-import:R0603")
      (libsource (lib "eagle-import") (part "R-EU_R0603"))
    )
    (comp (ref "R59")
      (value "82")
      (footprint "eagle-import:R0603")
      (libsource (lib "eagle-import") (part "R-EU_R0603"))
    )
    (comp (ref "R60")
      (value "330")
      (footprint "eagle-import:R0603")
      (libsource (lib "eagle-import") (part "R-EU_R0603"))
    )
    (comp (ref "R61")
      (value "5k1")
      (footprint "eagle-import:R0603")
      (libsource (lib "eagle-import") (part "R-EU_R0603"))
    )
    (comp (ref "R62")
      (value "49R9")
      (footprint "eagle-import:R0603")
      (libsource (lib "eagle-import") (part "R-EU_R0603"))
    )
    (comp (ref "R63")
      (value "49R9")
      (footprint "eagle-import:R0603")
      (libsource (lib "eagle-import") (part "R-EU_R0603"))
    )
    (comp (ref "R64")
      (value "10k")
      (footprint "eagle-import:R0603")
      (libsource (lib "eagle-import") (part "R-EU_R0603"))
    )
    (comp (ref "R65")
      (value "49R9")
      (footprint "eagle-import:R0603")
      (libsource (lib "eagle-import") (part "R-EU_R0603"))
    )
    (comp (ref "R66")
      (value "49R9")
      (footprint "eagle-import:R0603")
      (libsource (lib "eagle-import") (part "R-EU_R0603"))
    )
    (comp (ref "R67")
      (value "49R9")
      (footprint "eagle-import:R0603")
      (libsource (lib "eagle-import") (part "R-EU_R0603"))
    )
    (comp (ref "TP18")
      (value "TPB1,27")
      (footprint "eagle-import:B1,27")
      (libsource (lib "eagle-import") (part "TPB1,27"))
    )
    (comp (ref "TP19")
      (value "TPB1,27")
      (footprint "eagle-import:B1,27")
      (libsource (lib "eagle-import") (part "TPB1,27"))
    )
    (comp (ref "C65")
      (value "10n")
      (footprint "eagle-import:C0603")
      (libsource (lib "eagle-import") (part "C-EU?C0603"))
    )
    (comp (ref "C97")
      (value "18p")
      (footprint "eagle-import:C0603")
      (libsource (lib "eagle-import") (part "C-EU?C0603"))
    )
    (comp (ref "C98")
      (value "56p")
      (footprint "eagle-import:C0603")
      (libsource (lib "eagle-import") (part "C-EU?C0603"))
    )
    (comp (ref "C99")
      (value "18p")
      (footprint "eagle-import:C0603")
      (libsource (lib "eagle-import") (part "C-EU?C0603"))
    )
    (comp (ref "C100")
      (value "18p")
      (footprint "eagle-import:C0603")
      (libsource (lib "eagle-import") (part "C-EU?C0603"))
    )
    (comp (ref "C101")
      (value "56p")
      (footprint "eagle-import:C0603")
      (libsource (lib "eagle-import") (part "C-EU?C0603"))
    )
    (comp (ref "C102")
      (value "18p")
      (footprint "eagle-import:C0603")
      (libsource (lib "eagle-import") (part "C-EU?C0603"))
    )
    (comp (ref "C103")
      (value "18p")
      (footprint "eagle-import:C0603")
      (libsource (lib "eagle-import") (part "C-EU?C0603"))
    )
    (comp (ref "C104")
      (value "100n")
      (footprint "eagle-import:C0603")
      (libsource (lib "eagle-import") (part "C-EU?C0603"))
    )
    (comp (ref "C105")
      (value "100n")
      (footprint "eagle-import:C0603")
      (libsource (lib "eagle-import") (part "C-EU?C0603"))
    )
    (comp (ref "C107")
      (value "10n")
      (footprint "eagle-import:C0603")
      (libsource (lib "eagle-import") (part "C-EU?C0603"))
    )
    (comp (ref "C108")
      (value "4p")
      (footprint "eagle-import:C0603")
      (libsource (lib "eagle-import") (part "C-EU?C0603"))
    )
    (comp (ref "C109")
      (value "4p")
      (footprint "eagle-import:C0603")
      (libsource (lib "eagle-import") (part "C-EU?C0603"))
    )
    (comp (ref "C110")
      (value "100n")
      (footprint "eagle-import:C0603")
      (libsource (lib "eagle-import") (part "C-EU?C0603"))
    )
    (comp (ref "C111")
      (value "56p")
      (footprint "eagle-import:C0603")
      (libsource (lib "eagle-import") (part "C-EU?C0603"))
    )
    (comp (ref "C112")
      (value "18p")
      (footprint "eagle-import:C0603")
      (libsource (lib "eagle-import") (part "C-EU?C0603"))
    )
    (comp (ref "C157")
      (value "100n")
      (footprint "eagle-import:C0603")
      (libsource (lib "eagle-import") (part "C-EU?C0603"))
    )
    (comp (ref "IC13")
      (value "SI5351C")
      (footprint "eagle-import:QFN50P400X400X90-21T270N")
      (libsource (lib "eagle-import") (part "SI5351C"))
    )
    (comp (ref "J1")
      (value "U.FL-R-SMT")
      (footprint "eagle-import:U.FL_SMT")
      (fields (field (name "MANUFACTURER") "Hirose") (field (name "MPN") "U.FL-R-SMT-1(01)"))
      (libsource (lib "eagle-import") (part "U.FL-R-SMT"))
    )
    (comp (ref "J2")
      (value "U.FL-R-SMT")
      (footprint "eagle-import:U.FL_SMT")
      (fields (field (name "MANUFACTURER") "Hirose") (field (name "MPN") "U.FL-R-SMT-1(01)"))
      (libsource (lib "eagle-import") (part "U.FL-R-SMT"))
    )
    (comp (ref "L31")
      (value "Ferrite")
      (footprint "eagle-import:R0603")
      (libsource (lib "eagle-import") (part "INDUCTOR0603"))
    )
    (comp (ref "L32")
      (value "120n")
      (footprint "eagle-import:R0603")
      (libsource (lib "eagle-import") (part "INDUCTOR0603"))
    )
    (comp (ref "L33")
      (value "120n")
      (footprint "eagle-import:R0603")
      (libsource (lib "eagle-import") (part "INDUCTOR0603"))
    )
    (comp (ref "L34")
      (value "120n")
      (footprint "eagle-import:R0603")
      (libsource (lib "eagle-import") (part "INDUCTOR0603"))
    )
    (comp (ref "L35")
      (value "120n")
      (footprint "eagle-import:R0603")
      (libsource (lib "eagle-import") (part "INDUCTOR0603"))
    )
    (comp (ref "L36")
      (value "120n")
      (footprint "eagle-import:R0603")
      (libsource (lib "eagle-import") (part "INDUCTOR0603"))
    )
    (comp (ref "L37")
      (value "120n")
      (footprint "eagle-import:R0603")
      (libsource (lib "eagle-import") (part "INDUCTOR0603"))
    )
    (comp (ref "Q1")
      (value "FA-128 26MHz")
      (footprint "eagle-import:FA-128")
      (libsource (lib "eagle-import") (part "FA-128"))
    )
    (comp (ref "R49")
      (value "10k")
      (footprint "eagle-import:R0603")
      (libsource (lib "eagle-import") (part "R-EU_R0603"))
    )
    (comp (ref "R73")
      (value "100")
      (footprint "eagle-import:R0603")
      (libsource (lib "eagle-import") (part "R-EU_R0603"))
    )
    (comp (ref "R74")
      (value "62")
      (footprint "eagle-import:R0603")
      (libsource (lib "eagle-import") (part "R-EU_R0603"))
    )
    (comp (ref "R75")
      (value "100")
      (footprint "eagle-import:R0603")
      (libsource (lib "eagle-import") (part "R-EU_R0603"))
    )
    (comp (ref "C66")
      (value "100n")
      (footprint "eagle-import:C0603")
      (libsource (lib "eagle-import") (part "C-EU?C0603"))
    )
    (comp (ref "C67")
      (value "100n")
      (footprint "eagle-import:C0603")
      (libsource (lib "eagle-import") (part "C-EU?C0603"))
    )
    (comp (ref "C68")
      (value "100n")
      (footprint "eagle-import:C0603")
      (libsource (lib "eagle-import") (part "C-EU?C0603"))
    )
    (comp (ref "C69")
      (value "DNP")
      (footprint "eagle-import:C0603")
      (libsource (lib "eagle-import") (part "C-EU?C0603"))
    )
    (comp (ref "C70")
      (value "100n")
      (footprint "eagle-import:C0603")
      (libsource (lib "eagle-import") (part "C-EU?C0603"))
    )
    (comp (ref "C71")
      (value "100n")
      (footprint "eagle-import:C0603")
      (libsource (lib "eagle-import") (part "C-EU?C0603"))
    )
    (comp (ref "C72")
      (value "10n")
      (footprint "eagle-import:C0603")
      (libsource (lib "eagle-import") (part "C-EU?C0603"))
    )
    (comp (ref "C73")
      (value "1u")
      (footprint "eagle-import:C0603")
      (libsource (lib "eagle-import") (part "C-EU?C0603"))
    )
    (comp (ref "C74")
      (value "10n")
      (footprint "eagle-import:C0603")
      (libsource (lib "eagle-import") (part "C-EU?C0603"))
    )
    (comp (ref "C75")
      (value "100n")
      (footprint "eagle-import:C0603")
      (libsource (lib "eagle-import") (part "C-EU?C0603"))
    )
    (comp (ref "C76")
      (value "100n")
      (footprint "eagle-import:C0603")
      (libsource (lib "eagle-import") (part "C-EU?C0603"))
    )
    (comp (ref "C77")
      (value "100n")
      (footprint "eagle-import:C0603")
      (libsource (lib "eagle-import") (part "C-EU?C0603"))
    )
    (comp (ref "C78")
      (value "1u")
      (footprint "eagle-import:C0603")
      (libsource (lib "eagle-import") (part "C-EU?C0603"))
    )
    (comp (ref "C79")
      (value "1u")
      (footprint "eagle-import:C0603")
      (libsource (lib "eagle-import") (part "C-EU?C0603"))
    )
    (comp (ref "C80")
      (value "100n")
      (footprint "eagle-import:C0603")
      (libsource (lib "eagle-import") (part "C-EU?C0603"))
    )
    (comp (ref "C81")
      (value "100n")
      (footprint "eagle-import:C0603")
      (libsource (lib "eagle-import") (part "C-EU?C0603"))
    )
    (comp (ref "C82")
      (value "DNP")
      (footprint "eagle-import:C0603")
      (libsource (lib "eagle-import") (part "C-EU?C0603"))
    )
    (comp (ref "C83")
      (value "DNP")
      (footprint "eagle-import:C0603")
      (libsource (lib "eagle-import") (part "C-EU?C0603"))
    )
    (comp (ref "C84")
      (value "100n")
      (footprint "eagle-import:C0603")
      (libsource (lib "eagle-import") (part "C-EU?C0603"))
    )
    (comp (ref "C85")
      (value "330p")
      (footprint "eagle-import:C0603")
      (libsource (lib "eagle-import") (part "C-EU?C0603"))
    )
    (comp (ref "C86")
      (value "100n")
      (footprint "eagle-import:C0603")
      (libsource (lib "eagle-import") (part "C-EU?C0603"))
    )
    (comp (ref "C87")
      (value "10n")
      (footprint "eagle-import:C0603")
      (libsource (lib "eagle-import") (part "C-EU?C0603"))
    )
    (comp (ref "C88")
      (value "120p")
      (footprint "eagle-import:C0603")
      (libsource (lib "eagle-import") (part "C-EU?C0603"))
    )
    (comp (ref "C89")
      (value "150p")
      (footprint "eagle-import:C0603")
      (libsource (lib "eagle-import") (part "C-EU?C0603"))
    )
    (comp (ref "C90")
      (value "33p")
      (footprint "eagle-import:C0603")
      (libsource (lib "eagle-import") (part "C-EU?C0603"))
    )
    (comp (ref "C91")
      (value "100n")
      (footprint "eagle-import:C0603")
      (libsource (lib "eagle-import") (part "C-EU?C0603"))
    )
    (comp (ref "C92")
      (value "330p")
      (footprint "eagle-import:C0603")
      (libsource (lib "eagle-import") (part "C-EU?C0603"))
    )
    (comp (ref "C93")
      (value "330p")
      (footprint "eagle-import:C0603")
      (libsource (lib "eagle-import") (part "C-EU?C0603"))
    )
    (comp (ref "C94")
      (value "330p")
      (footprint "eagle-import:C0603")
      (libsource (lib "eagle-import") (part "C-EU?C0603"))
    )
    (comp (ref "C95")
      (value "1u")
      (footprint "eagle-import:C0603")
      (libsource (lib "eagle-import") (part "C-EU?C0603"))
    )
    (comp (ref "C96")
      (value "100n")
      (footprint "eagle-import:C0603")
      (libsource (lib "eagle-import") (part "C-EU?C0603"))
    )
    (comp (ref "C195")
      (value "1u")
      (footprint "eagle-import:C0603")
      (libsource (lib "eagle-import") (part "C-EU?C0603"))
    )
    (comp (ref "IC9")
      (value "LTC5510")
      (footprint "eagle-import:QFN65P400X400X75-17T215N")
      (libsource (lib "eagle-import") (part "LTC5510"))
    )
    (comp (ref "IC10")
      (value "LT5560")
      (footprint "eagle-import:SON50P300X300X80-9T165X238")
      (libsource (lib "eagle-import") (part "LT5560"))
    )
    (comp (ref "IC11")
      (value "LTC6362")
      (footprint "eagle-import:SON50P300X300X80-9T165X238")
      (libsource (lib "eagle-import") (part "LTC6362"))
    )
    (comp (ref "IC12")
      (value "MCP33131D-10-E/MS")
      (footprint "eagle-import:SOP50P490X110-10N")
      (libsource (lib "eagle-import") (part "MCP33131D-10-E/MS"))
    )
    (comp (ref "IC36")
      (value "NCP702-1.8")
      (footprint "eagle-import:SOT95P240X110-5")
      (libsource (lib "eagle-import") (part "NCP702"))
    )
    (comp (ref "L21")
      (value "330n")
      (footprint "eagle-import:R0603")
      (libsource (lib "eagle-import") (part "INDUCTOR0603"))
    )
    (comp (ref "L22")
      (value "330n")
      (footprint "eagle-import:R0603")
      (libsource (lib "eagle-import") (part "INDUCTOR0603"))
    )
    (comp (ref "L23")
      (value "68n")
      (footprint "eagle-import:R0603")
      (libsource (lib "eagle-import") (part "INDUCTOR0603"))
    )
    (comp (ref "L24")
      (value "68n")
      (footprint "eagle-import:R0603")
      (libsource (lib "eagle-import") (part "INDUCTOR0603"))
    )
    (comp (ref "L25")
      (value "33n")
      (footprint "eagle-import:R0603")
      (libsource (lib "eagle-import") (part "INDUCTOR0603"))
    )
    (comp (ref "L26")
      (value "33n")
      (footprint "eagle-import:R0603")
      (libsource (lib "eagle-import") (part "INDUCTOR0603"))
    )
    (comp (ref "L27")
      (value "330n")
      (footprint "eagle-import:R0603")
      (libsource (lib "eagle-import") (part "INDUCTOR0603"))
    )
    (comp (ref "L28")
      (value "330n")
      (footprint "eagle-import:R0603")
      (libsource (lib "eagle-import") (part "INDUCTOR0603"))
    )
    (comp (ref "L29")
      (value "220Ohm")
      (footprint "eagle-import:R0603")
      (libsource (lib "eagle-import") (part "INDUCTOR0603"))
    )
    (comp (ref "L30")
      (value "220Ohm")
      (footprint "eagle-import:R0603")
      (libsource (lib "eagle-import") (part "INDUCTOR0603"))
    )
    (comp (ref "R41")
      (value "DNP")
      (footprint "eagle-import:R0603")
      (libsource (lib "eagle-import") (part "R-EU_R0603"))
    )
    (comp (ref "R43")
      (value "200")
      (footprint "eagle-import:R0603")
      (libsource (lib "eagle-import") (part "R-EU_R0603"))
    )
    (comp (ref "R44")
      (value "200")
      (footprint "eagle-import:R0603")
      (libsource (lib "eagle-import") (part "R-EU_R0603"))
    )
    (comp (ref "R45")
      (value "4k7")
      (footprint "eagle-import:R0603")
      (libsource (lib "eagle-import") (part "R-EU_R0603"))
    )
    (comp (ref "R46")
      (value "4k7")
      (footprint "eagle-import:R0603")
      (libsource (lib "eagle-import") (part "R-EU_R0603"))
    )
    (comp (ref "R47")
      (value "220")
      (footprint "eagle-import:R0603")
      (libsource (lib "eagle-import") (part "R-EU_R0603"))
    )
    (comp (ref "R48")
      (value "220")
      (footprint "eagle-import:R0603")
      (libsource (lib "eagle-import") (part "R-EU_R0603"))
    )
    (comp (ref "T3")
      (value "MABA011082")
      (footprint "eagle-import:MACOM_BALUN")
      (libsource (lib "eagle-import") (part "MABA011082"))
    )
    (comp (ref "TP15")
      (value "TPB1,27")
      (footprint "eagle-import:B1,27")
      (libsource (lib "eagle-import") (part "TPB1,27"))
    )
    (comp (ref "C148")
      (value "100n")
      (footprint "eagle-import:C0603")
      (libsource (lib "eagle-import") (part "C-EU?C0603"))
    )
    (comp (ref "C149")
      (value "100n")
      (footprint "eagle-import:C0603")
      (libsource (lib "eagle-import") (part "C-EU?C0603"))
    )
    (comp (ref "C150")
      (value "100n")
      (footprint "eagle-import:C0603")
      (libsource (lib "eagle-import") (part "C-EU?C0603"))
    )
    (comp (ref "C151")
      (value "100n")
      (footprint "eagle-import:C0603")
      (libsource (lib "eagle-import") (part "C-EU?C0603"))
    )
    (comp (ref "C152")
      (value "100n")
      (footprint "eagle-import:C0603")
      (libsource (lib "eagle-import") (part "C-EU?C0603"))
    )
    (comp (ref "C153")
      (value "100n")
      (footprint "eagle-import:C0603")
      (libsource (lib "eagle-import") (part "C-EU?C0603"))
    )
    (comp (ref "C154")
      (value "100n")
      (footprint "eagle-import:C0603")
      (libsource (lib "eagle-import") (part "C-EU?C0603"))
    )
    (comp (ref "C155")
      (value "100n")
      (footprint "eagle-import:C0603")
      (libsource (lib "eagle-import") (part "C-EU?C0603"))
    )
    (comp (ref "C156")
      (value "100n")
      (footprint "eagle-import:C0603")
      (libsource (lib "eagle-import") (part "C-EU?C0603"))
    )
    (comp (ref "IC22")
      (value "F2912")
      (footprint "eagle-import:QFN50P400X400X75-21T206")
      (libsource (lib "eagle-import") (part "F2912"))
    )
    (comp (ref "IC23")
      (value "F1958")
      (footprint "eagle-import:QFN50P400X400X75-25T270")
      (libsource (lib "eagle-import") (part "F1958"))
    )
    (comp (ref "IC24")
      (value "TRF37A73")
      (footprint "eagle-import:SON50P200X200X80-9T90X160N")
      (libsource (lib "eagle-import") (part "TRF37A73"))
    )
    (comp (ref "IC25")
      (value "F2912")
      (footprint "eagle-import:QFN50P400X400X75-21T206")
      (libsource (lib "eagle-import") (part "F2912"))
    )
    (comp (ref "IC26")
      (value "F2912")
      (footprint "eagle-import:QFN50P400X400X75-21T206")
      (libsource (lib "eagle-import") (part "F2912"))
    )
    (comp (ref "IC27")
      (value "F2912")
      (footprint "eagle-import:QFN50P400X400X75-21T206")
      (libsource (lib "eagle-import") (part "F2912"))
    )
    (comp (ref "L42")
      (value "Ferrite")
      (footprint "eagle-import:R0603")
      (libsource (lib "eagle-import") (part "INDUCTOR0603"))
    )
    (comp (ref "L43")
      (value "Ferrite")
      (footprint "eagle-import:R0603")
      (libsource (lib "eagle-import") (part "INDUCTOR0603"))
    )
    (comp (ref "L44")
      (value "330n")
      (footprint "eagle-import:R0603")
      (libsource (lib "eagle-import") (part "INDUCTOR0603"))
    )
    (comp (ref "L45")
      (value "Ferrite")
      (footprint "eagle-import:R0603")
      (libsource (lib "eagle-import") (part "INDUCTOR0603"))
    )
    (comp (ref "L46")
      (value "Ferrite")
      (footprint "eagle-import:R0603")
      (libsource (lib "eagle-import") (part "INDUCTOR0603"))
    )
    (comp (ref "R68")
      (value "0")
      (footprint "eagle-import:R0603")
      (libsource (lib "eagle-import") (part "R-EU_R0603"))
    )
    (comp (ref "R69")
      (value "2R7")
      (footprint "eagle-import:R0603")
      (libsource (lib "eagle-import") (part "R-EU_R0603"))
    )
    (comp (ref "R70")
      (value "2R7")
      (footprint "eagle-import:R0603")
      (libsource (lib "eagle-import") (part "R-EU_R0603"))
    )
    (comp (ref "R71")
      (value "406")
      (footprint "eagle-import:R0603")
      (libsource (lib "eagle-import") (part "R-EU_R0603"))
    )
    (comp (ref "R72")
      (value "56")
      (footprint "eagle-import:R0603")
      (libsource (lib "eagle-import") (part "R-EU_R0603"))
    )
    (comp (ref "C114")
      (value "1u")
      (footprint "eagle-import:C0603")
      (libsource (lib "eagle-import") (part "C-EU?C0603"))
    )
    (comp (ref "C115")
      (value "1u")
      (footprint "eagle-import:C0603")
      (libsource (lib "eagle-import") (part "C-EU?C0603"))
    )
    (comp (ref "C116")
      (value "1u")
      (footprint "eagle-import:C0603")
      (libsource (lib "eagle-import") (part "C-EU?C0603"))
    )
    (comp (ref "C117")
      (value "180p")
      (footprint "eagle-import:C0603")
      (libsource (lib "eagle-import") (part "C-EU?C0603"))
    )
    (comp (ref "C118")
      (value "18p")
      (footprint "eagle-import:C0603")
      (libsource (lib "eagle-import") (part "C-EU?C0603"))
    )
    (comp (ref "C119")
      (value "3n3")
      (footprint "eagle-import:C0603")
      (libsource (lib "eagle-import") (part "C-EU?C0603"))
    )
    (comp (ref "C120")
      (value "100n")
      (footprint "eagle-import:C0603")
      (libsource (lib "eagle-import") (part "C-EU?C0603"))
    )
    (comp (ref "C121")
      (value "10n")
      (footprint "eagle-import:C0603")
      (libsource (lib "eagle-import") (part "C-EU?C0603"))
    )
    (comp (ref "C123")
      (value "1u")
      (footprint "eagle-import:C0603")
      (libsource (lib "eagle-import") (part "C-EU?C0603"))
    )
    (comp (ref "C124")
      (value "1u")
      (footprint "eagle-import:C0603")
      (libsource (lib "eagle-import") (part "C-EU?C0603"))
    )
    (comp (ref "C125")
      (value "10u")
      (footprint "eagle-import:C1206")
      (libsource (lib "eagle-import") (part "C-EUC1206"))
    )
    (comp (ref "C126")
      (value "10u")
      (footprint "eagle-import:C1206")
      (libsource (lib "eagle-import") (part "C-EUC1206"))
    )
    (comp (ref "C127")
      (value "100n")
      (footprint "eagle-import:C0603")
      (libsource (lib "eagle-import") (part "C-EU?C0603"))
    )
    (comp (ref "C128")
      (value "100n")
      (footprint "eagle-import:C0603")
      (libsource (lib "eagle-import") (part "C-EU?C0603"))
    )
    (comp (ref "C129")
      (value "100n")
      (footprint "eagle-import:C0603")
      (libsource (lib "eagle-import") (part "C-EU?C0603"))
    )
    (comp (ref "C130")
      (value "10n")
      (footprint "eagle-import:C0603")
      (libsource (lib "eagle-import") (part "C-EU?C0603"))
    )
    (comp (ref "C131")
      (value "10n")
      (footprint "eagle-import:C0603")
      (libsource (lib "eagle-import") (part "C-EU?C0603"))
    )
    (comp (ref "C132")
      (value "10n")
      (footprint "eagle-import:C0603")
      (libsource (lib "eagle-import") (part "C-EU?C0603"))
    )
    (comp (ref "IC14")
      (value "MAX2871")
      (footprint "eagle-import:QFN50P500X500X80-33T310")
      (libsource (lib "eagle-import") (part "MAX2871"))
    )
    (comp (ref "IC15")
      (value "NCP702-3.3")
      (footprint "eagle-import:SOT95P240X110-5")
      (libsource (lib "eagle-import") (part "NCP702"))
    )
    (comp (ref "IC16")
      (value "RFSW6042")
      (footprint "eagle-import:QFN40P180X180X55-13T76N")
      (libsource (lib "eagle-import") (part "RFSW6042"))
    )
    (comp (ref "IC17")
      (value "AP2114H")
      (footprint "eagle-import:SOT230P700X180-4")
      (libsource (lib "eagle-import") (part "AP2114H"))
    )
    (comp (ref "IC18")
      (value "RFSW6042")
      (footprint "eagle-import:QFN40P180X180X55-13T76N")
      (libsource (lib "eagle-import") (part "RFSW6042"))
    )
    (comp (ref "L38")
      (value "Ferrite")
      (footprint "eagle-import:R0603")
      (libsource (lib "eagle-import") (part "INDUCTOR0603"))
    )
    (comp (ref "L39")
      (value "Ferrite")
      (footprint "eagle-import:R0603")
      (libsource (lib "eagle-import") (part "INDUCTOR0603"))
    )
    (comp (ref "LP1")
      (value "LP0603A0947ANTR")
      (footprint "eagle-import:FILTRDFN160X84X70-4N")
      (libsource (lib "eagle-import") (part "LP0603A"))
    )
    (comp (ref "LP2")
      (value "LP0603A1880ANTR")
      (footprint "eagle-import:FILTRDFN160X84X70-4N")
      (libsource (lib "eagle-import") (part "LP0603A"))
    )
    (comp (ref "LP3")
      (value "LP0603N3500ANTR")
      (footprint "eagle-import:FILTRDFN160X84X70-4N")
      (libsource (lib "eagle-import") (part "LP0603A"))
    )
    (comp (ref "R50")
      (value "1k8")
      (footprint "eagle-import:R0603")
      (libsource (lib "eagle-import") (part "R-EU_R0603"))
    )
    (comp (ref "R51")
      (value "82")
      (footprint "eagle-import:R0603")
      (libsource (lib "eagle-import") (part "R-EU_R0603"))
    )
    (comp (ref "R52")
      (value "330")
      (footprint "eagle-import:R0603")
      (libsource (lib "eagle-import") (part "R-EU_R0603"))
    )
    (comp (ref "R53")
      (value "5k1")
      (footprint "eagle-import:R0603")
      (libsource (lib "eagle-import") (part "R-EU_R0603"))
    )
    (comp (ref "R54")
      (value "49R9")
      (footprint "eagle-import:R0603")
      (libsource (lib "eagle-import") (part "R-EU_R0603"))
    )
    (comp (ref "R55")
      (value "49R9")
      (footprint "eagle-import:R0603")
      (libsource (lib "eagle-import") (part "R-EU_R0603"))
    )
    (comp (ref "R56")
      (value "10k")
      (footprint "eagle-import:R0603")
      (libsource (lib "eagle-import") (part "R-EU_R0603"))
    )
    (comp (ref "R57")
      (value "49R9")
      (footprint "eagle-import:R0603")
      (libsource (lib "eagle-import") (part "R-EU_R0603"))
    )
    (comp (ref "R97")
      (value "10k")
      (footprint "eagle-import:R0603")
      (libsource (lib "eagle-import") (part "R-EU_R0603"))
    )
    (comp (ref "R98")
      (value "10k")
      (footprint "eagle-import:R0603")
      (libsource (lib "eagle-import") (part "R-EU_R0603"))
    )
    (comp (ref "R99")
      (value "10k")
      (footprint "eagle-import:R0603")
      (libsource (lib "eagle-import") (part "R-EU_R0603"))
    )
    (comp (ref "R100")
      (value "10k")
      (footprint "eagle-import:R0603")
      (libsource (lib "eagle-import") (part "R-EU_R0603"))
    )
    (comp (ref "R101")
      (value "10k")
      (footprint "eagle-import:R0603")
      (libsource (lib "eagle-import") (part "R-EU_R0603"))
    )
    (comp (ref "R102")
      (value "10k")
      (footprint "eagle-import:R0603")
      (libsource (lib "eagle-import") (part "R-EU_R0603"))
    )
    (comp (ref "R103")
      (value "10k")
      (footprint "eagle-import:R0603")
      (libsource (lib "eagle-import") (part "R-EU_R0603"))
    )
    (comp (ref "R104")
      (value "10k")
      (footprint "eagle-import:R0603")
      (libsource (lib "eagle-import") (part "R-EU_R0603"))
    )
    (comp (ref "TP16")
      (value "TPB1,27")
      (footprint "eagle-import:B1,27")
      (libsource (lib "eagle-import") (part "TPB1,27"))
    )
    (comp (ref "TP17")
      (value "TPB1,27")
      (footprint "eagle-import:B1,27")
      (libsource (lib "eagle-import") (part "TPB1,27"))
    )
    (comp (ref "C191")
      (value "100n")
      (footprint "eagle-import:C0603")
      (libsource (lib "eagle-import") (part "C-EU?C0603"))
    )
    (comp (ref "C192")
      (value "100n")
      (footprint "eagle-import:C0603")
      (libsource (lib "eagle-import") (part "C-EU?C0603"))
    )
    (comp (ref "C203")
      (value "100n")
      (footprint "eagle-import:C0603")
      (libsource (lib "eagle-import") (part "C-EU?C0603"))
    )
    (comp (ref "C204")
      (value "100n")
      (footprint "eagle-import:C0603")
      (libsource (lib "eagle-import") (part "C-EU?C0603"))
    )
    (comp (ref "C205")
      (value "100n")
      (footprint "eagle-import:C0603")
      (libsource (lib "eagle-import") (part "C-EU?C0603"))
    )
    (comp (ref "C206")
      (value "100n")
      (footprint "eagle-import:C0603")
      (libsource (lib "eagle-import") (part "C-EU?C0603"))
    )
    (comp (ref "C207")
      (value "100n")
      (footprint "eagle-import:C0603")
      (libsource (lib "eagle-import") (part "C-EU?C0603"))
    )
    (comp (ref "C208")
      (value "100n")
      (footprint "eagle-import:C0603")
      (libsource (lib "eagle-import") (part "C-EU?C0603"))
    )
    (comp (ref "C209")
      (value "100n")
      (footprint "eagle-import:C0603")
      (libsource (lib "eagle-import") (part "C-EU?C0603"))
    )
    (comp (ref "C210")
      (value "100n")
      (footprint "eagle-import:C0603")
      (libsource (lib "eagle-import") (part "C-EU?C0603"))
    )
    (comp (ref "C211")
      (value "100n")
      (footprint "eagle-import:C0603")
      (libsource (lib "eagle-import") (part "C-EU?C0603"))
    )
    (comp (ref "IC33")
      (value "STM32L432KC")
      (footprint "eagle-import:QFN50P500X500X100-33T345N")
      (libsource (lib "eagle-import") (part "STM32L432KC"))
    )
    (comp (ref "JP1")
      (value "PINHD-1X6")
      (footprint "eagle-import:1X06")
      (libsource (lib "eagle-import") (part "PINHD-1X6"))
    )
    (comp (ref "JTAG")
      (value "ML10")
      (footprint "eagle-import:ML10")
      (libsource (lib "eagle-import") (part "ML10"))
    )
    (comp (ref "R76")
      (value "22")
      (footprint "eagle-import:R0603")
      (libsource (lib "eagle-import") (part "R-EU_R0603"))
    )
    (comp (ref "R88")
      (value "22")
      (footprint "eagle-import:R0603")
      (libsource (lib "eagle-import") (part "R-EU_R0603"))
    )
    (comp (ref "R89")
      (value "1k5")
      (footprint "eagle-import:R0603")
      (libsource (lib "eagle-import") (part "R-EU_R0603"))
    )
    (comp (ref "R90")
      (value "10k")
      (footprint "eagle-import:R0603")
      (libsource (lib "eagle-import") (part "R-EU_R0603"))
    )
    (comp (ref "R91")
      (value "22")
      (footprint "eagle-import:R0603")
      (libsource (lib "eagle-import") (part "R-EU_R0603"))
    )
    (comp (ref "R92")
      (value "10k")
      (footprint "eagle-import:R0603")
      (libsource (lib "eagle-import") (part "R-EU_R0603"))
    )
    (comp (ref "R93")
      (value "10k")
      (footprint "eagle-import:R0603")
      (libsource (lib "eagle-import") (part "R-EU_R0603"))
    )
    (comp (ref "R94")
      (value "10k")
      (footprint "eagle-import:R0603")
      (libsource (lib "eagle-import") (part "R-EU_R0603"))
    )
    (comp (ref "R95")
      (value "10k")
      (footprint "eagle-import:R0603")
      (libsource (lib "eagle-import") (part "R-EU_R0603"))
    )
    (comp (ref "R111")
      (value "10k")
      (footprint "eagle-import:R0603")
      (libsource (lib "eagle-import") (part "R-EU_R0603"))
    )
    (comp (ref "U4")
      (value "W25Q16BVSN")
      (footprint "eagle-import:SO08")
      (libsource (lib "eagle-import") (part "W25Q16BVSN"))
    )
    (comp (ref "X4")
      (value "MINI-USB-SCHIELD-32005-301")
      (footprint "eagle-import:32005-301")
      (libsource (lib "eagle-import") (part "MINI-USB-SCHIELD-32005-301"))
    )
  )
  (nets
    (net (code "1") (name "+3V3") (class "Default")
      (node (ref "C110") (pin "2") (pinfunction "2_2") (pintype "passive"))
      (node (ref "C120") (pin "1") (pinfunction "1_1") (pintype "passive"))
      (node (ref "C127") (pin "1") (pinfunction "1_1") (pintype "passive"))
      (node (ref "C138") (pin "1") (pinfunction "1_1") (pintype "passive"))
      (node (ref "C143") (pin "1") (pinfunction "1_1") (pintype "passive"))
      (node (ref "C189") (pin "1") (pinfunction "1_1") (pintype "passive"))
      (node (ref "C190") (pin "1") (pinfunction "1_1") (pintype "passive"))
      (node (ref "C191") (pin "1") (pinfunction "1_1") (pintype "passive"))
      (node (ref "C192") (pin "1") (pinfunction "1_1") (pintype "passive"))
      (node (ref "C203") (pin "1") (pinfunction "1_1") (pintype "passive"))
      (node (ref "C204") (pin "1") (pinfunction "1_1") (pintype "passive"))
      (node (ref "C205") (pin "1") (pinfunction "1_1") (pintype "passive"))
      (node (ref "C206") (pin "1") (pinfunction "1_1") (pintype "passive"))
      (node (ref "C207") (pin "1") (pinfunction "1_1") (pintype "passive"))
      (node (ref "C29") (pin "2") (pinfunction "2_2") (pintype "passive"))
      (node (ref "C64") (pin "2") (pinfunction "2_2") (pintype "passive"))
      (node (ref "C96") (pin "2") (pinfunction "2_2") (pintype "passive"))
      (node (ref "IC12") (pin "10") (pinfunction "DVIO_10") (pintype "bidirectional"))
      (node (ref "IC12") (pin "9") (pinfunction "SDI_9") (pintype "bidirectional"))
      (node (ref "IC13") (pin "20") (pinfunction "VDD_20") (pintype "bidirectional"))
      (node (ref "IC14") (pin "28") (pinfunction "VCC_DIG_28") (pintype "bidirectional"))
      (node (ref "IC14") (pin "32") (pinfunction "VDD_SD_32") (pintype "bidirectional"))
      (node (ref "IC19") (pin "28") (pinfunction "VCC_DIG_28") (pintype "bidirectional"))
      (node (ref "IC19") (pin "32") (pinfunction "VDD_SD_32") (pintype "bidirectional"))
      (node (ref "IC33") (pin "1") (pinfunction "VDD1_1") (pintype "bidirectional"))
      (node (ref "IC33") (pin "17") (pinfunction "VDD2_17") (pintype "bidirectional"))
      (node (ref "IC33") (pin "5") (pinfunction "VDDA/VREF+_5") (pintype "bidirectional"))
      (node (ref "IC4") (pin "10") (pinfunction "DVIO_10") (pintype "bidirectional"))
      (node (ref "IC4") (pin "9") (pinfunction "SDI_9") (pintype "bidirectional"))
      (node (ref "IC8") (pin "10") (pinfunction "DVIO_10") (pintype "bidirectional"))
      (node (ref "IC8") (pin "9") (pinfunction "SDI_9") (pintype "bidirectional"))
      (node (ref "JP1") (pin "1") (pinfunction "1_1") (pintype "passive"))
      (node (ref "JTAG") (pin "4") (pinfunction "4_4") (pintype "passive"))
      (node (ref "L31") (pin "1") (pinfunction "1_1") (pintype "passive"))
      (node (ref "L42") (pin "1") (pinfunction "1_1") (pintype "passive"))
      (node (ref "L43") (pin "1") (pinfunction "1_1") (pintype "passive"))
      (node (ref "L45") (pin "1") (pinfunction "1_1") (pintype "passive"))
      (node (ref "L46") (pin "1") (pinfunction "1_1") (pintype "passive"))
      (node (ref "L55") (pin "P$2") (pinfunction "2_P$2") (pintype "passive"))
      (node (ref "LED1") (pin "A") (pinfunction "A_A") (pintype "passive"))
      (node (ref "LED2") (pin "A") (pinfunction "A_A") (pintype "passive"))
      (node (ref "LED3") (pin "A") (pinfunction "A_A") (pintype "passive"))
      (node (ref "LED4") (pin "A") (pinfunction "A_A") (pintype "passive"))
      (node (ref "LED5") (pin "A") (pinfunction "A_A") (pintype "passive"))
      (node (ref "LED6") (pin "A") (pinfunction "A_A") (pintype "passive"))
      (node (ref "LED7") (pin "A") (pinfunction "A_A") (pintype "passive"))
      (node (ref "LED8") (pin "A") (pinfunction "A_A") (pintype "passive"))
      (node (ref "LED9") (pin "A") (pinfunction "A_A") (pintype "passive"))
      (node (ref "R90") (pin "2") (pinfunction "2_2") (pintype "passive"))
      (node (ref "R92") (pin "2") (pinfunction "2_2") (pintype "passive"))
      (node (ref "R93") (pin "2") (pinfunction "2_2") (pintype "passive"))
      (node (ref "R94") (pin "2") (pinfunction "2_2") (pintype "passive"))
      (node (ref "R95") (pin "2") (pinfunction "2_2") (pintype "passive"))
      (node (ref "TP3") (pin "TP") (pinfunction "TP_TP") (pintype "input"))
      (node (ref "U2") (pin "P103") (pinfunction "VCCO_1_P103") (pintype "input"))
      (node (ref "U2") (pin "P122") (pinfunction "VCCO_0_P122") (pintype "input"))
      (node (ref "U2") (pin "P125") (pinfunction "VCCO_0_P125") (pintype "input"))
      (node (ref "U2") (pin "P129") (pinfunction "VCCAUX_P129") (pintype "input"))
      (node (ref "U2") (pin "P135") (pinfunction "VCCO_0_P135") (pintype "input"))
      (node (ref "U2") (pin "P18") (pinfunction "VCCO_3_P18") (pintype "input"))
      (node (ref "U2") (pin "P20") (pinfunction "VCCAUX_P20") (pintype "input"))
      (node (ref "U2") (pin "P31") (pinfunction "VCCO_3_P31") (pintype "input"))
      (node (ref "U2") (pin "P36") (pinfunction "VCCAUX_P36") (pintype "input"))
      (node (ref "U2") (pin "P4") (pinfunction "VCCO_3_P4") (pintype "input"))
      (node (ref "U2") (pin "P42") (pinfunction "VCCO_2_P42") (pintype "input"))
      (node (ref "U2") (pin "P53") (pinfunction "VCCAUX_P53") (pintype "input"))
      (node (ref "U2") (pin "P63") (pinfunction "VCCO_2_P63") (pintype "input"))
      (node (ref "U2") (pin "P69") (pinfunction "IO_L1N_M0_CMPMISO_2_P69") (pintype "bidirectional"))
      (node (ref "U2") (pin "P76") (pinfunction "VCCO_1_P76") (pintype "input"))
      (node (ref "U2") (pin "P86") (pinfunction "VCCO_1_P86") (pintype "input"))
      (node (ref "U2") (pin "P90") (pinfunction "VCCAUX_P90") (pintype "input"))
      (node (ref "U4") (pin "3") (pinfunction "~{WP}_3") (pintype "input"))
      (node (ref "U4") (pin "7") (pinfunction "~{HOLD}_7") (pintype "input"))
      (node (ref "U4") (pin "8") (pinfunction "VCC_8") (pintype "power_in"))
    )
    (net (code "2") (name "+5V{slash}1") (class "Default")
      (node (ref "C12") (pin "1") (pinfunction "1_1") (pintype "passive"))
      (node (ref "C13") (pin "1") (pinfunction "1_1") (pintype "passive"))
      (node (ref "C164") (pin "2") (pinfunction "2_2") (pintype "passive"))
      (node (ref "C193") (pin "1") (pinfunction "1_1") (pintype "passive"))
      (node (ref "C22") (pin "2") (pinfunction "2_2") (pintype "passive"))
      (node (ref "C23") (pin "2") (pinfunction "2_2") (pintype "passive"))
      (node (ref "C30") (pin "2") (pinfunction "2_2") (pintype "passive"))
      (node (ref "C8") (pin "1") (pinfunction "1_1") (pintype "passive"))
      (node (ref "C9") (pin "1") (pinfunction "1_1") (pintype "passive"))
      (node (ref "IC1") (pin "6") (pinfunction "VCC1_6") (pintype "bidirectional"))
      (node (ref "IC1") (pin "7") (pinfunction "VCC2_7") (pintype "bidirectional"))
      (node (ref "IC2") (pin "7") (pinfunction "VCC_7") (pintype "bidirectional"))
      (node (ref "IC3") (pin "3") (pinfunction "V+_3") (pintype "power_in"))
      (node (ref "IC34") (pin "1") (pinfunction "VIN_1") (pintype "power_in"))
      (node (ref "IC34") (pin "3") (pinfunction "EN_3") (pintype "input"))
      (node (ref "IC4") (pin "1") (pinfunction "VREF_1") (pintype "bidirectional"))
      (node (ref "L1") (pin "1") (pinfunction "1_1") (pintype "passive"))
      (node (ref "L2") (pin "1") (pinfunction "1_1") (pintype "passive"))
      (node (ref "L47") (pin "2") (pinfunction "2_2") (pintype "passive"))
      (node (ref "R15") (pin "1") (pinfunction "1_1") (pintype "passive"))
      (node (ref "R16") (pin "1") (pinfunction "1_1") (pintype "passive"))
      (node (ref "TP7") (pin "TP") (pinfunction "TP_TP") (pintype "input"))
    )
    (net (code "3") (name "+5V{slash}2") (class "Default")
      (node (ref "C165") (pin "2") (pinfunction "2_2") (pintype "passive"))
      (node (ref "C28") (pin "1") (pinfunction "1_1") (pintype "passive"))
      (node (ref "C40") (pin "1") (pinfunction "1_1") (pintype "passive"))
      (node (ref "C41") (pin "1") (pinfunction "1_1") (pintype "passive"))
      (node (ref "C43") (pin "1") (pinfunction "1_1") (pintype "passive"))
      (node (ref "C44") (pin "1") (pinfunction "1_1") (pintype "passive"))
      (node (ref "C48") (pin "2") (pinfunction "2_2") (pintype "passive"))
      (node (ref "C49") (pin "2") (pinfunction "2_2") (pintype "passive"))
      (node (ref "C54") (pin "2") (pinfunction "2_2") (pintype "passive"))
      (node (ref "IC35") (pin "1") (pinfunction "VIN_1") (pintype "power_in"))
      (node (ref "IC35") (pin "3") (pinfunction "EN_3") (pintype "input"))
      (node (ref "IC5") (pin "6") (pinfunction "VCC1_6") (pintype "bidirectional"))
      (node (ref "IC5") (pin "7") (pinfunction "VCC2_7") (pintype "bidirectional"))
      (node (ref "IC6") (pin "7") (pinfunction "VCC_7") (pintype "bidirectional"))
      (node (ref "IC7") (pin "3") (pinfunction "V+_3") (pintype "power_in"))
      (node (ref "IC8") (pin "1") (pinfunction "VREF_1") (pintype "bidirectional"))
      (node (ref "L12") (pin "1") (pinfunction "1_1") (pintype "passive"))
      (node (ref "L48") (pin "2") (pinfunction "2_2") (pintype "passive"))
      (node (ref "L6") (pin "1") (pinfunction "1_1") (pintype "passive"))
      (node (ref "R27") (pin "1") (pinfunction "1_1") (pintype "passive"))
      (node (ref "R28") (pin "1") (pinfunction "1_1") (pintype "passive"))
      (node (ref "TP9") (pin "TP") (pinfunction "TP_TP") (pintype "input"))
    )
    (net (code "4") (name "+5V{slash}3") (class "Default")
      (node (ref "C166") (pin "2") (pinfunction "2_2") (pintype "passive"))
      (node (ref "C72") (pin "1") (pinfunction "1_1") (pintype "passive"))
      (node (ref "C73") (pin "1") (pinfunction "1_1") (pintype "passive"))
      (node (ref "C75") (pin "1") (pinfunction "1_1") (pintype "passive"))
      (node (ref "C76") (pin "1") (pinfunction "1_1") (pintype "passive"))
      (node (ref "C80") (pin "2") (pinfunction "2_2") (pintype "passive"))
      (node (ref "C81") (pin "2") (pinfunction "2_2") (pintype "passive"))
      (node (ref "C86") (pin "2") (pinfunction "2_2") (pintype "passive"))
      (node (ref "C95") (pin "1") (pinfunction "1_1") (pintype "passive"))
      (node (ref "IC10") (pin "7") (pinfunction "VCC_7") (pintype "bidirectional"))
      (node (ref "IC11") (pin "3") (pinfunction "V+_3") (pintype "power_in"))
      (node (ref "IC12") (pin "1") (pinfunction "VREF_1") (pintype "bidirectional"))
      (node (ref "IC36") (pin "1") (pinfunction "VIN_1") (pintype "power_in"))
      (node (ref "IC36") (pin "3") (pinfunction "EN_3") (pintype "input"))
      (node (ref "IC9") (pin "6") (pinfunction "VCC1_6") (pintype "bidirectional"))
      (node (ref "IC9") (pin "7") (pinfunction "VCC2_7") (pintype "bidirectional"))
      (node (ref "L21") (pin "1") (pinfunction "1_1") (pintype "passive"))
      (node (ref "L22") (pin "1") (pinfunction "1_1") (pintype "passive"))
      (node (ref "L49") (pin "2") (pinfunction "2_2") (pintype "passive"))
      (node (ref "R43") (pin "1") (pinfunction "1_1") (pintype "passive"))
      (node (ref "R44") (pin "1") (pinfunction "1_1") (pintype "passive"))
      (node (ref "TP11") (pin "TP") (pinfunction "TP_TP") (pintype "input"))
    )
    (net (code "5") (name "+5V{slash}4") (class "Default")
      (node (ref "C123") (pin "1") (pinfunction "1_1") (pintype "passive"))
      (node (ref "C125") (pin "1") (pinfunction "1_1") (pintype "passive"))
      (node (ref "C139") (pin "1") (pinfunction "1_1") (pintype "passive"))
      (node (ref "C141") (pin "1") (pinfunction "1_1") (pintype "passive"))
      (node (ref "C167") (pin "2") (pinfunction "2_2") (pintype "passive"))
      (node (ref "IC15") (pin "1") (pinfunction "VIN_1") (pintype "power_in"))
      (node (ref "IC15") (pin "3") (pinfunction "EN_3") (pintype "input"))
      (node (ref "IC17") (pin "3") (pinfunction "VIN_3") (pintype "power_in"))
      (node (ref "IC20") (pin "1") (pinfunction "VIN_1") (pintype "power_in"))
      (node (ref "IC20") (pin "3") (pinfunction "EN_3") (pintype "input"))
      (node (ref "IC21") (pin "3") (pinfunction "VIN_3") (pintype "power_in"))
      (node (ref "L50") (pin "2") (pinfunction "2_2") (pintype "passive"))
      (node (ref "TP13") (pin "TP") (pinfunction "TP_TP") (pintype "input"))
    )
    (net (code "6") (name "+12V") (class "Default")
      (node (ref "C173") (pin "1") (pinfunction "1_1") (pintype "passive"))
      (node (ref "C177") (pin "1") (pinfunction "1_1") (pintype "passive"))
      (node (ref "C185") (pin "1") (pinfunction "1_1") (pintype "passive"))
      (node (ref "IC32") (pin "12") (pinfunction "VIN_12") (pintype "bidirectional"))
      (node (ref "IC32") (pin "13") (pinfunction "VIN_13") (pintype "bidirectional"))
      (node (ref "IC32") (pin "30") (pinfunction "VIN_30") (pintype "bidirectional"))
      (node (ref "IC32") (pin "31") (pinfunction "VIN_31") (pintype "bidirectional"))
      (node (ref "J3") (pin "1") (pinfunction "1_1") (pintype "passive"))
    )
    (net (code "7") (name "AMP_PWDN") (class "Default")
      (node (ref "IC24") (pin "5") (pinfunction "PWDN_5") (pintype "bidirectional"))
      (node (ref "U2") (pin "P24") (pinfunction "IO_L41P_GCLK27_3_P24") (pintype "bidirectional"))
    )
    (net (code "8") (name "ATT_D0") (class "Default")
      (node (ref "IC23") (pin "1") (pinfunction "D0_1") (pintype "bidirectional"))
      (node (ref "U2") (pin "P34") (pinfunction "IO_L1N_VREF_3_P34") (pintype "bidirectional"))
    )
    (net (code "9") (name "ATT_D1") (class "Default")
      (node (ref "IC23") (pin "24") (pinfunction "D1_24") (pintype "bidirectional"))
      (node (ref "U2") (pin "P33") (pinfunction "IO_L2P_3_P33") (pintype "bidirectional"))
    )
    (net (code "10") (name "ATT_D2") (class "Default")
      (node (ref "IC23") (pin "23") (pinfunction "D2_23") (pintype "bidirectional"))
      (node (ref "U2") (pin "P32") (pinfunction "IO_L2N_3_P32") (pintype "bidirectional"))
    )
    (net (code "11") (name "ATT_D3") (class "Default")
      (node (ref "IC23") (pin "22") (pinfunction "D3_22") (pintype "bidirectional"))
      (node (ref "U2") (pin "P30") (pinfunction "IO_L36P_3_P30") (pintype "bidirectional"))
    )
    (net (code "12") (name "ATT_D4") (class "Default")
      (node (ref "IC23") (pin "21") (pinfunction "D4_21") (pintype "bidirectional"))
      (node (ref "U2") (pin "P29") (pinfunction "IO_L36N_3_P29") (pintype "bidirectional"))
    )
    (net (code "13") (name "ATT_D5") (class "Default")
      (node (ref "IC23") (pin "20") (pinfunction "D5_20") (pintype "bidirectional"))
      (node (ref "U2") (pin "P27") (pinfunction "IO_L37P_3_P27") (pintype "bidirectional"))
    )
    (net (code "14") (name "ATT_D6") (class "Default")
      (node (ref "IC23") (pin "19") (pinfunction "D6_19") (pintype "bidirectional"))
      (node (ref "U2") (pin "P26") (pinfunction "IO_L37N_3_P26") (pintype "bidirectional"))
    )
    (net (code "15") (name "BAND_SELECT") (class "Default")
      (node (ref "IC22") (pin "16") (pinfunction "CTL2_16") (pintype "bidirectional"))
      (node (ref "U2") (pin "P22") (pinfunction "IO_L42P_GCLK25_TRDY2_3_P22") (pintype "bidirectional"))
    )
    (net (code "16") (name "FILT_IN_C1") (class "Default")
      (node (ref "R99") (pin "2") (pinfunction "2_2") (pintype "passive"))
      (node (ref "U2") (pin "P15") (pinfunction "IO_L44P_GCLK21_3_P15") (pintype "bidirectional"))
    )
    (net (code "17") (name "FILT_IN_C2") (class "Default")
      (node (ref "R100") (pin "2") (pinfunction "2_2") (pintype "passive"))
      (node (ref "U2") (pin "P16") (pinfunction "IO_L43N_GCLK22_IRDY2_3_P16") (pintype "bidirectional"))
    )
    (net (code "18") (name "FILT_OUT_C1") (class "Default")
      (node (ref "R104") (pin "2") (pinfunction "2_2") (pintype "passive"))
      (node (ref "U2") (pin "P21") (pinfunction "IO_L42N_GCLK24_3_P21") (pintype "bidirectional"))
    )
    (net (code "19") (name "FILT_OUT_C2") (class "Default")
      (node (ref "R103") (pin "2") (pinfunction "2_2") (pintype "passive"))
      (node (ref "U2") (pin "P17") (pinfunction "IO_L43P_GCLK23_3_P17") (pintype "bidirectional"))
    )
    (net (code "20") (name "FPGA_CLK") (class "Default")
      (node (ref "IC13") (pin "15") (pinfunction "CLK7_15") (pintype "bidirectional"))
      (node (ref "R96") (pin "1") (pinfunction "1_1") (pintype "passive"))
    )
    (net (code "21") (name "FPGA_RESET") (class "Default")
      (node (ref "IC33") (pin "7") (pinfunction "PA1/TIM2_CH2/SPI1_SCK_7") (pintype "bidirectional"))
      (node (ref "U2") (pin "P48") (pinfunction "IO_L48P_D7_2_P48") (pintype "bidirectional"))
    )
    (net (code "22") (name "GND") (class "Default")
      (node (ref "C100") (pin "2") (pinfunction "2_2") (pintype "passive"))
      (node (ref "C101") (pin "2") (pinfunction "2_2") (pintype "passive"))
      (node (ref "C102") (pin "2") (pinfunction "2_2") (pintype "passive"))
      (node (ref "C103") (pin "2") (pinfunction "2_2") (pintype "passive"))
      (node (ref "C104") (pin "1") (pinfunction "1_1") (pintype "passive"))
      (node (ref "C105") (pin "1") (pinfunction "1_1") (pintype "passive"))
      (node (ref "C106") (pin "1") (pinfunction "1_1") (pintype "passive"))
      (node (ref "C108") (pin "1") (pinfunction "1_1") (pintype "passive"))
      (node (ref "C109") (pin "1") (pinfunction "1_1") (pintype "passive"))
      (node (ref "C110") (pin "1") (pinfunction "1_1") (pintype "passive"))
      (node (ref "C111") (pin "2") (pinfunction "2_2") (pintype "passive"))
      (node (ref "C112") (pin "2") (pinfunction "2_2") (pintype "passive"))
      (node (ref "C113") (pin "1") (pinfunction "1_1") (pintype "passive"))
      (node (ref "C114") (pin "2") (pinfunction "2_2") (pintype "passive"))
      (node (ref "C115") (pin "2") (pinfunction "2_2") (pintype "passive"))
      (node (ref "C116") (pin "2") (pinfunction "2_2") (pintype "passive"))
      (node (ref "C117") (pin "2") (pinfunction "2_2") (pintype "passive"))
      (node (ref "C118") (pin "1") (pinfunction "1_1") (pintype "passive"))
      (node (ref "C12") (pin "2") (pinfunction "2_2") (pintype "passive"))
      (node (ref "C120") (pin "2") (pinfunction "2_2") (pintype "passive"))
      (node (ref "C122") (pin "2") (pinfunction "2_2") (pintype "passive"))
      (node (ref "C123") (pin "2") (pinfunction "2_2") (pintype "passive"))
      (node (ref "C124") (pin "2") (pinfunction "2_2") (pintype "passive"))
      (node (ref "C125") (pin "2") (pinfunction "2_2") (pintype "passive"))
      (node (ref "C126") (pin "2") (pinfunction "2_2") (pintype "passive"))
      (node (ref "C127") (pin "2") (pinfunction "2_2") (pintype "passive"))
      (node (ref "C128") (pin "2") (pinfunction "2_2") (pintype "passive"))
      (node (ref "C129") (pin "2") (pinfunction "2_2") (pintype "passive"))
      (node (ref "C13") (pin "2") (pinfunction "2_2") (pintype "passive"))
      (node (ref "C133") (pin "2") (pinfunction "2_2") (pintype "passive"))
      (node (ref "C134") (pin "2") (pinfunction "2_2") (pintype "passive"))
      (node (ref "C135") (pin "2") (pinfunction "2_2") (pintype "passive"))
      (node (ref "C136") (pin "1") (pinfunction "1_1") (pintype "passive"))
      (node (ref "C138") (pin "2") (pinfunction "2_2") (pintype "passive"))
      (node (ref "C139") (pin "2") (pinfunction "2_2") (pintype "passive"))
      (node (ref "C140") (pin "2") (pinfunction "2_2") (pintype "passive"))
      (node (ref "C141") (pin "2") (pinfunction "2_2") (pintype "passive"))
      (node (ref "C142") (pin "2") (pinfunction "2_2") (pintype "passive"))
      (node (ref "C143") (pin "2") (pinfunction "2_2") (pintype "passive"))
      (node (ref "C144") (pin "2") (pinfunction "2_2") (pintype "passive"))
      (node (ref "C145") (pin "2") (pinfunction "2_2") (pintype "passive"))
      (node (ref "C148") (pin "2") (pinfunction "2_2") (pintype "passive"))
      (node (ref "C149") (pin "2") (pinfunction "2_2") (pintype "passive"))
      (node (ref "C151") (pin "2") (pinfunction "2_2") (pintype "passive"))
      (node (ref "C152") (pin "2") (pinfunction "2_2") (pintype "passive"))
      (node (ref "C154") (pin "2") (pinfunction "2_2") (pintype "passive"))
      (node (ref "C155") (pin "2") (pinfunction "2_2") (pintype "passive"))
      (node (ref "C156") (pin "2") (pinfunction "2_2") (pintype "passive"))
      (node (ref "C158") (pin "1") (pinfunction "1_1") (pintype "passive"))
      (node (ref "C159") (pin "1") (pinfunction "1_1") (pintype "passive"))
      (node (ref "C160") (pin "1") (pinfunction "1_1") (pintype "passive"))
      (node (ref "C161") (pin "1") (pinfunction "1_1") (pintype "passive"))
      (node (ref "C162") (pin "1") (pinfunction "1_1") (pintype "passive"))
      (node (ref "C163") (pin "1") (pinfunction "1_1") (pintype "passive"))
      (node (ref "C164") (pin "1") (pinfunction "1_1") (pintype "passive"))
      (node (ref "C165") (pin "1") (pinfunction "1_1") (pintype "passive"))
      (node (ref "C166") (pin "1") (pinfunction "1_1") (pintype "passive"))
      (node (ref "C167") (pin "1") (pinfunction "1_1") (pintype "passive"))
      (node (ref "C168") (pin "1") (pinfunction "1_1") (pintype "passive"))
      (node (ref "C169") (pin "2") (pinfunction "2_2") (pintype "passive"))
      (node (ref "C17") (pin "1") (pinfunction "1_1") (pintype "passive"))
      (node (ref "C170") (pin "2") (pinfunction "2_2") (pintype "passive"))
      (node (ref "C171") (pin "2") (pinfunction "2_2") (pintype "passive"))
      (node (ref "C172") (pin "2") (pinfunction "2_2") (pintype "passive"))
      (node (ref "C173") (pin "2") (pinfunction "2_2") (pintype "passive"))
      (node (ref "C174") (pin "2") (pinfunction "2_2") (pintype "passive"))
      (node (ref "C176") (pin "1") (pinfunction "1_1") (pintype "passive"))
      (node (ref "C177") (pin "2") (pinfunction "2_2") (pintype "passive"))
      (node (ref "C18") (pin "1") (pinfunction "1_1") (pintype "passive"))
      (node (ref "C180") (pin "2") (pinfunction "2_2") (pintype "passive"))
      (node (ref "C181") (pin "2") (pinfunction "2_2") (pintype "passive"))
      (node (ref "C182") (pin "1") (pinfunction "1_1") (pintype "passive"))
      (node (ref "C184") (pin "2") (pinfunction "2_2") (pintype "passive"))
      (node (ref "C185") (pin "2") (pinfunction "2_2") (pintype "passive"))
      (node (ref "C187") (pin "1") (pinfunction "1_1") (pintype "passive"))
      (node (ref "C189") (pin "2") (pinfunction "2_2") (pintype "passive"))
      (node (ref "C19") (pin "2") (pinfunction "2_2") (pintype "passive"))
      (node (ref "C190") (pin "2") (pinfunction "2_2") (pintype "passive"))
      (node (ref "C191") (pin "2") (pinfunction "2_2") (pintype "passive"))
      (node (ref "C192") (pin "2") (pinfunction "2_2") (pintype "passive"))
      (node (ref "C193") (pin "2") (pinfunction "2_2") (pintype "passive"))
      (node (ref "C194") (pin "2") (pinfunction "2_2") (pintype "passive"))
      (node (ref "C195") (pin "2") (pinfunction "2_2") (pintype "passive"))
      (node (ref "C203") (pin "2") (pinfunction "2_2") (pintype "passive"))
      (node (ref "C204") (pin "2") (pinfunction "2_2") (pintype "passive"))
      (node (ref "C205") (pin "2") (pinfunction "2_2") (pintype "passive"))
      (node (ref "C206") (pin "2") (pinfunction "2_2") (pintype "passive"))
      (node (ref "C207") (pin "2") (pinfunction "2_2") (pintype "passive"))
      (node (ref "C208") (pin "2") (pinfunction "2_2") (pintype "passive"))
      (node (ref "C209") (pin "2") (pinfunction "2_2") (pintype "passive"))
      (node (ref "C210") (pin "2") (pinfunction "2_2") (pintype "passive"))
      (node (ref "C211") (pin "2") (pinfunction "2_2") (pintype "passive"))
      (node (ref "C22") (pin "1") (pinfunction "1_1") (pintype "passive"))
      (node (ref "C23") (pin "1") (pinfunction "1_1") (pintype "passive"))
      (node (ref "C26") (pin "2") (pinfunction "2_2") (pintype "passive"))
      (node (ref "C28") (pin "2") (pinfunction "2_2") (pintype "passive"))
      (node (ref "C29") (pin "1") (pinfunction "1_1") (pintype "passive"))
      (node (ref "C30") (pin "1") (pinfunction "1_1") (pintype "passive"))
      (node (ref "C38") (pin "2") (pinfunction "2_2") (pintype "passive"))
      (node (ref "C40") (pin "2") (pinfunction "2_2") (pintype "passive"))
      (node (ref "C41") (pin "2") (pinfunction "2_2") (pintype "passive"))
      (node (ref "C43") (pin "2") (pinfunction "2_2") (pintype "passive"))
      (node (ref "C44") (pin "2") (pinfunction "2_2") (pintype "passive"))
      (node (ref "C45") (pin "1") (pinfunction "1_1") (pintype "passive"))
      (node (ref "C48") (pin "1") (pinfunction "1_1") (pintype "passive"))
      (node (ref "C49") (pin "1") (pinfunction "1_1") (pintype "passive"))
      (node (ref "C52") (pin "2") (pinfunction "2_2") (pintype "passive"))
      (node (ref "C54") (pin "1") (pinfunction "1_1") (pintype "passive"))
      (node (ref "C6") (pin "2") (pinfunction "2_2") (pintype "passive"))
      (node (ref "C61") (pin "1") (pinfunction "1_1") (pintype "passive"))
      (node (ref "C62") (pin "2") (pinfunction "2_2") (pintype "passive"))
      (node (ref "C63") (pin "2") (pinfunction "2_2") (pintype "passive"))
      (node (ref "C64") (pin "1") (pinfunction "1_1") (pintype "passive"))
      (node (ref "C70") (pin "2") (pinfunction "2_2") (pintype "passive"))
      (node (ref "C72") (pin "2") (pinfunction "2_2") (pintype "passive"))
      (node (ref "C73") (pin "2") (pinfunction "2_2") (pintype "passive"))
      (node (ref "C75") (pin "2") (pinfunction "2_2") (pintype "passive"))
      (node (ref "C76") (pin "2") (pinfunction "2_2") (pintype "passive"))
      (node (ref "C77") (pin "1") (pinfunction "1_1") (pintype "passive"))
      (node (ref "C8") (pin "2") (pinfunction "2_2") (pintype "passive"))
      (node (ref "C80") (pin "1") (pinfunction "1_1") (pintype "passive"))
      (node (ref "C81") (pin "1") (pinfunction "1_1") (pintype "passive"))
      (node (ref "C84") (pin "2") (pinfunction "2_2") (pintype "passive"))
      (node (ref "C86") (pin "1") (pinfunction "1_1") (pintype "passive"))
      (node (ref "C9") (pin "2") (pinfunction "2_2") (pintype "passive"))
      (node (ref "C93") (pin "1") (pinfunction "1_1") (pintype "passive"))
      (node (ref "C94") (pin "2") (pinfunction "2_2") (pintype "passive"))
      (node (ref "C95") (pin "2") (pinfunction "2_2") (pintype "passive"))
      (node (ref "C96") (pin "1") (pinfunction "1_1") (pintype "passive"))
      (node (ref "C97") (pin "2") (pinfunction "2_2") (pintype "passive"))
      (node (ref "C98") (pin "2") (pinfunction "2_2") (pintype "passive"))
      (node (ref "C99") (pin "2") (pinfunction "2_2") (pintype "passive"))
      (node (ref "IC1") (pin "12") (pinfunction "GND_12") (pintype "bidirectional"))
      (node (ref "IC1") (pin "13") (pinfunction "GND_13") (pintype "bidirectional"))
      (node (ref "IC1") (pin "16") (pinfunction "TP_16") (pintype "bidirectional"))
      (node (ref "IC1") (pin "17") (pinfunction "GND_17") (pintype "bidirectional"))
      (node (ref "IC1") (pin "4") (pinfunction "LGND_4") (pintype "bidirectional"))
      (node (ref "IC1") (pin "9") (pinfunction "GND_9") (pintype "bidirectional"))
      (node (ref "IC10") (pin "9") (pinfunction "GND_9") (pintype "bidirectional"))
      (node (ref "IC11") (pin "6") (pinfunction "V-_6") (pintype "power_in"))
      (node (ref "IC11") (pin "9") (pinfunction "V-_9") (pintype "power_in"))
      (node (ref "IC12") (pin "5") (pinfunction "GND_5") (pintype "bidirectional"))
      (node (ref "IC13") (pin "21") (pinfunction "GND_21") (pintype "bidirectional"))
      (node (ref "IC14") (pin "11") (pinfunction "GND_RF_11") (pintype "bidirectional"))
      (node (ref "IC14") (pin "18") (pinfunction "GND_VCO_18") (pintype "bidirectional"))
      (node (ref "IC14") (pin "21") (pinfunction "GND_TUNE_21") (pintype "bidirectional"))
      (node (ref "IC14") (pin "27") (pinfunction "GND_DIG_27") (pintype "bidirectional"))
      (node (ref "IC14") (pin "31") (pinfunction "GND_SD_31") (pintype "bidirectional"))
      (node (ref "IC14") (pin "33") (pinfunction "EP_33") (pintype "bidirectional"))
      (node (ref "IC14") (pin "8") (pinfunction "GND_CP_8") (pintype "bidirectional"))
      (node (ref "IC14") (pin "9") (pinfunction "GND_PLL_9") (pintype "bidirectional"))
      (node (ref "IC15") (pin "2") (pinfunction "GND_2") (pintype "power_in"))
      (node (ref "IC16") (pin "10") (pinfunction "GND_10") (pintype "bidirectional"))
      (node (ref "IC16") (pin "12") (pinfunction "GND_12") (pintype "bidirectional"))
      (node (ref "IC16") (pin "13") (pinfunction "GND_13") (pintype "bidirectional"))
      (node (ref "IC16") (pin "5") (pinfunction "GND_5") (pintype "bidirectional"))
      (node (ref "IC16") (pin "8") (pinfunction "GND_8") (pintype "bidirectional"))
      (node (ref "IC17") (pin "1") (pinfunction "GND_1") (pintype "power_in"))
      (node (ref "IC18") (pin "10") (pinfunction "GND_10") (pintype "bidirectional"))
      (node (ref "IC18") (pin "12") (pinfunction "GND_12") (pintype "bidirectional"))
      (node (ref "IC18") (pin "13") (pinfunction "GND_13") (pintype "bidirectional"))
      (node (ref "IC18") (pin "5") (pinfunction "GND_5") (pintype "bidirectional"))
      (node (ref "IC18") (pin "8") (pinfunction "GND_8") (pintype "bidirectional"))
      (node (ref "IC19") (pin "11") (pinfunction "GND_RF_11") (pintype "bidirectional"))
      (node (ref "IC19") (pin "18") (pinfunction "GND_VCO_18") (pintype "bidirectional"))
      (node (ref "IC19") (pin "21") (pinfunction "GND_TUNE_21") (pintype "bidirectional"))
      (node (ref "IC19") (pin "27") (pinfunction "GND_DIG_27") (pintype "bidirectional"))
      (node (ref "IC19") (pin "31") (pinfunction "GND_SD_31") (pintype "bidirectional"))
      (node (ref "IC19") (pin "33") (pinfunction "EP_33") (pintype "bidirectional"))
      (node (ref "IC19") (pin "8") (pinfunction "GND_CP_8") (pintype "bidirectional"))
      (node (ref "IC19") (pin "9") (pinfunction "GND_PLL_9") (pintype "bidirectional"))
      (node (ref "IC2") (pin "9") (pinfunction "GND_9") (pintype "bidirectional"))
      (node (ref "IC20") (pin "2") (pinfunction "GND_2") (pintype "power_in"))
      (node (ref "IC21") (pin "1") (pinfunction "GND_1") (pintype "power_in"))
      (node (ref "IC22") (pin "1") (pinfunction "GND_1") (pintype "bidirectional"))
      (node (ref "IC22") (pin "10") (pinfunction "GND_10") (pintype "bidirectional"))
      (node (ref "IC22") (pin "11") (pinfunction "GND_11") (pintype "bidirectional"))
      (node (ref "IC22") (pin "12") (pinfunction "GND_12") (pintype "bidirectional"))
      (node (ref "IC22") (pin "14") (pinfunction "GND_14") (pintype "bidirectional"))
      (node (ref "IC22") (pin "15") (pinfunction "GND_15") (pintype "bidirectional"))
      (node (ref "IC22") (pin "18") (pinfunction "LOGIC_CTL_18") (pintype "bidirectional"))
      (node (ref "IC22") (pin "2") (pinfunction "GND_2") (pintype "bidirectional"))
      (node (ref "IC22") (pin "21") (pinfunction "GND_21") (pintype "bidirectional"))
      (node (ref "IC22") (pin "4") (pinfunction "GND_4") (pintype "bidirectional"))
      (node (ref "IC22") (pin "5") (pinfunction "GND_5") (pintype "bidirectional"))
      (node (ref "IC22") (pin "6") (pinfunction "GND_6") (pintype "bidirectional"))
      (node (ref "IC22") (pin "7") (pinfunction "GND_7") (pintype "bidirectional"))
      (node (ref "IC22") (pin "9") (pinfunction "GND_9") (pintype "bidirectional"))
      (node (ref "IC23") (pin "10") (pinfunction "GND_10") (pintype "bidirectional"))
      (node (ref "IC23") (pin "11") (pinfunction "GND_11") (pintype "bidirectional"))
      (node (ref "IC23") (pin "12") (pinfunction "GND_12") (pintype "bidirectional"))
      (node (ref "IC23") (pin "13") (pinfunction "GND_13") (pintype "bidirectional"))
      (node (ref "IC23") (pin "15") (pinfunction "GND_15") (pintype "bidirectional"))
      (node (ref "IC23") (pin "25") (pinfunction "GND_25") (pintype "bidirectional"))
      (node (ref "IC23") (pin "3") (pinfunction "MODE_3") (pintype "bidirectional"))
      (node (ref "IC23") (pin "4") (pinfunction "GND_4") (pintype "bidirectional"))
      (node (ref "IC23") (pin "6") (pinfunction "GND_6") (pintype "bidirectional"))
      (node (ref "IC23") (pin "7") (pinfunction "GND_7") (pintype "bidirectional"))
      (node (ref "IC23") (pin "8") (pinfunction "GND_8") (pintype "bidirectional"))
      (node (ref "IC23") (pin "9") (pinfunction "GND_9") (pintype "bidirectional"))
      (node (ref "IC24") (pin "3") (pinfunction "GND_3") (pintype "bidirectional"))
      (node (ref "IC24") (pin "4") (pinfunction "GND_4") (pintype "bidirectional"))
      (node (ref "IC24") (pin "6") (pinfunction "GND_6") (pintype "bidirectional"))
      (node (ref "IC24") (pin "8") (pinfunction "GND_8") (pintype "bidirectional"))
      (node (ref "IC24") (pin "9") (pinfunction "GND_9") (pintype "bidirectional"))
      (node (ref "IC25") (pin "1") (pinfunction "GND_1") (pintype "bidirectional"))
      (node (ref "IC25") (pin "10") (pinfunction "GND_10") (pintype "bidirectional"))
      (node (ref "IC25") (pin "11") (pinfunction "GND_11") (pintype "bidirectional"))
      (node (ref "IC25") (pin "12") (pinfunction "GND_12") (pintype "bidirectional"))
      (node (ref "IC25") (pin "14") (pinfunction "GND_14") (pintype "bidirectional"))
      (node (ref "IC25") (pin "15") (pinfunction "GND_15") (pintype "bidirectional"))
      (node (ref "IC25") (pin "18") (pinfunction "LOGIC_CTL_18") (pintype "bidirectional"))
      (node (ref "IC25") (pin "2") (pinfunction "GND_2") (pintype "bidirectional"))
      (node (ref "IC25") (pin "21") (pinfunction "GND_21") (pintype "bidirectional"))
      (node (ref "IC25") (pin "4") (pinfunction "GND_4") (pintype "bidirectional"))
      (node (ref "IC25") (pin "5") (pinfunction "GND_5") (pintype "bidirectional"))
      (node (ref "IC25") (pin "6") (pinfunction "GND_6") (pintype "bidirectional"))
      (node (ref "IC25") (pin "7") (pinfunction "GND_7") (pintype "bidirectional"))
      (node (ref "IC25") (pin "9") (pinfunction "GND_9") (pintype "bidirectional"))
      (node (ref "IC26") (pin "1") (pinfunction "GND_1") (pintype "bidirectional"))
      (node (ref "IC26") (pin "10") (pinfunction "GND_10") (pintype "bidirectional"))
      (node (ref "IC26") (pin "11") (pinfunction "GND_11") (pintype "bidirectional"))
      (node (ref "IC26") (pin "12") (pinfunction "GND_12") (pintype "bidirectional"))
      (node (ref "IC26") (pin "14") (pinfunction "GND_14") (pintype "bidirectional"))
      (node (ref "IC26") (pin "15") (pinfunction "GND_15") (pintype "bidirectional"))
      (node (ref "IC26") (pin "18") (pinfunction "LOGIC_CTL_18") (pintype "bidirectional"))
      (node (ref "IC26") (pin "2") (pinfunction "GND_2") (pintype "bidirectional"))
      (node (ref "IC26") (pin "21") (pinfunction "GND_21") (pintype "bidirectional"))
      (node (ref "IC26") (pin "4") (pinfunction "GND_4") (pintype "bidirectional"))
      (node (ref "IC26") (pin "5") (pinfunction "GND_5") (pintype "bidirectional"))
      (node (ref "IC26") (pin "6") (pinfunction "GND_6") (pintype "bidirectional"))
      (node (ref "IC26") (pin "7") (pinfunction "GND_7") (pintype "bidirectional"))
      (node (ref "IC26") (pin "9") (pinfunction "GND_9") (pintype "bidirectional"))
      (node (ref "IC27") (pin "1") (pinfunction "GND_1") (pintype "bidirectional"))
      (node (ref "IC27") (pin "10") (pinfunction "GND_10") (pintype "bidirectional"))
      (node (ref "IC27") (pin "11") (pinfunction "GND_11") (pintype "bidirectional"))
      (node (ref "IC27") (pin "12") (pinfunction "GND_12") (pintype "bidirectional"))
      (node (ref "IC27") (pin "14") (pinfunction "GND_14") (pintype "bidirectional"))
      (node (ref "IC27") (pin "15") (pinfunction "GND_15") (pintype "bidirectional"))
      (node (ref "IC27") (pin "18") (pinfunction "LOGIC_CTL_18") (pintype "bidirectional"))
      (node (ref "IC27") (pin "2") (pinfunction "GND_2") (pintype "bidirectional"))
      (node (ref "IC27") (pin "21") (pinfunction "GND_21") (pintype "bidirectional"))
      (node (ref "IC27") (pin "4") (pinfunction "GND_4") (pintype "bidirectional"))
      (node (ref "IC27") (pin "5") (pinfunction "GND_5") (pintype "bidirectional"))
      (node (ref "IC27") (pin "6") (pinfunction "GND_6") (pintype "bidirectional"))
      (node (ref "IC27") (pin "7") (pinfunction "GND_7") (pintype "bidirectional"))
      (node (ref "IC27") (pin "9") (pinfunction "GND_9") (pintype "bidirectional"))
      (node (ref "IC28") (pin "1") (pinfunction "GND_1") (pintype "bidirectional"))
      (node (ref "IC28") (pin "7") (pinfunction "GND_7") (pintype "bidirectional"))
      (node (ref "IC29") (pin "1") (pinfunction "GND_1") (pintype "bidirectional"))
      (node (ref "IC29") (pin "7") (pinfunction "GND_7") (pintype "bidirectional"))
      (node (ref "IC3") (pin "6") (pinfunction "V-_6") (pintype "power_in"))
      (node (ref "IC3") (pin "9") (pinfunction "V-_9") (pintype "power_in"))
      (node (ref "IC30") (pin "1") (pinfunction "GND_1") (pintype "bidirectional"))
      (node (ref "IC30") (pin "7") (pinfunction "GND_7") (pintype "bidirectional"))
      (node (ref "IC31") (pin "1") (pinfunction "GND_1") (pintype "bidirectional"))
      (node (ref "IC31") (pin "7") (pinfunction "GND_7") (pintype "bidirectional"))
      (node (ref "IC32") (pin "10") (pinfunction "GND_10") (pintype "bidirectional"))
      (node (ref "IC32") (pin "15") (pinfunction "GND_15") (pintype "bidirectional"))
      (node (ref "IC32") (pin "21") (pinfunction "AGND_21") (pintype "bidirectional"))
      (node (ref "IC32") (pin "26") (pinfunction "GND_26") (pintype "bidirectional"))
      (node (ref "IC32") (pin "27") (pinfunction "GND_27") (pintype "bidirectional"))
      (node (ref "IC32") (pin "33") (pinfunction "AGND_33") (pintype "bidirectional"))
      (node (ref "IC33") (pin "16") (pinfunction "VSS1_16") (pintype "bidirectional"))
      (node (ref "IC33") (pin "31") (pinfunction "BOOT0_31") (pintype "bidirectional"))
      (node (ref "IC33") (pin "32") (pinfunction "VSS2_32") (pintype "bidirectional"))
      (node (ref "IC33") (pin "33") (pinfunction "EP_33") (pintype "bidirectional"))
      (node (ref "IC34") (pin "2") (pinfunction "GND_2") (pintype "power_in"))
      (node (ref "IC35") (pin "2") (pinfunction "GND_2") (pintype "power_in"))
      (node (ref "IC36") (pin "2") (pinfunction "GND_2") (pintype "power_in"))
      (node (ref "IC4") (pin "5") (pinfunction "GND_5") (pintype "bidirectional"))
      (node (ref "IC5") (pin "12") (pinfunction "GND_12") (pintype "bidirectional"))
      (node (ref "IC5") (pin "13") (pinfunction "GND_13") (pintype "bidirectional"))
      (node (ref "IC5") (pin "16") (pinfunction "TP_16") (pintype "bidirectional"))
      (node (ref "IC5") (pin "17") (pinfunction "GND_17") (pintype "bidirectional"))
      (node (ref "IC5") (pin "4") (pinfunction "LGND_4") (pintype "bidirectional"))
      (node (ref "IC5") (pin "9") (pinfunction "GND_9") (pintype "bidirectional"))
      (node (ref "IC6") (pin "9") (pinfunction "GND_9") (pintype "bidirectional"))
      (node (ref "IC7") (pin "6") (pinfunction "V-_6") (pintype "power_in"))
      (node (ref "IC7") (pin "9") (pinfunction "V-_9") (pintype "power_in"))
      (node (ref "IC8") (pin "5") (pinfunction "GND_5") (pintype "bidirectional"))
      (node (ref "IC9") (pin "12") (pinfunction "GND_12") (pintype "bidirectional"))
      (node (ref "IC9") (pin "13") (pinfunction "GND_13") (pintype "bidirectional"))
      (node (ref "IC9") (pin "16") (pinfunction "TP_16") (pintype "bidirectional"))
      (node (ref "IC9") (pin "17") (pinfunction "GND_17") (pintype "bidirectional"))
      (node (ref "IC9") (pin "4") (pinfunction "LGND_4") (pintype "bidirectional"))
      (node (ref "IC9") (pin "9") (pinfunction "GND_9") (pintype "bidirectional"))
      (node (ref "J1") (pin "GND1") (pinfunction "P$2_GND1") (pintype "bidirectional"))
      (node (ref "J1") (pin "GND2") (pinfunction "P$2_GND2") (pintype "bidirectional"))
      (node (ref "J2") (pin "GND1") (pinfunction "P$2_GND1") (pintype "bidirectional"))
      (node (ref "J2") (pin "GND2") (pinfunction "P$2_GND2") (pintype "bidirectional"))
      (node (ref "J3") (pin "3") (pinfunction "3_3") (pintype "passive"))
      (node (ref "JP1") (pin "3") (pinfunction "3_3") (pintype "passive"))
      (node (ref "JTAG") (pin "10") (pinfunction "10_10") (pintype "passive"))
      (node (ref "JTAG") (pin "2") (pinfunction "2_2") (pintype "passive"))
      (node (ref "L11") (pin "2") (pinfunction "2_2") (pintype "passive"))
      (node (ref "L17") (pin "2") (pinfunction "2_2") (pintype "passive"))
      (node (ref "L18") (pin "2") (pinfunction "2_2") (pintype "passive"))
      (node (ref "L27") (pin "2") (pinfunction "2_2") (pintype "passive"))
      (node (ref "L28") (pin "2") (pinfunction "2_2") (pintype "passive"))
      (node (ref "L3") (pin "2") (pinfunction "2_2") (pintype "passive"))
      (node (ref "LP1") (pin "2") (pinfunction "GND_2") (pintype "bidirectional"))
      (node (ref "LP1") (pin "3") (pinfunction "GND_3") (pintype "bidirectional"))
      (node (ref "LP2") (pin "2") (pinfunction "GND_2") (pintype "bidirectional"))
      (node (ref "LP2") (pin "3") (pinfunction "GND_3") (pintype "bidirectional"))
      (node (ref "LP3") (pin "2") (pinfunction "GND_2") (pintype "bidirectional"))
      (node (ref "LP3") (pin "3") (pinfunction "GND_3") (pintype "bidirectional"))
      (node (ref "Q1") (pin "2") (pinfunction "2_2") (pintype "passive"))
      (node (ref "Q1") (pin "4") (pinfunction "4_4") (pintype "passive"))
      (node (ref "R1") (pin "1") (pinfunction "1_1") (pintype "passive"))
      (node (ref "R10") (pin "2") (pinfunction "2_2") (pintype "passive"))
      (node (ref "R101") (pin "2") (pinfunction "2_2") (pintype "passive"))
      (node (ref "R102") (pin "2") (pinfunction "2_2") (pintype "passive"))
      (node (ref "R11") (pin "2") (pinfunction "2_2") (pintype "passive"))
      (node (ref "R110") (pin "2") (pinfunction "2_2") (pintype "passive"))
      (node (ref "R111") (pin "1") (pinfunction "1_1") (pintype "passive"))
      (node (ref "R112") (pin "1") (pinfunction "1_1") (pintype "passive"))
      (node (ref "R113") (pin "1") (pinfunction "1_1") (pintype "passive"))
      (node (ref "R13") (pin "1") (pinfunction "1_1") (pintype "passive"))
      (node (ref "R2") (pin "2") (pinfunction "2_2") (pintype "passive"))
      (node (ref "R21") (pin "2") (pinfunction "2_2") (pintype "passive"))
      (node (ref "R24") (pin "2") (pinfunction "2_2") (pintype "passive"))
      (node (ref "R25") (pin "2") (pinfunction "2_2") (pintype "passive"))
      (node (ref "R4") (pin "1") (pinfunction "1_1") (pintype "passive"))
      (node (ref "R41") (pin "2") (pinfunction "2_2") (pintype "passive"))
      (node (ref "R49") (pin "1") (pinfunction "1_1") (pintype "passive"))
      (node (ref "R5") (pin "2") (pinfunction "2_2") (pintype "passive"))
      (node (ref "R52") (pin "2") (pinfunction "2_2") (pintype "passive"))
      (node (ref "R53") (pin "1") (pinfunction "1_1") (pintype "passive"))
      (node (ref "R56") (pin "1") (pinfunction "1_1") (pintype "passive"))
      (node (ref "R57") (pin "1") (pinfunction "1_1") (pintype "passive"))
      (node (ref "R60") (pin "2") (pinfunction "2_2") (pintype "passive"))
      (node (ref "R61") (pin "1") (pinfunction "1_1") (pintype "passive"))
      (node (ref "R64") (pin "1") (pinfunction "1_1") (pintype "passive"))
      (node (ref "R67") (pin "1") (pinfunction "1_1") (pintype "passive"))
      (node (ref "R72") (pin "1") (pinfunction "1_1") (pintype "passive"))
      (node (ref "R73") (pin "2") (pinfunction "2_2") (pintype "passive"))
      (node (ref "R75") (pin "1") (pinfunction "1_1") (pintype "passive"))
      (node (ref "R77") (pin "1") (pinfunction "1_1") (pintype "passive"))
      (node (ref "R78") (pin "1") (pinfunction "1_1") (pintype "passive"))
      (node (ref "R79") (pin "1") (pinfunction "1_1") (pintype "passive"))
      (node (ref "R8") (pin "2") (pinfunction "2_2") (pintype "passive"))
      (node (ref "R80") (pin "1") (pinfunction "1_1") (pintype "passive"))
      (node (ref "R82") (pin "1") (pinfunction "1_1") (pintype "passive"))
      (node (ref "R83") (pin "1") (pinfunction "1_1") (pintype "passive"))
      (node (ref "R85") (pin "1") (pinfunction "1_1") (pintype "passive"))
      (node (ref "R86") (pin "1") (pinfunction "1_1") (pintype "passive"))
      (node (ref "R9") (pin "1") (pinfunction "1_1") (pintype "passive"))
      (node (ref "R97") (pin "2") (pinfunction "2_2") (pintype "passive"))
      (node (ref "R98") (pin "2") (pinfunction "2_2") (pintype "passive"))
      (node (ref "T1") (pin "3") (pinfunction "GND_3") (pintype "bidirectional"))
      (node (ref "T1") (pin "4") (pinfunction "GND_4") (pintype "bidirectional"))
      (node (ref "T2") (pin "3") (pinfunction "GND_3") (pintype "bidirectional"))
      (node (ref "T2") (pin "4") (pinfunction "GND_4") (pintype "bidirectional"))
      (node (ref "T3") (pin "2") (pinfunction "PIN2_2") (pintype "bidirectional"))
      (node (ref "T3") (pin "3") (pinfunction "GND_3") (pintype "bidirectional"))
      (node (ref "T3") (pin "4") (pinfunction "GND_4") (pintype "bidirectional"))
      (node (ref "TP10") (pin "TP") (pinfunction "TP_TP") (pintype "input"))
      (node (ref "TP12") (pin "TP") (pinfunction "TP_TP") (pintype "input"))
      (node (ref "TP14") (pin "TP") (pinfunction "TP_TP") (pintype "input"))
      (node (ref "TP6") (pin "TP") (pinfunction "TP_TP") (pintype "input"))
      (node (ref "TP8") (pin "TP") (pinfunction "TP_TP") (pintype "input"))
      (node (ref "U2") (pin "P108") (pinfunction "GND_P108") (pintype "power_in"))
      (node (ref "U2") (pin "P113") (pinfunction "GND_P113") (pintype "power_in"))
      (node (ref "U2") (pin "P13") (pinfunction "GND_P13") (pintype "power_in"))
      (node (ref "U2") (pin "P130") (pinfunction "GND_P130") (pintype "power_in"))
      (node (ref "U2") (pin "P136") (pinfunction "GND_P136") (pintype "power_in"))
      (node (ref "U2") (pin "P25") (pinfunction "GND_P25") (pintype "power_in"))
      (node (ref "U2") (pin "P3") (pinfunction "GND_P3") (pintype "power_in"))
      (node (ref "U2") (pin "P49") (pinfunction "GND_P49") (pintype "power_in"))
      (node (ref "U2") (pin "P54") (pinfunction "GND_P54") (pintype "power_in"))
      (node (ref "U2") (pin "P60") (pinfunction "IO_L13P_M1_2_P60") (pintype "bidirectional"))
      (node (ref "U2") (pin "P68") (pinfunction "GND_P68") (pintype "power_in"))
      (node (ref "U2") (pin "P73") (pinfunction "SUSPEND_P73") (pintype "input"))
      (node (ref "U2") (pin "P77") (pinfunction "GND_P77") (pintype "power_in"))
      (node (ref "U2") (pin "P91") (pinfunction "GND_P91") (pintype "power_in"))
      (node (ref "U2") (pin "P96") (pinfunction "GND_P96") (pintype "power_in"))
      (node (ref "U4") (pin "4") (pinfunction "GND_4") (pintype "power_in"))
      (node (ref "X1") (pin "G@1") (pinfunction "2_G@1") (pintype "passive"))
      (node (ref "X1") (pin "G@2") (pinfunction "2_G@2") (pintype "passive"))
      (node (ref "X1") (pin "G@3") (pinfunction "2_G@3") (pintype "passive"))
      (node (ref "X1") (pin "G@4") (pinfunction "2_G@4") (pintype "passive"))
      (node (ref "X2") (pin "G@1") (pinfunction "2_G@1") (pintype "passive"))
      (node (ref "X2") (pin "G@2") (pinfunction "2_G@2") (pintype "passive"))
      (node (ref "X2") (pin "G@3") (pinfunction "2_G@3") (pintype "passive"))
      (node (ref "X2") (pin "G@4") (pinfunction "2_G@4") (pintype "passive"))
      (node (ref "X4") (pin "5") (pinfunction "5_5") (pintype "passive"))
      (node (ref "X4") (pin "M1") (pinfunction "S1_M1") (pintype "passive"))
      (node (ref "X4") (pin "M2") (pinfunction "S2_M2") (pintype "passive"))
      (node (ref "X4") (pin "M3") (pinfunction "S3_M3") (pintype "passive"))
      (node (ref "X4") (pin "M4") (pinfunction "S4_M4") (pintype "passive"))
    )
    (net (code "23") (name "LO1_CE") (class "Default")
      (node (ref "IC19") (pin "4") (pinfunction "CE_4") (pintype "bidirectional"))
      (node (ref "R64") (pin "2") (pinfunction "2_2") (pintype "passive"))
      (node (ref "U2") (pin "P138") (pinfunction "IO_L4P_0_P138") (pintype "bidirectional"))
    )
    (net (code "24") (name "LO1_CLK") (class "Default")
      (node (ref "IC19") (pin "1") (pinfunction "CLK_1") (pintype "input"))
      (node (ref "U2") (pin "P141") (pinfunction "IO_L2N_0_P141") (pintype "bidirectional"))
    )
    (net (code "25") (name "LO1_LD") (class "Default")
      (node (ref "IC19") (pin "25") (pinfunction "LD_25") (pintype "output"))
      (node (ref "U2") (pin "P142") (pinfunction "IO_L2P_0_P142") (pintype "bidirectional"))
    )
    (net (code "26") (name "LO1_LE") (class "Default")
      (node (ref "IC19") (pin "3") (pinfunction "LE_3") (pintype "input"))
      (node (ref "U2") (pin "P139") (pinfunction "IO_L3N_0_P139") (pintype "bidirectional"))
    )
    (net (code "27") (name "LO1_MOSI") (class "Default")
      (node (ref "IC19") (pin "2") (pinfunction "DATA_2") (pintype "input"))
      (node (ref "U2") (pin "P140") (pinfunction "IO_L3P_0_P140") (pintype "bidirectional"))
    )
    (net (code "28") (name "LO1_MUX") (class "Default")
      (node (ref "IC19") (pin "30") (pinfunction "MUX_30") (pintype "bidirectional"))
      (node (ref "U2") (pin "P144") (pinfunction "IO_L1P_HSWAPEN_0_P144") (pintype "bidirectional"))
    )
    (net (code "29") (name "LO1_REF") (class "Default")
      (node (ref "C146") (pin "1") (pinfunction "1_1") (pintype "passive"))
      (node (ref "IC13") (pin "9") (pinfunction "CLK2_9") (pintype "bidirectional"))
    )
    (net (code "30") (name "LO1_RF_EN") (class "Default")
      (node (ref "IC19") (pin "26") (pinfunction "RFOUT_EN_26") (pintype "input"))
      (node (ref "U2") (pin "P143") (pinfunction "IO_L1N_VREF_0_P143") (pintype "bidirectional"))
    )
    (net (code "31") (name "MCU_AUX1") (class "Default")
      (node (ref "IC33") (pin "2") (pinfunction "PC14-OSC32_IN_2") (pintype "bidirectional"))
      (node (ref "U2") (pin "P55") (pinfunction "IO_L30N_GCLK0_USERCCLK_2_P55") (pintype "bidirectional"))
    )
    (net (code "32") (name "MCU_AUX2") (class "Default")
      (node (ref "IC33") (pin "3") (pinfunction "PC15-OSC32_OUT_3") (pintype "bidirectional"))
      (node (ref "U2") (pin "P51") (pinfunction "IO_L31P_GCLK31_D14_2_P51") (pintype "bidirectional"))
    )
    (net (code "33") (name "MCU_AUX3") (class "Default")
      (node (ref "IC33") (pin "6") (pinfunction "PA0/CK_IN/TIM2_CH1_6") (pintype "bidirectional"))
      (node (ref "U2") (pin "P50") (pinfunction "IO_L31N_GCLK30_D15_2_P50") (pintype "bidirectional"))
    )
    (net (code "34") (name "MCU_INTR") (class "Default")
      (node (ref "IC33") (pin "30") (pinfunction "PB7/I2C1_SDA/USART1_RX_30") (pintype "bidirectional"))
      (node (ref "U2") (pin "P57") (pinfunction "IO_L14N_D12_2_P57") (pintype "bidirectional"))
    )
    (net (code "35") (name "MCU_MISO") (class "Default")
      (node (ref "IC33") (pin "27") (pinfunction "PB4/I2C3_SDA/SPI1_MISO/SPI3_MISO_27") (pintype "bidirectional"))
      (node (ref "U2") (pin "P61") (pinfunction "IO_L12N_D2_MISO3_2_P61") (pintype "bidirectional"))
    )
    (net (code "36") (name "MCU_MOSI") (class "Default")
      (node (ref "IC33") (pin "28") (pinfunction "PB5/SPI1_MOSI/SPI3_MOSI_28") (pintype "bidirectional"))
      (node (ref "U2") (pin "P59") (pinfunction "IO_L13N_D10_2_P59") (pintype "bidirectional"))
    )
    (net (code "37") (name "MCU_NSS") (class "Default")
      (node (ref "IC33") (pin "29") (pinfunction "PB6/I2C1_SCL/USART1_TX_29") (pintype "bidirectional"))
      (node (ref "U2") (pin "P58") (pinfunction "IO_L14P_D11_2_P58") (pintype "bidirectional"))
    )
    (net (code "38") (name "MCU_SCK") (class "Default")
      (node (ref "IC33") (pin "26") (pinfunction "PB3/TIM2_CH2/SPI1_SCK/SPI3_SCK_26") (pintype "bidirectional"))
      (node (ref "U2") (pin "P56") (pinfunction "IO_L30P_GCLK1_D13_2_P56") (pintype "bidirectional"))
    )
    (net (code "39") (name "Net-(C1-Pad1)") (class "Default")
      (node (ref "C1") (pin "1") (pinfunction "1_1") (pintype "passive"))
      (node (ref "X2") (pin "1") (pinfunction "1_1") (pintype "passive"))
    )
    (net (code "40") (name "Net-(C2-Pad2)") (class "Default")
      (node (ref "C2") (pin "2") (pinfunction "2_2") (pintype "passive"))
      (node (ref "R1") (pin "2") (pinfunction "2_2") (pintype "passive"))
      (node (ref "R2") (pin "1") (pinfunction "1_1") (pintype "passive"))
      (node (ref "R3") (pin "2") (pinfunction "2_2") (pintype "passive"))
    )
    (net (code "41") (name "Net-(C10-Pad2)") (class "Default")
      (node (ref "C10") (pin "2") (pinfunction "2_2") (pintype "passive"))
      (node (ref "C14") (pin "2") (pinfunction "2_2") (pintype "passive"))
      (node (ref "L8") (pin "1") (pinfunction "1_1") (pintype "passive"))
    )
    (net (code "42") (name "Net-(C11-Pad2)") (class "Default")
      (node (ref "C11") (pin "2") (pinfunction "2_2") (pintype "passive"))
      (node (ref "C14") (pin "1") (pinfunction "1_1") (pintype "passive"))
      (node (ref "L7") (pin "1") (pinfunction "1_1") (pintype "passive"))
    )
    (net (code "43") (name "Net-(C27-Pad1)") (class "Default")
      (node (ref "C27") (pin "1") (pinfunction "1_1") (pintype "passive"))
      (node (ref "L4") (pin "1") (pinfunction "1_1") (pintype "passive"))
      (node (ref "R20") (pin "1") (pinfunction "1_1") (pintype "passive"))
    )
    (net (code "44") (name "Net-(C27-Pad2)") (class "Default")
      (node (ref "C27") (pin "2") (pinfunction "2_2") (pintype "passive"))
      (node (ref "L5") (pin "1") (pinfunction "1_1") (pintype "passive"))
      (node (ref "R19") (pin "1") (pinfunction "1_1") (pintype "passive"))
    )
    (net (code "45") (name "Net-(C31-Pad1)") (class "Default")
      (node (ref "C31") (pin "1") (pinfunction "1_1") (pintype "passive"))
      (node (ref "L7") (pin "2") (pinfunction "2_2") (pintype "passive"))
      (node (ref "L9") (pin "1") (pinfunction "1_1") (pintype "passive"))
    )
    (net (code "46") (name "Net-(C31-Pad2)") (class "Default")
      (node (ref "C31") (pin "2") (pinfunction "2_2") (pintype "passive"))
      (node (ref "L10") (pin "1") (pinfunction "1_1") (pintype "passive"))
      (node (ref "L8") (pin "2") (pinfunction "2_2") (pintype "passive"))
    )
    (net (code "47") (name "Net-(C32-Pad1)") (class "Default")
      (node (ref "C32") (pin "1") (pinfunction "1_1") (pintype "passive"))
      (node (ref "L9") (pin "2") (pinfunction "2_2") (pintype "passive"))
      (node (ref "R33") (pin "2") (pinfunction "2_2") (pintype "passive"))
      (node (ref "R34") (pin "2") (pinfunction "2_2") (pintype "passive"))
    )
    (net (code "48") (name "Net-(C32-Pad2)") (class "Default")
      (node (ref "C32") (pin "2") (pinfunction "2_2") (pintype "passive"))
      (node (ref "L10") (pin "2") (pinfunction "2_2") (pintype "passive"))
      (node (ref "R33") (pin "1") (pinfunction "1_1") (pintype "passive"))
      (node (ref "R35") (pin "2") (pinfunction "2_2") (pintype "passive"))
    )
    (net (code "49") (name "Net-(C33-Pad1)") (class "Default")
      (node (ref "C33") (pin "1") (pinfunction "1_1") (pintype "passive"))
      (node (ref "X1") (pin "1") (pinfunction "1_1") (pintype "passive"))
    )
    (net (code "50") (name "Net-(C34-Pad2)") (class "Default")
      (node (ref "C34") (pin "2") (pinfunction "2_2") (pintype "passive"))
      (node (ref "R10") (pin "1") (pinfunction "1_1") (pintype "passive"))
      (node (ref "R12") (pin "2") (pinfunction "2_2") (pintype "passive"))
      (node (ref "R9") (pin "2") (pinfunction "2_2") (pintype "passive"))
    )
    (net (code "51") (name "Net-(C42-Pad2)") (class "Default")
      (node (ref "C42") (pin "2") (pinfunction "2_2") (pintype "passive"))
      (node (ref "C56") (pin "1") (pinfunction "1_1") (pintype "passive"))
      (node (ref "L13") (pin "1") (pinfunction "1_1") (pintype "passive"))
    )
    (net (code "52") (name "Net-(C53-Pad1)") (class "Default")
      (node (ref "C53") (pin "1") (pinfunction "1_1") (pintype "passive"))
      (node (ref "L19") (pin "1") (pinfunction "1_1") (pintype "passive"))
      (node (ref "R32") (pin "1") (pinfunction "1_1") (pintype "passive"))
    )
    (net (code "53") (name "Net-(C53-Pad2)") (class "Default")
      (node (ref "C53") (pin "2") (pinfunction "2_2") (pintype "passive"))
      (node (ref "L20") (pin "1") (pinfunction "1_1") (pintype "passive"))
      (node (ref "R31") (pin "1") (pinfunction "1_1") (pintype "passive"))
    )
    (net (code "54") (name "Net-(C55-Pad2)") (class "Default")
      (node (ref "C55") (pin "2") (pinfunction "2_2") (pintype "passive"))
      (node (ref "C56") (pin "2") (pinfunction "2_2") (pintype "passive"))
      (node (ref "L14") (pin "1") (pinfunction "1_1") (pintype "passive"))
    )
    (net (code "55") (name "Net-(C57-Pad1)") (class "Default")
      (node (ref "C57") (pin "1") (pinfunction "1_1") (pintype "passive"))
      (node (ref "L13") (pin "2") (pinfunction "2_2") (pintype "passive"))
      (node (ref "L15") (pin "1") (pinfunction "1_1") (pintype "passive"))
    )
    (net (code "56") (name "Net-(C57-Pad2)") (class "Default")
      (node (ref "C57") (pin "2") (pinfunction "2_2") (pintype "passive"))
      (node (ref "L14") (pin "2") (pinfunction "2_2") (pintype "passive"))
      (node (ref "L16") (pin "1") (pinfunction "1_1") (pintype "passive"))
    )
    (net (code "57") (name "Net-(C58-Pad1)") (class "Default")
      (node (ref "C58") (pin "1") (pinfunction "1_1") (pintype "passive"))
      (node (ref "L15") (pin "2") (pinfunction "2_2") (pintype "passive"))
      (node (ref "R37") (pin "2") (pinfunction "2_2") (pintype "passive"))
      (node (ref "R38") (pin "2") (pinfunction "2_2") (pintype "passive"))
    )
    (net (code "58") (name "Net-(C58-Pad2)") (class "Default")
      (node (ref "C58") (pin "2") (pinfunction "2_2") (pintype "passive"))
      (node (ref "L16") (pin "2") (pinfunction "2_2") (pintype "passive"))
      (node (ref "R37") (pin "1") (pinfunction "1_1") (pintype "passive"))
      (node (ref "R39") (pin "2") (pinfunction "2_2") (pintype "passive"))
    )
    (net (code "59") (name "Net-(C74-Pad2)") (class "Default")
      (node (ref "C74") (pin "2") (pinfunction "2_2") (pintype "passive"))
      (node (ref "C88") (pin "1") (pinfunction "1_1") (pintype "passive"))
      (node (ref "L23") (pin "1") (pinfunction "1_1") (pintype "passive"))
    )
    (net (code "60") (name "Net-(C85-Pad1)") (class "Default")
      (node (ref "C85") (pin "1") (pinfunction "1_1") (pintype "passive"))
      (node (ref "L29") (pin "1") (pinfunction "1_1") (pintype "passive"))
      (node (ref "R48") (pin "1") (pinfunction "1_1") (pintype "passive"))
    )
    (net (code "61") (name "Net-(C85-Pad2)") (class "Default")
      (node (ref "C85") (pin "2") (pinfunction "2_2") (pintype "passive"))
      (node (ref "L30") (pin "1") (pinfunction "1_1") (pintype "passive"))
      (node (ref "R47") (pin "1") (pinfunction "1_1") (pintype "passive"))
    )
    (net (code "62") (name "Net-(C87-Pad2)") (class "Default")
      (node (ref "C87") (pin "2") (pinfunction "2_2") (pintype "passive"))
      (node (ref "C88") (pin "2") (pinfunction "2_2") (pintype "passive"))
      (node (ref "L24") (pin "1") (pinfunction "1_1") (pintype "passive"))
    )
    (net (code "63") (name "Net-(C89-Pad1)") (class "Default")
      (node (ref "C89") (pin "1") (pinfunction "1_1") (pintype "passive"))
      (node (ref "L23") (pin "2") (pinfunction "2_2") (pintype "passive"))
      (node (ref "L25") (pin "1") (pinfunction "1_1") (pintype "passive"))
    )
    (net (code "64") (name "Net-(C89-Pad2)") (class "Default")
      (node (ref "C89") (pin "2") (pinfunction "2_2") (pintype "passive"))
      (node (ref "L24") (pin "2") (pinfunction "2_2") (pintype "passive"))
      (node (ref "L26") (pin "1") (pinfunction "1_1") (pintype "passive"))
    )
    (net (code "65") (name "Net-(C98-Pad1)") (class "Default")
      (node (ref "C98") (pin "1") (pinfunction "1_1") (pintype "passive"))
      (node (ref "L32") (pin "1") (pinfunction "1_1") (pintype "passive"))
      (node (ref "L33") (pin "2") (pinfunction "2_2") (pintype "passive"))
    )
    (net (code "66") (name "Net-(C101-Pad1)") (class "Default")
      (node (ref "C101") (pin "1") (pinfunction "1_1") (pintype "passive"))
      (node (ref "L34") (pin "1") (pinfunction "1_1") (pintype "passive"))
      (node (ref "L35") (pin "2") (pinfunction "2_2") (pintype "passive"))
    )
    (net (code "67") (name "Net-(C111-Pad1)") (class "Default")
      (node (ref "C111") (pin "1") (pinfunction "1_1") (pintype "passive"))
      (node (ref "L36") (pin "1") (pinfunction "1_1") (pintype "passive"))
      (node (ref "L37") (pin "2") (pinfunction "2_2") (pintype "passive"))
    )
    (net (code "68") (name "Net-(C119-Pad2)") (class "Default")
      (node (ref "C119") (pin "2") (pinfunction "2_2") (pintype "passive"))
      (node (ref "R51") (pin "1") (pinfunction "1_1") (pintype "passive"))
    )
    (net (code "69") (name "Net-(C126-Pad1)") (class "Default")
      (node (ref "C126") (pin "1") (pinfunction "1_1") (pintype "passive"))
      (node (ref "IC17") (pin "2") (pinfunction "VOUT_2") (pintype "power_in"))
      (node (ref "IC17") (pin "4") (pinfunction "VOUT_4") (pintype "power_in"))
      (node (ref "L38") (pin "1") (pinfunction "1_1") (pintype "passive"))
    )
    (net (code "70") (name "Net-(C131-Pad1)") (class "Default")
      (node (ref "C131") (pin "1") (pinfunction "1_1") (pintype "passive"))
      (node (ref "R57") (pin "2") (pinfunction "2_2") (pintype "passive"))
    )
    (net (code "71") (name "Net-(C137-Pad2)") (class "Default")
      (node (ref "C137") (pin "2") (pinfunction "2_2") (pintype "passive"))
      (node (ref "R59") (pin "1") (pinfunction "1_1") (pintype "passive"))
    )
    (net (code "72") (name "Net-(C142-Pad1)") (class "Default")
      (node (ref "C142") (pin "1") (pinfunction "1_1") (pintype "passive"))
      (node (ref "IC21") (pin "2") (pinfunction "VOUT_2") (pintype "power_in"))
      (node (ref "IC21") (pin "4") (pinfunction "VOUT_4") (pintype "power_in"))
      (node (ref "L40") (pin "1") (pinfunction "1_1") (pintype "passive"))
    )
    (net (code "73") (name "Net-(C147-Pad1)") (class "Default")
      (node (ref "C147") (pin "1") (pinfunction "1_1") (pintype "passive"))
      (node (ref "R67") (pin "2") (pinfunction "2_2") (pintype "passive"))
    )
    (net (code "74") (name "Net-(C153-Pad2)") (class "Default")
      (node (ref "C153") (pin "2") (pinfunction "2_2") (pintype "passive"))
      (node (ref "R69") (pin "1") (pinfunction "1_1") (pintype "passive"))
    )
    (net (code "75") (name "Net-(C157-Pad2)") (class "Default")
      (node (ref "C157") (pin "2") (pinfunction "2_2") (pintype "passive"))
      (node (ref "R74") (pin "2") (pinfunction "2_2") (pintype "passive"))
      (node (ref "R75") (pin "2") (pinfunction "2_2") (pintype "passive"))
    )
    (net (code "76") (name "Net-(IC1-IADJ)") (class "Default")
      (node (ref "IC1") (pin "8") (pinfunction "IADJ_8") (pintype "bidirectional"))
      (node (ref "R11") (pin "1") (pinfunction "1_1") (pintype "passive"))
    )
    (net (code "77") (name "Net-(IC1-IN+)") (class "Default")
      (node (ref "C3") (pin "2") (pinfunction "2_2") (pintype "passive"))
      (node (ref "IC1") (pin "2") (pinfunction "IN+_2") (pintype "bidirectional"))
    )
    (net (code "78") (name "Net-(IC1-IN-)") (class "Default")
      (node (ref "C4") (pin "2") (pinfunction "2_2") (pintype "passive"))
      (node (ref "IC1") (pin "3") (pinfunction "IN-_3") (pintype "bidirectional"))
    )
    (net (code "79") (name "Net-(IC1-LO+)") (class "Default")
      (node (ref "C7") (pin "2") (pinfunction "2_2") (pintype "passive"))
      (node (ref "IC1") (pin "15") (pinfunction "LO+_15") (pintype "bidirectional"))
    )
    (net (code "80") (name "Net-(IC1-LO-)") (class "Default")
      (node (ref "C6") (pin "1") (pinfunction "1_1") (pintype "passive"))
      (node (ref "IC1") (pin "14") (pinfunction "LO-_14") (pintype "bidirectional"))
    )
    (net (code "81") (name "Net-(IC1-OUT+)") (class "Default")
      (node (ref "C11") (pin "1") (pinfunction "1_1") (pintype "passive"))
      (node (ref "IC1") (pin "11") (pinfunction "OUT+_11") (pintype "bidirectional"))
      (node (ref "L1") (pin "2") (pinfunction "2_2") (pintype "passive"))
    )
    (net (code "82") (name "Net-(IC1-OUT-)") (class "Default")
      (node (ref "C10") (pin "1") (pinfunction "1_1") (pintype "passive"))
      (node (ref "IC1") (pin "10") (pinfunction "OUT-_10") (pintype "bidirectional"))
      (node (ref "L2") (pin "2") (pinfunction "2_2") (pintype "passive"))
    )
    (net (code "83") (name "Net-(IC2-IN+)") (class "Default")
      (node (ref "IC2") (pin "3") (pinfunction "IN+_3") (pintype "bidirectional"))
      (node (ref "L3") (pin "1") (pinfunction "1_1") (pintype "passive"))
      (node (ref "R34") (pin "1") (pinfunction "1_1") (pintype "passive"))
      (node (ref "R36") (pin "1") (pinfunction "1_1") (pintype "passive"))
    )
    (net (code "84") (name "Net-(IC2-IN-)") (class "Default")
      (node (ref "IC2") (pin "4") (pinfunction "IN-_4") (pintype "bidirectional"))
      (node (ref "L11") (pin "1") (pinfunction "1_1") (pintype "passive"))
      (node (ref "R35") (pin "1") (pinfunction "1_1") (pintype "passive"))
      (node (ref "R36") (pin "2") (pinfunction "2_2") (pintype "passive"))
    )
    (net (code "85") (name "Net-(IC2-LO+)") (class "Default")
      (node (ref "C15") (pin "2") (pinfunction "2_2") (pintype "passive"))
      (node (ref "IC2") (pin "8") (pinfunction "LO+_8") (pintype "bidirectional"))
    )
    (net (code "86") (name "Net-(IC2-LO-)") (class "Default")
      (node (ref "C18") (pin "2") (pinfunction "2_2") (pintype "passive"))
      (node (ref "IC2") (pin "1") (pinfunction "LO-_1") (pintype "bidirectional"))
    )
    (net (code "87") (name "Net-(IC2-OUT+)") (class "Default")
      (node (ref "C20") (pin "1") (pinfunction "1_1") (pintype "passive"))
      (node (ref "IC2") (pin "6") (pinfunction "OUT+_6") (pintype "bidirectional"))
      (node (ref "R15") (pin "2") (pinfunction "2_2") (pintype "passive"))
    )
    (net (code "88") (name "Net-(IC2-OUT-)") (class "Default")
      (node (ref "C21") (pin "1") (pinfunction "1_1") (pintype "passive"))
      (node (ref "IC2") (pin "5") (pinfunction "OUT-_5") (pintype "bidirectional"))
      (node (ref "R16") (pin "2") (pinfunction "2_2") (pintype "passive"))
    )
    (net (code "89") (name "Net-(IC3-+IN)") (class "Default")
      (node (ref "C20") (pin "2") (pinfunction "2_2") (pintype "passive"))
      (node (ref "C24") (pin "1") (pinfunction "1_1") (pintype "passive"))
      (node (ref "IC3") (pin "8") (pinfunction "+IN_8") (pintype "input"))
      (node (ref "R17") (pin "1") (pinfunction "1_1") (pintype "passive"))
    )
    (net (code "90") (name "Net-(IC3-+OUT)") (class "Default")
      (node (ref "C25") (pin "1") (pinfunction "1_1") (pintype "passive"))
      (node (ref "IC3") (pin "4") (pinfunction "+OUT_4") (pintype "bidirectional"))
      (node (ref "R18") (pin "1") (pinfunction "1_1") (pintype "passive"))
      (node (ref "R19") (pin "2") (pinfunction "2_2") (pintype "passive"))
    )
    (net (code "91") (name "Net-(IC3--IN)") (class "Default")
      (node (ref "C21") (pin "2") (pinfunction "2_2") (pintype "passive"))
      (node (ref "C25") (pin "2") (pinfunction "2_2") (pintype "passive"))
      (node (ref "IC3") (pin "1") (pinfunction "-IN_1") (pintype "input"))
      (node (ref "R18") (pin "2") (pinfunction "2_2") (pintype "passive"))
    )
    (net (code "92") (name "Net-(IC3--OUT)") (class "Default")
      (node (ref "C24") (pin "2") (pinfunction "2_2") (pintype "passive"))
      (node (ref "IC3") (pin "5") (pinfunction "-OUT_5") (pintype "bidirectional"))
      (node (ref "R17") (pin "2") (pinfunction "2_2") (pintype "passive"))
      (node (ref "R20") (pin "2") (pinfunction "2_2") (pintype "passive"))
    )
    (net (code "93") (name "Net-(IC3-VOCM)") (class "Default")
      (node (ref "C26") (pin "1") (pinfunction "1_1") (pintype "passive"))
      (node (ref "IC3") (pin "2") (pinfunction "VOCM_2") (pintype "output"))
    )
    (net (code "94") (name "Net-(IC4-AIN+)") (class "Default")
      (node (ref "C16") (pin "1") (pinfunction "1_1") (pintype "passive"))
      (node (ref "C17") (pin "2") (pinfunction "2_2") (pintype "passive"))
      (node (ref "IC4") (pin "3") (pinfunction "AIN+_3") (pintype "bidirectional"))
      (node (ref "L4") (pin "2") (pinfunction "2_2") (pintype "passive"))
    )
    (net (code "95") (name "Net-(IC4-AIN-)") (class "Default")
      (node (ref "C16") (pin "2") (pinfunction "2_2") (pintype "passive"))
      (node (ref "C19") (pin "1") (pinfunction "1_1") (pintype "passive"))
      (node (ref "IC4") (pin "4") (pinfunction "AIN-_4") (pintype "bidirectional"))
      (node (ref "L5") (pin "2") (pinfunction "2_2") (pintype "passive"))
    )
    (net (code "96") (name "Net-(IC5-IADJ)") (class "Default")
      (node (ref "IC5") (pin "8") (pinfunction "IADJ_8") (pintype "bidirectional"))
      (node (ref "R25") (pin "1") (pinfunction "1_1") (pintype "passive"))
    )
    (net (code "97") (name "Net-(IC5-IN+)") (class "Default")
      (node (ref "C35") (pin "2") (pinfunction "2_2") (pintype "passive"))
      (node (ref "IC5") (pin "2") (pinfunction "IN+_2") (pintype "bidirectional"))
    )
    (net (code "98") (name "Net-(IC5-IN-)") (class "Default")
      (node (ref "C36") (pin "2") (pinfunction "2_2") (pintype "passive"))
      (node (ref "IC5") (pin "3") (pinfunction "IN-_3") (pintype "bidirectional"))
    )
    (net (code "99") (name "Net-(IC5-LO+)") (class "Default")
      (node (ref "C39") (pin "2") (pinfunction "2_2") (pintype "passive"))
      (node (ref "IC5") (pin "15") (pinfunction "LO+_15") (pintype "bidirectional"))
    )
    (net (code "100") (name "Net-(IC5-LO-)") (class "Default")
      (node (ref "C38") (pin "1") (pinfunction "1_1") (pintype "passive"))
      (node (ref "IC5") (pin "14") (pinfunction "LO-_14") (pintype "bidirectional"))
    )
    (net (code "101") (name "Net-(IC5-OUT+)") (class "Default")
      (node (ref "C42") (pin "1") (pinfunction "1_1") (pintype "passive"))
      (node (ref "IC5") (pin "11") (pinfunction "OUT+_11") (pintype "bidirectional"))
      (node (ref "L6") (pin "2") (pinfunction "2_2") (pintype "passive"))
    )
    (net (code "102") (name "Net-(IC5-OUT-)") (class "Default")
      (node (ref "C55") (pin "1") (pinfunction "1_1") (pintype "passive"))
      (node (ref "IC5") (pin "10") (pinfunction "OUT-_10") (pintype "bidirectional"))
      (node (ref "L12") (pin "2") (pinfunction "2_2") (pintype "passive"))
    )
    (net (code "103") (name "Net-(IC6-IN+)") (class "Default")
      (node (ref "IC6") (pin "3") (pinfunction "IN+_3") (pintype "bidirectional"))
      (node (ref "L17") (pin "1") (pinfunction "1_1") (pintype "passive"))
      (node (ref "R38") (pin "1") (pinfunction "1_1") (pintype "passive"))
      (node (ref "R40") (pin "1") (pinfunction "1_1") (pintype "passive"))
    )
    (net (code "104") (name "Net-(IC6-IN-)") (class "Default")
      (node (ref "IC6") (pin "4") (pinfunction "IN-_4") (pintype "bidirectional"))
      (node (ref "L18") (pin "1") (pinfunction "1_1") (pintype "passive"))
      (node (ref "R39") (pin "1") (pinfunction "1_1") (pintype "passive"))
      (node (ref "R40") (pin "2") (pinfunction "2_2") (pintype "passive"))
    )
    (net (code "105") (name "Net-(IC6-LO+)") (class "Default")
      (node (ref "C59") (pin "2") (pinfunction "2_2") (pintype "passive"))
      (node (ref "IC6") (pin "8") (pinfunction "LO+_8") (pintype "bidirectional"))
    )
    (net (code "106") (name "Net-(IC6-LO-)") (class "Default")
      (node (ref "C45") (pin "2") (pinfunction "2_2") (pintype "passive"))
      (node (ref "IC6") (pin "1") (pinfunction "LO-_1") (pintype "bidirectional"))
    )
    (net (code "107") (name "Net-(IC6-OUT+)") (class "Default")
      (node (ref "C46") (pin "1") (pinfunction "1_1") (pintype "passive"))
      (node (ref "IC6") (pin "6") (pinfunction "OUT+_6") (pintype "bidirectional"))
      (node (ref "R27") (pin "2") (pinfunction "2_2") (pintype "passive"))
    )
    (net (code "108") (name "Net-(IC6-OUT-)") (class "Default")
      (node (ref "C47") (pin "1") (pinfunction "1_1") (pintype "passive"))
      (node (ref "IC6") (pin "5") (pinfunction "OUT-_5") (pintype "bidirectional"))
      (node (ref "R28") (pin "2") (pinfunction "2_2") (pintype "passive"))
    )
    (net (code "109") (name "Net-(IC7-+IN)") (class "Default")
      (node (ref "C46") (pin "2") (pinfunction "2_2") (pintype "passive"))
      (node (ref "C50") (pin "1") (pinfunction "1_1") (pintype "passive"))
      (node (ref "IC7") (pin "8") (pinfunction "+IN_8") (pintype "input"))
      (node (ref "R29") (pin "1") (pinfunction "1_1") (pintype "passive"))
    )
    (net (code "110") (name "Net-(IC7-+OUT)") (class "Default")
      (node (ref "C51") (pin "1") (pinfunction "1_1") (pintype "passive"))
      (node (ref "IC7") (pin "4") (pinfunction "+OUT_4") (pintype "bidirectional"))
      (node (ref "R30") (pin "1") (pinfunction "1_1") (pintype "passive"))
      (node (ref "R31") (pin "2") (pinfunction "2_2") (pintype "passive"))
    )
    (net (code "111") (name "Net-(IC7--IN)") (class "Default")
      (node (ref "C47") (pin "2") (pinfunction "2_2") (pintype "passive"))
      (node (ref "C51") (pin "2") (pinfunction "2_2") (pintype "passive"))
      (node (ref "IC7") (pin "1") (pinfunction "-IN_1") (pintype "input"))
      (node (ref "R30") (pin "2") (pinfunction "2_2") (pintype "passive"))
    )
    (net (code "112") (name "Net-(IC7--OUT)") (class "Default")
      (node (ref "C50") (pin "2") (pinfunction "2_2") (pintype "passive"))
      (node (ref "IC7") (pin "5") (pinfunction "-OUT_5") (pintype "bidirectional"))
      (node (ref "R29") (pin "2") (pinfunction "2_2") (pintype "passive"))
      (node (ref "R32") (pin "2") (pinfunction "2_2") (pintype "passive"))
    )
    (net (code "113") (name "Net-(IC7-VOCM)") (class "Default")
      (node (ref "C52") (pin "1") (pinfunction "1_1") (pintype "passive"))
      (node (ref "IC7") (pin "2") (pinfunction "VOCM_2") (pintype "output"))
    )
    (net (code "114") (name "Net-(IC8-AIN+)") (class "Default")
      (node (ref "C60") (pin "1") (pinfunction "1_1") (pintype "passive"))
      (node (ref "C61") (pin "2") (pinfunction "2_2") (pintype "passive"))
      (node (ref "IC8") (pin "3") (pinfunction "AIN+_3") (pintype "bidirectional"))
      (node (ref "L19") (pin "2") (pinfunction "2_2") (pintype "passive"))
    )
    (net (code "115") (name "Net-(IC8-AIN-)") (class "Default")
      (node (ref "C60") (pin "2") (pinfunction "2_2") (pintype "passive"))
      (node (ref "C62") (pin "1") (pinfunction "1_1") (pintype "passive"))
      (node (ref "IC8") (pin "4") (pinfunction "AIN-_4") (pintype "bidirectional"))
      (node (ref "L20") (pin "2") (pinfunction "2_2") (pintype "passive"))
    )
    (net (code "116") (name "Net-(IC9-IADJ)") (class "Default")
      (node (ref "IC9") (pin "8") (pinfunction "IADJ_8") (pintype "bidirectional"))
      (node (ref "R41") (pin "1") (pinfunction "1_1") (pintype "passive"))
    )
    (net (code "117") (name "Net-(IC9-IN+)") (class "Default")
      (node (ref "C67") (pin "2") (pinfunction "2_2") (pintype "passive"))
      (node (ref "IC9") (pin "2") (pinfunction "IN+_2") (pintype "bidirectional"))
    )
    (net (code "118") (name "Net-(IC9-IN-)") (class "Default")
      (node (ref "C68") (pin "2") (pinfunction "2_2") (pintype "passive"))
      (node (ref "IC9") (pin "3") (pinfunction "IN-_3") (pintype "bidirectional"))
    )
    (net (code "119") (name "Net-(IC9-LO+)") (class "Default")
      (node (ref "C71") (pin "2") (pinfunction "2_2") (pintype "passive"))
      (node (ref "IC9") (pin "15") (pinfunction "LO+_15") (pintype "bidirectional"))
    )
    (net (code "120") (name "Net-(IC9-LO-)") (class "Default")
      (node (ref "C70") (pin "1") (pinfunction "1_1") (pintype "passive"))
      (node (ref "IC9") (pin "14") (pinfunction "LO-_14") (pintype "bidirectional"))
    )
    (net (code "121") (name "Net-(IC9-OUT+)") (class "Default")
      (node (ref "C74") (pin "1") (pinfunction "1_1") (pintype "passive"))
      (node (ref "IC9") (pin "11") (pinfunction "OUT+_11") (pintype "bidirectional"))
      (node (ref "L21") (pin "2") (pinfunction "2_2") (pintype "passive"))
    )
    (net (code "122") (name "Net-(IC9-OUT-)") (class "Default")
      (node (ref "C87") (pin "1") (pinfunction "1_1") (pintype "passive"))
      (node (ref "IC9") (pin "10") (pinfunction "OUT-_10") (pintype "bidirectional"))
      (node (ref "L22") (pin "2") (pinfunction "2_2") (pintype "passive"))
    )
    (net (code "123") (name "Net-(IC10-IN+)") (class "Default")
      (node (ref "C90") (pin "1") (pinfunction "1_1") (pintype "passive"))
      (node (ref "IC10") (pin "3") (pinfunction "IN+_3") (pintype "bidirectional"))
      (node (ref "L25") (pin "2") (pinfunction "2_2") (pintype "passive"))
      (node (ref "L27") (pin "1") (pinfunction "1_1") (pintype "passive"))
    )
    (net (code "124") (name "Net-(IC10-IN-)") (class "Default")
      (node (ref "C90") (pin "2") (pinfunction "2_2") (pintype "passive"))
      (node (ref "IC10") (pin "4") (pinfunction "IN-_4") (pintype "bidirectional"))
      (node (ref "L26") (pin "2") (pinfunction "2_2") (pintype "passive"))
      (node (ref "L28") (pin "1") (pinfunction "1_1") (pintype "passive"))
    )
    (net (code "125") (name "Net-(IC10-LO+)") (class "Default")
      (node (ref "C91") (pin "2") (pinfunction "2_2") (pintype "passive"))
      (node (ref "IC10") (pin "8") (pinfunction "LO+_8") (pintype "bidirectional"))
    )
    (net (code "126") (name "Net-(IC10-LO-)") (class "Default")
      (node (ref "C77") (pin "2") (pinfunction "2_2") (pintype "passive"))
      (node (ref "IC10") (pin "1") (pinfunction "LO-_1") (pintype "bidirectional"))
    )
    (net (code "127") (name "Net-(IC10-OUT+)") (class "Default")
      (node (ref "C78") (pin "1") (pinfunction "1_1") (pintype "passive"))
      (node (ref "IC10") (pin "6") (pinfunction "OUT+_6") (pintype "bidirectional"))
      (node (ref "R43") (pin "2") (pinfunction "2_2") (pintype "passive"))
    )
    (net (code "128") (name "Net-(IC10-OUT-)") (class "Default")
      (node (ref "C79") (pin "1") (pinfunction "1_1") (pintype "passive"))
      (node (ref "IC10") (pin "5") (pinfunction "OUT-_5") (pintype "bidirectional"))
      (node (ref "R44") (pin "2") (pinfunction "2_2") (pintype "passive"))
    )
    (net (code "129") (name "Net-(IC11-+IN)") (class "Default")
      (node (ref "C78") (pin "2") (pinfunction "2_2") (pintype "passive"))
      (node (ref "C82") (pin "1") (pinfunction "1_1") (pintype "passive"))
      (node (ref "IC11") (pin "8") (pinfunction "+IN_8") (pintype "input"))
      (node (ref "R45") (pin "1") (pinfunction "1_1") (pintype "passive"))
    )
    (net (code "130") (name "Net-(IC11-+OUT)") (class "Default")
      (node (ref "C83") (pin "1") (pinfunction "1_1") (pintype "passive"))
      (node (ref "IC11") (pin "4") (pinfunction "+OUT_4") (pintype "bidirectional"))
      (node (ref "R46") (pin "1") (pinfunction "1_1") (pintype "passive"))
      (node (ref "R47") (pin "2") (pinfunction "2_2") (pintype "passive"))
    )
    (net (code "131") (name "Net-(IC11--IN)") (class "Default")
      (node (ref "C79") (pin "2") (pinfunction "2_2") (pintype "passive"))
      (node (ref "C83") (pin "2") (pinfunction "2_2") (pintype "passive"))
      (node (ref "IC11") (pin "1") (pinfunction "-IN_1") (pintype "input"))
      (node (ref "R46") (pin "2") (pinfunction "2_2") (pintype "passive"))
    )
    (net (code "132") (name "Net-(IC11--OUT)") (class "Default")
      (node (ref "C82") (pin "2") (pinfunction "2_2") (pintype "passive"))
      (node (ref "IC11") (pin "5") (pinfunction "-OUT_5") (pintype "bidirectional"))
      (node (ref "R45") (pin "2") (pinfunction "2_2") (pintype "passive"))
      (node (ref "R48") (pin "2") (pinfunction "2_2") (pintype "passive"))
    )
    (net (code "133") (name "Net-(IC11-VOCM)") (class "Default")
      (node (ref "C84") (pin "1") (pinfunction "1_1") (pintype "passive"))
      (node (ref "IC11") (pin "2") (pinfunction "VOCM_2") (pintype "output"))
    )
    (net (code "134") (name "Net-(IC12-AIN+)") (class "Default")
      (node (ref "C92") (pin "1") (pinfunction "1_1") (pintype "passive"))
      (node (ref "C93") (pin "2") (pinfunction "2_2") (pintype "passive"))
      (node (ref "IC12") (pin "3") (pinfunction "AIN+_3") (pintype "bidirectional"))
      (node (ref "L29") (pin "2") (pinfunction "2_2") (pintype "passive"))
    )
    (net (code "135") (name "Net-(IC12-AIN-)") (class "Default")
      (node (ref "C92") (pin "2") (pinfunction "2_2") (pintype "passive"))
      (node (ref "C94") (pin "1") (pinfunction "1_1") (pintype "passive"))
      (node (ref "IC12") (pin "4") (pinfunction "AIN-_4") (pintype "bidirectional"))
      (node (ref "L30") (pin "2") (pinfunction "2_2") (pintype "passive"))
    )
    (net (code "136") (name "Net-(IC12-AVDD)") (class "Default")
      (node (ref "C195") (pin "1") (pinfunction "1_1") (pintype "passive"))
      (node (ref "IC12") (pin "2") (pinfunction "AVDD_2") (pintype "bidirectional"))
      (node (ref "IC36") (pin "5") (pinfunction "VOUT_5") (pintype "power_in"))
      (node (ref "TP15") (pin "TP") (pinfunction "TP_TP") (pintype "input"))
    )
    (net (code "137") (name "Net-(IC13-CLK0)") (class "Default")
      (node (ref "IC13") (pin "13") (pinfunction "CLK0_13") (pintype "bidirectional"))
      (node (ref "R73") (pin "1") (pinfunction "1_1") (pintype "passive"))
      (node (ref "R74") (pin "1") (pinfunction "1_1") (pintype "passive"))
    )
    (net (code "138") (name "Net-(IC13-CLK1)") (class "Default")
      (node (ref "C102") (pin "1") (pinfunction "1_1") (pintype "passive"))
      (node (ref "IC13") (pin "12") (pinfunction "CLK1_12") (pintype "bidirectional"))
      (node (ref "L35") (pin "1") (pinfunction "1_1") (pintype "passive"))
    )
    (net (code "139") (name "Net-(IC13-CLK4)") (class "Default")
      (node (ref "C99") (pin "1") (pinfunction "1_1") (pintype "passive"))
      (node (ref "IC13") (pin "19") (pinfunction "CLK4_19") (pintype "bidirectional"))
      (node (ref "L33") (pin "1") (pinfunction "1_1") (pintype "passive"))
    )
    (net (code "140") (name "Net-(IC13-CLK5)") (class "Default")
      (node (ref "C112") (pin "1") (pinfunction "1_1") (pintype "passive"))
      (node (ref "IC13") (pin "17") (pinfunction "CLK5_17") (pintype "bidirectional"))
      (node (ref "L37") (pin "1") (pinfunction "1_1") (pintype "passive"))
    )
    (net (code "141") (name "Net-(IC13-CLK6)") (class "Default")
      (node (ref "C65") (pin "1") (pinfunction "1_1") (pintype "passive"))
      (node (ref "IC13") (pin "16") (pinfunction "CLK6_16") (pintype "bidirectional"))
    )
    (net (code "142") (name "Net-(IC13-CLKIN)") (class "Default")
      (node (ref "C107") (pin "2") (pinfunction "2_2") (pintype "passive"))
      (node (ref "IC13") (pin "6") (pinfunction "CLKIN_6") (pintype "bidirectional"))
    )
    (net (code "143") (name "Net-(IC13-OEB)") (class "Default")
      (node (ref "IC13") (pin "7") (pinfunction "OEB_7") (pintype "bidirectional"))
      (node (ref "R49") (pin "2") (pinfunction "2_2") (pintype "passive"))
    )
    (net (code "144") (name "Net-(IC13-VDDOA)") (class "Default")
      (node (ref "C104") (pin "2") (pinfunction "2_2") (pintype "passive"))
      (node (ref "C105") (pin "2") (pinfunction "2_2") (pintype "passive"))
      (node (ref "IC13") (pin "10") (pinfunction "VDDOB_10") (pintype "bidirectional"))
      (node (ref "IC13") (pin "11") (pinfunction "VDDOA_11") (pintype "bidirectional"))
      (node (ref "IC13") (pin "14") (pinfunction "VDDOD_14") (pintype "bidirectional"))
      (node (ref "IC13") (pin "18") (pinfunction "VDDOC_18") (pintype "bidirectional"))
      (node (ref "L31") (pin "2") (pinfunction "2_2") (pintype "passive"))
    )
    (net (code "145") (name "Net-(IC13-XA)") (class "Default")
      (node (ref "C109") (pin "2") (pinfunction "2_2") (pintype "passive"))
      (node (ref "IC13") (pin "1") (pinfunction "XA_1") (pintype "bidirectional"))
      (node (ref "Q1") (pin "3") (pinfunction "3_3") (pintype "passive"))
    )
    (net (code "146") (name "Net-(IC13-XB)") (class "Default")
      (node (ref "C108") (pin "2") (pinfunction "2_2") (pintype "passive"))
      (node (ref "IC13") (pin "2") (pinfunction "XB_2") (pintype "bidirectional"))
      (node (ref "Q1") (pin "1") (pinfunction "1_1") (pintype "passive"))
    )
    (net (code "147") (name "Net-(IC14-BIAS_FILT)") (class "Default")
      (node (ref "C116") (pin "1") (pinfunction "1_1") (pintype "passive"))
      (node (ref "IC14") (pin "23") (pinfunction "BIAS_FILT_23") (pintype "bidirectional"))
    )
    (net (code "148") (name "Net-(IC14-CP_OUT)") (class "Default")
      (node (ref "C117") (pin "1") (pinfunction "1_1") (pintype "passive"))
      (node (ref "C119") (pin "1") (pinfunction "1_1") (pintype "passive"))
      (node (ref "IC14") (pin "7") (pinfunction "CP_OUT_7") (pintype "bidirectional"))
      (node (ref "R50") (pin "1") (pinfunction "1_1") (pintype "passive"))
    )
    (net (code "149") (name "Net-(IC14-NOISE_FILT)") (class "Default")
      (node (ref "C115") (pin "1") (pinfunction "1_1") (pintype "passive"))
      (node (ref "IC14") (pin "19") (pinfunction "NOISE_FILT_19") (pintype "bidirectional"))
    )
    (net (code "150") (name "Net-(IC14-REF_IN)") (class "Default")
      (node (ref "C130") (pin "2") (pinfunction "2_2") (pintype "passive"))
      (node (ref "IC14") (pin "29") (pinfunction "REF_IN_29") (pintype "input"))
    )
    (net (code "151") (name "Net-(IC14-REG)") (class "Default")
      (node (ref "C114") (pin "1") (pinfunction "1_1") (pintype "passive"))
      (node (ref "IC14") (pin "24") (pinfunction "REG_24") (pintype "bidirectional"))
    )
    (net (code "152") (name "Net-(IC14-RFOUTA_N)") (class "Default")
      (node (ref "C131") (pin "2") (pinfunction "2_2") (pintype "passive"))
      (node (ref "IC14") (pin "13") (pinfunction "RFOUTA_N_13") (pintype "bidirectional"))
      (node (ref "R54") (pin "1") (pinfunction "1_1") (pintype "passive"))
    )
    (net (code "153") (name "Net-(IC14-RFOUTA_P)") (class "Default")
      (node (ref "C132") (pin "1") (pinfunction "1_1") (pintype "passive"))
      (node (ref "IC14") (pin "12") (pinfunction "RFOUTA_P_12") (pintype "bidirectional"))
      (node (ref "R55") (pin "1") (pinfunction "1_1") (pintype "passive"))
    )
    (net (code "154") (name "Net-(IC14-RSET)") (class "Default")
      (node (ref "IC14") (pin "22") (pinfunction "RSET_22") (pintype "bidirectional"))
      (node (ref "R53") (pin "2") (pinfunction "2_2") (pintype "passive"))
    )
    (net (code "155") (name "Net-(IC14-SW)") (class "Default")
      (node (ref "IC14") (pin "5") (pinfunction "SW_5") (pintype "bidirectional"))
      (node (ref "R51") (pin "2") (pinfunction "2_2") (pintype "passive"))
      (node (ref "R52") (pin "1") (pinfunction "1_1") (pintype "passive"))
    )
    (net (code "156") (name "Net-(IC14-TUNE)") (class "Default")
      (node (ref "C118") (pin "2") (pinfunction "2_2") (pintype "passive"))
      (node (ref "IC14") (pin "20") (pinfunction "TUNE_20") (pintype "bidirectional"))
      (node (ref "R50") (pin "2") (pinfunction "2_2") (pintype "passive"))
    )
    (net (code "157") (name "Net-(IC14-VCC_RF)") (class "Default")
      (node (ref "C129") (pin "1") (pinfunction "1_1") (pintype "passive"))
      (node (ref "IC14") (pin "16") (pinfunction "VCC_RF_16") (pintype "bidirectional"))
      (node (ref "IC14") (pin "17") (pinfunction "VCC_VCO_17") (pintype "bidirectional"))
      (node (ref "L38") (pin "2") (pinfunction "2_2") (pintype "passive"))
      (node (ref "R54") (pin "2") (pinfunction "2_2") (pintype "passive"))
      (node (ref "R55") (pin "2") (pinfunction "2_2") (pintype "passive"))
      (node (ref "TP16") (pin "TP") (pinfunction "TP_TP") (pintype "input"))
    )
    (net (code "158") (name "Net-(IC15-VOUT)") (class "Default")
      (node (ref "C124") (pin "1") (pinfunction "1_1") (pintype "passive"))
      (node (ref "IC15") (pin "5") (pinfunction "VOUT_5") (pintype "power_in"))
      (node (ref "L39") (pin "1") (pinfunction "1_1") (pintype "passive"))
    )
    (net (code "159") (name "Net-(IC16-ANT)") (class "Default")
      (node (ref "C132") (pin "2") (pinfunction "2_2") (pintype "passive"))
      (node (ref "IC16") (pin "7") (pinfunction "ANT_7") (pintype "bidirectional"))
    )
    (net (code "160") (name "Net-(IC16-C1)") (class "Default")
      (node (ref "IC16") (pin "2") (pinfunction "C1_2") (pintype "bidirectional"))
      (node (ref "R97") (pin "1") (pinfunction "1_1") (pintype "passive"))
      (node (ref "R99") (pin "1") (pinfunction "1_1") (pintype "passive"))
    )
    (net (code "161") (name "Net-(IC16-C2)") (class "Default")
      (node (ref "IC16") (pin "1") (pinfunction "C2_1") (pintype "bidirectional"))
      (node (ref "R100") (pin "1") (pinfunction "1_1") (pintype "passive"))
      (node (ref "R98") (pin "1") (pinfunction "1_1") (pintype "passive"))
    )
    (net (code "162") (name "Net-(IC16-RF1)") (class "Default")
      (node (ref "IC16") (pin "9") (pinfunction "RF1_9") (pintype "bidirectional"))
      (node (ref "IC18") (pin "6") (pinfunction "RF3_6") (pintype "bidirectional"))
    )
    (net (code "163") (name "Net-(IC16-RF2)") (class "Default")
      (node (ref "IC16") (pin "11") (pinfunction "RF2_11") (pintype "bidirectional"))
      (node (ref "LP1") (pin "4") (pinfunction "IN_4") (pintype "bidirectional"))
    )
    (net (code "164") (name "Net-(IC16-RF3)") (class "Default")
      (node (ref "IC16") (pin "6") (pinfunction "RF3_6") (pintype "bidirectional"))
      (node (ref "LP2") (pin "4") (pinfunction "IN_4") (pintype "bidirectional"))
    )
    (net (code "165") (name "Net-(IC16-RF4)") (class "Default")
      (node (ref "IC16") (pin "4") (pinfunction "RF4_4") (pintype "bidirectional"))
      (node (ref "LP3") (pin "4") (pinfunction "IN_4") (pintype "bidirectional"))
    )
    (net (code "166") (name "Net-(IC18-ANT)") (class "Default")
      (node (ref "C121") (pin "1") (pinfunction "1_1") (pintype "passive"))
      (node (ref "IC18") (pin "7") (pinfunction "ANT_7") (pintype "bidirectional"))
    )
    (net (code "167") (name "Net-(IC18-C1)") (class "Default")
      (node (ref "IC18") (pin "2") (pinfunction "C1_2") (pintype "bidirectional"))
      (node (ref "R102") (pin "1") (pinfunction "1_1") (pintype "passive"))
      (node (ref "R104") (pin "1") (pinfunction "1_1") (pintype "passive"))
    )
    (net (code "168") (name "Net-(IC18-C2)") (class "Default")
      (node (ref "IC18") (pin "1") (pinfunction "C2_1") (pintype "bidirectional"))
      (node (ref "R101") (pin "1") (pinfunction "1_1") (pintype "passive"))
      (node (ref "R103") (pin "1") (pinfunction "1_1") (pintype "passive"))
    )
    (net (code "169") (name "Net-(IC18-RF1)") (class "Default")
      (node (ref "IC18") (pin "9") (pinfunction "RF1_9") (pintype "bidirectional"))
      (node (ref "LP2") (pin "1") (pinfunction "OUT_1") (pintype "bidirectional"))
    )
    (net (code "170") (name "Net-(IC18-RF2)") (class "Default")
      (node (ref "IC18") (pin "11") (pinfunction "RF2_11") (pintype "bidirectional"))
      (node (ref "LP3") (pin "1") (pinfunction "OUT_1") (pintype "bidirectional"))
    )
    (net (code "171") (name "Net-(IC18-RF4)") (class "Default")
      (node (ref "IC18") (pin "4") (pinfunction "RF4_4") (pintype "bidirectional"))
      (node (ref "LP1") (pin "1") (pinfunction "OUT_1") (pintype "bidirectional"))
    )
    (net (code "172") (name "Net-(IC19-BIAS_FILT)") (class "Default")
      (node (ref "C134") (pin "1") (pinfunction "1_1") (pintype "passive"))
      (node (ref "IC19") (pin "23") (pinfunction "BIAS_FILT_23") (pintype "bidirectional"))
    )
    (net (code "173") (name "Net-(IC19-CP_OUT)") (class "Default")
      (node (ref "C135") (pin "1") (pinfunction "1_1") (pintype "passive"))
      (node (ref "C137") (pin "1") (pinfunction "1_1") (pintype "passive"))
      (node (ref "IC19") (pin "7") (pinfunction "CP_OUT_7") (pintype "bidirectional"))
      (node (ref "R58") (pin "1") (pinfunction "1_1") (pintype "passive"))
    )
    (net (code "174") (name "Net-(IC19-NOISE_FILT)") (class "Default")
      (node (ref "C133") (pin "1") (pinfunction "1_1") (pintype "passive"))
      (node (ref "IC19") (pin "19") (pinfunction "NOISE_FILT_19") (pintype "bidirectional"))
    )
    (net (code "175") (name "Net-(IC19-REF_IN)") (class "Default")
      (node (ref "C146") (pin "2") (pinfunction "2_2") (pintype "passive"))
      (node (ref "IC19") (pin "29") (pinfunction "REF_IN_29") (pintype "input"))
    )
    (net (code "176") (name "Net-(IC19-REG)") (class "Default")
      (node (ref "C122") (pin "1") (pinfunction "1_1") (pintype "passive"))
      (node (ref "IC19") (pin "24") (pinfunction "REG_24") (pintype "bidirectional"))
    )
    (net (code "177") (name "Net-(IC19-RFOUTB_N)") (class "Default")
      (node (ref "C147") (pin "2") (pinfunction "2_2") (pintype "passive"))
      (node (ref "IC19") (pin "15") (pinfunction "RFOUTB_N_15") (pintype "bidirectional"))
      (node (ref "R66") (pin "1") (pinfunction "1_1") (pintype "passive"))
    )
    (net (code "178") (name "Net-(IC19-RSET)") (class "Default")
      (node (ref "IC19") (pin "22") (pinfunction "RSET_22") (pintype "bidirectional"))
      (node (ref "R61") (pin "2") (pinfunction "2_2") (pintype "passive"))
    )
    (net (code "179") (name "Net-(IC19-SW)") (class "Default")
      (node (ref "IC19") (pin "5") (pinfunction "SW_5") (pintype "bidirectional"))
      (node (ref "R59") (pin "2") (pinfunction "2_2") (pintype "passive"))
      (node (ref "R60") (pin "1") (pinfunction "1_1") (pintype "passive"))
    )
    (net (code "180") (name "Net-(IC19-TUNE)") (class "Default")
      (node (ref "C136") (pin "2") (pinfunction "2_2") (pintype "passive"))
      (node (ref "IC19") (pin "20") (pinfunction "TUNE_20") (pintype "bidirectional"))
      (node (ref "R58") (pin "2") (pinfunction "2_2") (pintype "passive"))
    )
    (net (code "181") (name "Net-(IC19-VCC_CP)") (class "Default")
      (node (ref "C144") (pin "1") (pinfunction "1_1") (pintype "passive"))
      (node (ref "IC19") (pin "10") (pinfunction "VCC_PLL_10") (pintype "bidirectional"))
      (node (ref "IC19") (pin "6") (pinfunction "VCC_CP_6") (pintype "bidirectional"))
      (node (ref "L41") (pin "2") (pinfunction "2_2") (pintype "passive"))
      (node (ref "TP18") (pin "TP") (pinfunction "TP_TP") (pintype "input"))
    )
    (net (code "182") (name "Net-(IC19-VCC_RF)") (class "Default")
      (node (ref "C145") (pin "1") (pinfunction "1_1") (pintype "passive"))
      (node (ref "IC19") (pin "16") (pinfunction "VCC_RF_16") (pintype "bidirectional"))
      (node (ref "IC19") (pin "17") (pinfunction "VCC_VCO_17") (pintype "bidirectional"))
      (node (ref "L40") (pin "2") (pinfunction "2_2") (pintype "passive"))
      (node (ref "R62") (pin "2") (pinfunction "2_2") (pintype "passive"))
      (node (ref "R63") (pin "2") (pinfunction "2_2") (pintype "passive"))
      (node (ref "R65") (pin "2") (pinfunction "2_2") (pintype "passive"))
      (node (ref "R66") (pin "2") (pinfunction "2_2") (pintype "passive"))
      (node (ref "TP19") (pin "TP") (pinfunction "TP_TP") (pintype "input"))
    )
    (net (code "183") (name "Net-(IC20-VOUT)") (class "Default")
      (node (ref "C140") (pin "1") (pinfunction "1_1") (pintype "passive"))
      (node (ref "IC20") (pin "5") (pinfunction "VOUT_5") (pintype "power_in"))
      (node (ref "L41") (pin "1") (pinfunction "1_1") (pintype "passive"))
    )
    (net (code "184") (name "Net-(IC22-MODE_CTL)") (class "Default")
      (node (ref "C149") (pin "1") (pinfunction "1_1") (pintype "passive"))
      (node (ref "IC22") (pin "19") (pinfunction "MODE_CTL_19") (pintype "bidirectional"))
      (node (ref "IC22") (pin "20") (pinfunction "VCC_20") (pintype "bidirectional"))
      (node (ref "L42") (pin "2") (pinfunction "2_2") (pintype "passive"))
    )
    (net (code "185") (name "Net-(IC22-RF_COM)") (class "Default")
      (node (ref "IC22") (pin "8") (pinfunction "RF_COM_8") (pintype "bidirectional"))
      (node (ref "R68") (pin "1") (pinfunction "1_1") (pintype "passive"))
    )
    (net (code "186") (name "Net-(IC23-RF1)") (class "Default")
      (node (ref "IC23") (pin "5") (pinfunction "RF1_5") (pintype "bidirectional"))
      (node (ref "R68") (pin "2") (pinfunction "2_2") (pintype "passive"))
    )
    (net (code "187") (name "Net-(IC23-RF2)") (class "Default")
      (node (ref "C150") (pin "1") (pinfunction "1_1") (pintype "passive"))
      (node (ref "IC23") (pin "14") (pinfunction "RF2_14") (pintype "bidirectional"))
    )
    (net (code "188") (name "Net-(IC23-VDD)") (class "Default")
      (node (ref "C148") (pin "1") (pinfunction "1_1") (pintype "passive"))
      (node (ref "IC23") (pin "2") (pinfunction "VDD_2") (pintype "bidirectional"))
      (node (ref "L43") (pin "2") (pinfunction "2_2") (pintype "passive"))
    )
    (net (code "189") (name "Net-(IC24-RFIN)") (class "Default")
      (node (ref "C150") (pin "2") (pinfunction "2_2") (pintype "passive"))
      (node (ref "IC24") (pin "2") (pinfunction "RFIN_2") (pintype "bidirectional"))
    )
    (net (code "190") (name "Net-(IC24-RFOUT)") (class "Default")
      (node (ref "C153") (pin "1") (pinfunction "1_1") (pintype "passive"))
      (node (ref "IC24") (pin "7") (pinfunction "RFOUT_7") (pintype "bidirectional"))
      (node (ref "L44") (pin "2") (pinfunction "2_2") (pintype "passive"))
    )
    (net (code "191") (name "Net-(IC24-VCC)") (class "Default")
      (node (ref "C151") (pin "1") (pinfunction "1_1") (pintype "passive"))
      (node (ref "C152") (pin "1") (pinfunction "1_1") (pintype "passive"))
      (node (ref "IC24") (pin "1") (pinfunction "VCC_1") (pintype "bidirectional"))
      (node (ref "L44") (pin "1") (pinfunction "1_1") (pintype "passive"))
      (node (ref "L45") (pin "2") (pinfunction "2_2") (pintype "passive"))
    )
    (net (code "192") (name "Net-(IC25-MODE_CTL)") (class "Default")
      (node (ref "C154") (pin "1") (pinfunction "1_1") (pintype "passive"))
      (node (ref "C155") (pin "1") (pinfunction "1_1") (pintype "passive"))
      (node (ref "C156") (pin "1") (pinfunction "1_1") (pintype "passive"))
      (node (ref "IC25") (pin "19") (pinfunction "MODE_CTL_19") (pintype "bidirectional"))
      (node (ref "IC25") (pin "20") (pinfunction "VCC_20") (pintype "bidirectional"))
      (node (ref "IC26") (pin "19") (pinfunction "MODE_CTL_19") (pintype "bidirectional"))
      (node (ref "IC26") (pin "20") (pinfunction "VCC_20") (pintype "bidirectional"))
      (node (ref "IC27") (pin "19") (pinfunction "MODE_CTL_19") (pintype "bidirectional"))
      (node (ref "IC27") (pin "20") (pinfunction "VCC_20") (pintype "bidirectional"))
      (node (ref "L46") (pin "2") (pinfunction "2_2") (pintype "passive"))
    )
    (net (code "193") (name "Net-(IC25-RF1)") (class "Default")
      (node (ref "IC25") (pin "3") (pinfunction "RF1_3") (pintype "bidirectional"))
      (node (ref "IC27") (pin "8") (pinfunction "RF_COM_8") (pintype "bidirectional"))
    )
    (net (code "194") (name "Net-(IC25-RF2)") (class "Default")
      (node (ref "IC25") (pin "13") (pinfunction "RF2_13") (pintype "bidirectional"))
      (node (ref "IC26") (pin "8") (pinfunction "RF_COM_8") (pintype "bidirectional"))
    )
    (net (code "195") (name "Net-(IC25-RF_COM)") (class "Default")
      (node (ref "IC25") (pin "8") (pinfunction "RF_COM_8") (pintype "bidirectional"))
      (node (ref "R70") (pin "2") (pinfunction "2_2") (pintype "passive"))
    )
    (net (code "196") (name "Net-(IC28-EN)") (class "Default")
      (node (ref "C106") (pin "2") (pinfunction "2_2") (pintype "passive"))
      (node (ref "C158") (pin "2") (pinfunction "2_2") (pintype "passive"))
      (node (ref "C160") (pin "2") (pinfunction "2_2") (pintype "passive"))
      (node (ref "C162") (pin "2") (pinfunction "2_2") (pintype "passive"))
      (node (ref "C174") (pin "1") (pinfunction "1_1") (pintype "passive"))
      (node (ref "C181") (pin "1") (pinfunction "1_1") (pintype "passive"))
      (node (ref "IC28") (pin "4") (pinfunction "VIN_4") (pintype "bidirectional"))
      (node (ref "IC28") (pin "6") (pinfunction "EN_6") (pintype "bidirectional"))
      (node (ref "IC29") (pin "4") (pinfunction "VIN_4") (pintype "bidirectional"))
      (node (ref "IC29") (pin "6") (pinfunction "EN_6") (pintype "bidirectional"))
      (node (ref "IC30") (pin "4") (pinfunction "VIN_4") (pintype "bidirectional"))
      (node (ref "IC30") (pin "6") (pinfunction "EN_6") (pintype "bidirectional"))
      (node (ref "IC31") (pin "4") (pinfunction "VIN_4") (pintype "bidirectional"))
      (node (ref "IC31") (pin "6") (pinfunction "EN_6") (pintype "bidirectional"))
      (node (ref "L51") (pin "P$2") (pinfunction "2_P$2") (pintype "passive"))
      (node (ref "TP5") (pin "TP") (pinfunction "TP_TP") (pintype "input"))
    )
    (net (code "197") (name "Net-(IC28-SENSE)") (class "Default")
      (node (ref "C113") (pin "2") (pinfunction "2_2") (pintype "passive"))
      (node (ref "IC28") (pin "2") (pinfunction "SENSE_2") (pintype "bidirectional"))
      (node (ref "IC28") (pin "3") (pinfunction "VOUT_3") (pintype "bidirectional"))
      (node (ref "L47") (pin "1") (pinfunction "1_1") (pintype "passive"))
    )
    (net (code "198") (name "Net-(IC29-SENSE)") (class "Default")
      (node (ref "C159") (pin "2") (pinfunction "2_2") (pintype "passive"))
      (node (ref "IC29") (pin "2") (pinfunction "SENSE_2") (pintype "bidirectional"))
      (node (ref "IC29") (pin "3") (pinfunction "VOUT_3") (pintype "bidirectional"))
      (node (ref "L48") (pin "1") (pinfunction "1_1") (pintype "passive"))
    )
    (net (code "199") (name "Net-(IC30-SENSE)") (class "Default")
      (node (ref "C161") (pin "2") (pinfunction "2_2") (pintype "passive"))
      (node (ref "IC30") (pin "2") (pinfunction "SENSE_2") (pintype "bidirectional"))
      (node (ref "IC30") (pin "3") (pinfunction "VOUT_3") (pintype "bidirectional"))
      (node (ref "L49") (pin "1") (pinfunction "1_1") (pintype "passive"))
    )
    (net (code "200") (name "Net-(IC31-SENSE)") (class "Default")
      (node (ref "C163") (pin "2") (pinfunction "2_2") (pintype "passive"))
      (node (ref "IC31") (pin "2") (pinfunction "SENSE_2") (pintype "bidirectional"))
      (node (ref "IC31") (pin "3") (pinfunction "VOUT_3") (pintype "bidirectional"))
      (node (ref "L50") (pin "1") (pinfunction "1_1") (pintype "passive"))
    )
    (net (code "201") (name "Net-(IC32A-PSM)") (class "Default")
      (node (ref "IC32") (pin "32") (pinfunction "PSM_32") (pintype "bidirectional"))
      (node (ref "R77") (pin "2") (pinfunction "2_2") (pintype "passive"))
    )
    (net (code "202") (name "Net-(IC32A-V7V)") (class "Default")
      (node (ref "C168") (pin "2") (pinfunction "2_2") (pintype "passive"))
      (node (ref "IC32") (pin "1") (pinfunction "V7V_1") (pintype "bidirectional"))
    )
    (net (code "203") (name "Net-(IC32B-BST)") (class "Default")
      (node (ref "C178") (pin "2") (pinfunction "2_2") (pintype "passive"))
      (node (ref "IC32") (pin "25") (pinfunction "BST_25") (pintype "bidirectional"))
    )
    (net (code "204") (name "Net-(IC32B-COMP)") (class "Default")
      (node (ref "C182") (pin "2") (pinfunction "2_2") (pintype "passive"))
      (node (ref "IC32") (pin "23") (pinfunction "COMP_23") (pintype "bidirectional"))
      (node (ref "R79") (pin "2") (pinfunction "2_2") (pintype "passive"))
    )
    (net (code "205") (name "Net-(IC32B-FB)") (class "Default")
      (node (ref "C183") (pin "2") (pinfunction "2_2") (pintype "passive"))
      (node (ref "IC32") (pin "22") (pinfunction "FB_22") (pintype "bidirectional"))
      (node (ref "R80") (pin "2") (pinfunction "2_2") (pintype "passive"))
      (node (ref "R81") (pin "1") (pinfunction "1_1") (pintype "passive"))
    )
    (net (code "206") (name "Net-(IC32C-BST)") (class "Default")
      (node (ref "C175") (pin "2") (pinfunction "2_2") (pintype "passive"))
      (node (ref "IC32") (pin "9") (pinfunction "BST_9") (pintype "bidirectional"))
    )
    (net (code "207") (name "Net-(IC32C-COMP)") (class "Default")
      (node (ref "C176") (pin "2") (pinfunction "2_2") (pintype "passive"))
      (node (ref "IC32") (pin "7") (pinfunction "COMP_7") (pintype "bidirectional"))
      (node (ref "R82") (pin "2") (pinfunction "2_2") (pintype "passive"))
    )
    (net (code "208") (name "Net-(IC32C-FB)") (class "Default")
      (node (ref "C179") (pin "2") (pinfunction "2_2") (pintype "passive"))
      (node (ref "IC32") (pin "6") (pinfunction "FB_6") (pintype "bidirectional"))
      (node (ref "R83") (pin "2") (pinfunction "2_2") (pintype "passive"))
      (node (ref "R84") (pin "1") (pinfunction "1_1") (pintype "passive"))
    )
    (net (code "209") (name "Net-(IC32C-LX)") (class "Default")
      (node (ref "C175") (pin "1") (pinfunction "1_1") (pintype "passive"))
      (node (ref "IC32") (pin "11") (pinfunction "LX_11") (pintype "bidirectional"))
      (node (ref "L53") (pin "P$1") (pinfunction "1_P$1") (pintype "passive"))
    )
    (net (code "210") (name "Net-(IC32D-BST)") (class "Default")
      (node (ref "C186") (pin "2") (pinfunction "2_2") (pintype "passive"))
      (node (ref "IC32") (pin "16") (pinfunction "BST_16") (pintype "bidirectional"))
    )
    (net (code "211") (name "Net-(IC32D-COMP)") (class "Default")
      (node (ref "C187") (pin "2") (pinfunction "2_2") (pintype "passive"))
      (node (ref "IC32") (pin "18") (pinfunction "COMP_18") (pintype "bidirectional"))
      (node (ref "R85") (pin "2") (pinfunction "2_2") (pintype "passive"))
    )
    (net (code "212") (name "Net-(IC32D-FB)") (class "Default")
      (node (ref "C188") (pin "2") (pinfunction "2_2") (pintype "passive"))
      (node (ref "IC32") (pin "19") (pinfunction "FB_19") (pintype "bidirectional"))
      (node (ref "R86") (pin "2") (pinfunction "2_2") (pintype "passive"))
      (node (ref "R87") (pin "1") (pinfunction "1_1") (pintype "passive"))
    )
    (net (code "213") (name "Net-(IC32D-LX)") (class "Default")
      (node (ref "C186") (pin "1") (pinfunction "1_1") (pintype "passive"))
      (node (ref "IC32") (pin "14") (pinfunction "LX_14") (pintype "bidirectional"))
      (node (ref "L54") (pin "P$1") (pinfunction "1_P$1") (pintype "passive"))
    )
    (net (code "214") (name "Net-(IC33-NRST)") (class "Default")
      (node (ref "IC33") (pin "4") (pinfunction "NRST_4") (pintype "bidirectional"))
      (node (ref "JP1") (pin "5") (pinfunction "5_5") (pintype "passive"))
    )
    (net (code "215") (name "Net-(IC33-PA2{slash}TIM2_CH3{slash}USART2_TX)") (class "Default")
      (node (ref "IC33") (pin "8") (pinfunction "PA2/TIM2_CH3/USART2_TX_8") (pintype "bidirectional"))
      (node (ref "JP1") (pin "6") (pinfunction "6_6") (pintype "passive"))
    )
    (net (code "216") (name "Net-(IC33-PA11{slash}TIM1_CH4{slash}SPI1_MISO{slash}CAN1_RX{slash}USB_DM)") (class "Default")
      (node (ref "IC33") (pin "21") (pinfunction "PA11/TIM1_CH4/SPI1_MISO/CAN1_RX/USB_DM_21") (pintype "bidirectional"))
      (node (ref "R88") (pin "2") (pinfunction "2_2") (pintype "passive"))
    )
    (net (code "217") (name "Net-(IC33-PA12{slash}SPI1_MOSI{slash}CAN1_TX{slash}USB_DP)") (class "Default")
      (node (ref "IC33") (pin "22") (pinfunction "PA12/SPI1_MOSI/CAN1_TX/USB_DP_22") (pintype "bidirectional"))
      (node (ref "R76") (pin "1") (pinfunction "1_1") (pintype "passive"))
    )
    (net (code "218") (name "Net-(IC33-PA13{slash}SWDIO)") (class "Default")
      (node (ref "IC33") (pin "23") (pinfunction "PA13/SWDIO_23") (pintype "bidirectional"))
      (node (ref "JP1") (pin "4") (pinfunction "4_4") (pintype "passive"))
    )
    (net (code "219") (name "Net-(IC33-PA14{slash}SWCLK)") (class "Default")
      (node (ref "IC33") (pin "24") (pinfunction "PA14/SWCLK_24") (pintype "bidirectional"))
      (node (ref "JP1") (pin "2") (pinfunction "2_2") (pintype "passive"))
    )
    (net (code "220") (name "Net-(IC33-PA15{slash}TIM2_CH1{slash}USART2_RX{slash}SPI1_NSS{slash}SPI3_NSS)") (class "Default")
      (node (ref "IC33") (pin "25") (pinfunction "PA15/TIM2_CH1/USART2_RX/SPI1_NSS/SPI3_NSS_25") (pintype "bidirectional"))
      (node (ref "R89") (pin "1") (pinfunction "1_1") (pintype "passive"))
    )
    (net (code "221") (name "Net-(IC34-VOUT)") (class "Default")
      (node (ref "C194") (pin "1") (pinfunction "1_1") (pintype "passive"))
      (node (ref "IC34") (pin "5") (pinfunction "VOUT_5") (pintype "power_in"))
      (node (ref "IC4") (pin "2") (pinfunction "AVDD_2") (pintype "bidirectional"))
      (node (ref "TP2") (pin "TP") (pinfunction "TP_TP") (pintype "input"))
    )
    (net (code "222") (name "Net-(IC35-VOUT)") (class "Default")
      (node (ref "C63") (pin "1") (pinfunction "1_1") (pintype "passive"))
      (node (ref "IC35") (pin "5") (pinfunction "VOUT_5") (pintype "power_in"))
      (node (ref "IC8") (pin "2") (pinfunction "AVDD_2") (pintype "bidirectional"))
      (node (ref "TP4") (pin "TP") (pinfunction "TP_TP") (pintype "input"))
    )
    (net (code "223") (name "Net-(J1-ANT)") (class "Default")
      (node (ref "C107") (pin "1") (pinfunction "1_1") (pintype "passive"))
      (node (ref "J1") (pin "SIG") (pinfunction "ANT_SIG") (pintype "bidirectional"))
    )
    (net (code "224") (name "Net-(J2-ANT)") (class "Default")
      (node (ref "C65") (pin "2") (pinfunction "2_2") (pintype "passive"))
      (node (ref "J2") (pin "SIG") (pinfunction "ANT_SIG") (pintype "bidirectional"))
    )
    (net (code "225") (name "Net-(L51-1)") (class "Default")
      (node (ref "C170") (pin "1") (pinfunction "1_1") (pintype "passive"))
      (node (ref "C171") (pin "1") (pinfunction "1_1") (pintype "passive"))
      (node (ref "C183") (pin "1") (pinfunction "1_1") (pintype "passive"))
      (node (ref "L51") (pin "P$1") (pinfunction "1_P$1") (pintype "passive"))
      (node (ref "L52") (pin "P$2") (pinfunction "2_P$2") (pintype "passive"))
      (node (ref "R81") (pin "2") (pinfunction "2_2") (pintype "passive"))
    )
    (net (code "226") (name "Net-(L52-1)") (class "Default")
      (node (ref "C178") (pin "1") (pinfunction "1_1") (pintype "passive"))
      (node (ref "IC32") (pin "28") (pinfunction "LX_28") (pintype "bidirectional"))
      (node (ref "IC32") (pin "29") (pinfunction "LX_29") (pintype "bidirectional"))
      (node (ref "L52") (pin "P$1") (pinfunction "1_P$1") (pintype "passive"))
    )
    (net (code "227") (name "Net-(L53-2)") (class "Default")
      (node (ref "C169") (pin "1") (pinfunction "1_1") (pintype "passive"))
      (node (ref "C172") (pin "1") (pinfunction "1_1") (pintype "passive"))
      (node (ref "C179") (pin "1") (pinfunction "1_1") (pintype "passive"))
      (node (ref "L53") (pin "P$2") (pinfunction "2_P$2") (pintype "passive"))
      (node (ref "L55") (pin "P$1") (pinfunction "1_P$1") (pintype "passive"))
      (node (ref "R84") (pin "2") (pinfunction "2_2") (pintype "passive"))
    )
    (net (code "228") (name "Net-(LED1-PadC)") (class "Default")
      (node (ref "LED1") (pin "C") (pinfunction "C_C") (pintype "passive"))
      (node (ref "R110") (pin "1") (pinfunction "1_1") (pintype "passive"))
    )
    (net (code "229") (name "Net-(LED2-PadC)") (class "Default")
      (node (ref "LED2") (pin "C") (pinfunction "C_C") (pintype "passive"))
      (node (ref "R109") (pin "1") (pinfunction "1_1") (pintype "passive"))
    )
    (net (code "230") (name "Net-(LED3-PadC)") (class "Default")
      (node (ref "LED3") (pin "C") (pinfunction "C_C") (pintype "passive"))
      (node (ref "R108") (pin "1") (pinfunction "1_1") (pintype "passive"))
    )
    (net (code "231") (name "Net-(LED4-PadC)") (class "Default")
      (node (ref "LED4") (pin "C") (pinfunction "C_C") (pintype "passive"))
      (node (ref "R107") (pin "1") (pinfunction "1_1") (pintype "passive"))
    )
    (net (code "232") (name "Net-(LED5-PadC)") (class "Default")
      (node (ref "LED5") (pin "C") (pinfunction "C_C") (pintype "passive"))
      (node (ref "R106") (pin "1") (pinfunction "1_1") (pintype "passive"))
    )
    (net (code "233") (name "Net-(LED6-PadC)") (class "Default")
      (node (ref "LED6") (pin "C") (pinfunction "C_C") (pintype "passive"))
      (node (ref "R105") (pin "1") (pinfunction "1_1") (pintype "passive"))
    )
    (net (code "234") (name "Net-(LED7-PadC)") (class "Default")
      (node (ref "LED7") (pin "C") (pinfunction "C_C") (pintype "passive"))
      (node (ref "R42") (pin "1") (pinfunction "1_1") (pintype "passive"))
    )
    (net (code "235") (name "Net-(LED8-PadC)") (class "Default")
      (node (ref "LED8") (pin "C") (pinfunction "C_C") (pintype "passive"))
      (node (ref "R26") (pin "1") (pinfunction "1_1") (pintype "passive"))
    )
    (net (code "236") (name "Net-(LED9-PadC)") (class "Default")
      (node (ref "LED9") (pin "C") (pinfunction "C_C") (pintype "passive"))
      (node (ref "R14") (pin "1") (pinfunction "1_1") (pintype "passive"))
    )
    (net (code "237") (name "Net-(R3-Pad1)") (class "Default")
      (node (ref "R3") (pin "1") (pinfunction "1_1") (pintype "passive"))
      (node (ref "R4") (pin "2") (pinfunction "2_2") (pintype "passive"))
      (node (ref "R5") (pin "1") (pinfunction "1_1") (pintype "passive"))
      (node (ref "R6") (pin "2") (pinfunction "2_2") (pintype "passive"))
      (node (ref "R7") (pin "2") (pinfunction "2_2") (pintype "passive"))
    )
    (net (code "238") (name "Net-(R12-Pad1)") (class "Default")
      (node (ref "R12") (pin "1") (pinfunction "1_1") (pintype "passive"))
      (node (ref "R13") (pin "2") (pinfunction "2_2") (pintype "passive"))
      (node (ref "R21") (pin "1") (pinfunction "1_1") (pintype "passive"))
      (node (ref "R22") (pin "2") (pinfunction "2_2") (pintype "passive"))
      (node (ref "R23") (pin "2") (pinfunction "2_2") (pintype "passive"))
    )
    (net (code "239") (name "Net-(R69-Pad2)") (class "Default")
      (node (ref "R69") (pin "2") (pinfunction "2_2") (pintype "passive"))
      (node (ref "R70") (pin "1") (pinfunction "1_1") (pintype "passive"))
      (node (ref "R71") (pin "2") (pinfunction "2_2") (pintype "passive"))
    )
    (net (code "240") (name "Net-(R76-Pad2)") (class "Default")
      (node (ref "R76") (pin "2") (pinfunction "2_2") (pintype "passive"))
      (node (ref "R89") (pin "2") (pinfunction "2_2") (pintype "passive"))
      (node (ref "X4") (pin "3") (pinfunction "3_3") (pintype "passive"))
    )
    (net (code "241") (name "Net-(R88-Pad1)") (class "Default")
      (node (ref "R88") (pin "1") (pinfunction "1_1") (pintype "passive"))
      (node (ref "X4") (pin "2") (pinfunction "2_2") (pintype "passive"))
    )
    (net (code "242") (name "Net-(T1-PIN1)") (class "Default")
      (node (ref "C1") (pin "2") (pinfunction "2_2") (pintype "passive"))
      (node (ref "R6") (pin "1") (pinfunction "1_1") (pintype "passive"))
      (node (ref "T1") (pin "1") (pinfunction "PIN1_1") (pintype "bidirectional"))
    )
    (net (code "243") (name "Net-(T1-PIN2)") (class "Default")
      (node (ref "R7") (pin "1") (pinfunction "1_1") (pintype "passive"))
      (node (ref "R8") (pin "1") (pinfunction "1_1") (pintype "passive"))
      (node (ref "T1") (pin "2") (pinfunction "PIN2_2") (pintype "bidirectional"))
    )
    (net (code "244") (name "Net-(T1-PIN5)") (class "Default")
      (node (ref "C4") (pin "1") (pinfunction "1_1") (pintype "passive"))
      (node (ref "C5") (pin "1") (pinfunction "1_1") (pintype "passive"))
      (node (ref "T1") (pin "5") (pinfunction "PIN5_5") (pintype "bidirectional"))
    )
    (net (code "245") (name "Net-(T1-PIN6)") (class "Default")
      (node (ref "C3") (pin "1") (pinfunction "1_1") (pintype "passive"))
      (node (ref "C5") (pin "2") (pinfunction "2_2") (pintype "passive"))
      (node (ref "T1") (pin "6") (pinfunction "PIN6_6") (pintype "bidirectional"))
    )
    (net (code "246") (name "Net-(T2-PIN1)") (class "Default")
      (node (ref "R23") (pin "1") (pinfunction "1_1") (pintype "passive"))
      (node (ref "R24") (pin "1") (pinfunction "1_1") (pintype "passive"))
      (node (ref "T2") (pin "1") (pinfunction "PIN1_1") (pintype "bidirectional"))
    )
    (net (code "247") (name "Net-(T2-PIN2)") (class "Default")
      (node (ref "C33") (pin "2") (pinfunction "2_2") (pintype "passive"))
      (node (ref "R22") (pin "1") (pinfunction "1_1") (pintype "passive"))
      (node (ref "T2") (pin "2") (pinfunction "PIN2_2") (pintype "bidirectional"))
    )
    (net (code "248") (name "Net-(T2-PIN5)") (class "Default")
      (node (ref "C36") (pin "1") (pinfunction "1_1") (pintype "passive"))
      (node (ref "C37") (pin "1") (pinfunction "1_1") (pintype "passive"))
      (node (ref "T2") (pin "5") (pinfunction "PIN5_5") (pintype "bidirectional"))
    )
    (net (code "249") (name "Net-(T2-PIN6)") (class "Default")
      (node (ref "C35") (pin "1") (pinfunction "1_1") (pintype "passive"))
      (node (ref "C37") (pin "2") (pinfunction "2_2") (pintype "passive"))
      (node (ref "T2") (pin "6") (pinfunction "PIN6_6") (pintype "bidirectional"))
    )
    (net (code "250") (name "Net-(T3-PIN1)") (class "Default")
      (node (ref "C66") (pin "2") (pinfunction "2_2") (pintype "passive"))
      (node (ref "T3") (pin "1") (pinfunction "PIN1_1") (pintype "bidirectional"))
    )
    (net (code "251") (name "Net-(T3-PIN5)") (class "Default")
      (node (ref "C68") (pin "1") (pinfunction "1_1") (pintype "passive"))
      (node (ref "C69") (pin "1") (pinfunction "1_1") (pintype "passive"))
      (node (ref "T3") (pin "5") (pinfunction "PIN5_5") (pintype "bidirectional"))
    )
    (net (code "252") (name "Net-(T3-PIN6)") (class "Default")
      (node (ref "C67") (pin "1") (pinfunction "1_1") (pintype "passive"))
      (node (ref "C69") (pin "2") (pinfunction "2_2") (pintype "passive"))
      (node (ref "T3") (pin "6") (pinfunction "PIN6_6") (pintype "bidirectional"))
    )
    (net (code "253") (name "Net-(U2A-IO_L63N_SCP6_0)") (class "Default")
      (node (ref "R109") (pin "2") (pinfunction "2_2") (pintype "passive"))
      (node (ref "U2") (pin "P118") (pinfunction "IO_L63N_SCP6_0_P118") (pintype "bidirectional"))
    )
    (net (code "254") (name "Net-(U2B-IO_L1N_VREF_1)") (class "Default")
      (node (ref "R26") (pin "2") (pinfunction "2_2") (pintype "passive"))
      (node (ref "U2") (pin "P104") (pinfunction "IO_L1N_VREF_1_P104") (pintype "bidirectional"))
    )
    (net (code "255") (name "Net-(U2B-IO_L1P_1)") (class "Default")
      (node (ref "R14") (pin "2") (pinfunction "2_2") (pintype "passive"))
      (node (ref "U2") (pin "P105") (pinfunction "IO_L1P_1_P105") (pintype "bidirectional"))
    )
    (net (code "256") (name "Net-(U2B-IO_L33N_1)") (class "Default")
      (node (ref "R42") (pin "2") (pinfunction "2_2") (pintype "passive"))
      (node (ref "U2") (pin "P99") (pinfunction "IO_L33N_1_P99") (pintype "bidirectional"))
    )
    (net (code "257") (name "Net-(U2B-IO_L40N_GCLK10_1)") (class "Default")
      (node (ref "R105") (pin "2") (pinfunction "2_2") (pintype "passive"))
      (node (ref "U2") (pin "P94") (pinfunction "IO_L40N_GCLK10_1_P94") (pintype "bidirectional"))
    )
    (net (code "258") (name "Net-(U2B-IO_L43P_GCLK5_1)") (class "Default")
      (node (ref "R106") (pin "2") (pinfunction "2_2") (pintype "passive"))
      (node (ref "U2") (pin "P85") (pinfunction "IO_L43P_GCLK5_1_P85") (pintype "bidirectional"))
    )
    (net (code "259") (name "Net-(U2B-IO_L45N_1)") (class "Default")
      (node (ref "R107") (pin "2") (pinfunction "2_2") (pintype "passive"))
      (node (ref "U2") (pin "P82") (pinfunction "IO_L45N_1_P82") (pintype "bidirectional"))
    )
    (net (code "260") (name "Net-(U2B-IO_L74P_AWAKE_1)") (class "Default")
      (node (ref "R108") (pin "2") (pinfunction "2_2") (pintype "passive"))
      (node (ref "U2") (pin "P75") (pinfunction "IO_L74P_AWAKE_1_P75") (pintype "bidirectional"))
    )
    (net (code "261") (name "Net-(U2C-DONE_2)") (class "Default")
      (node (ref "R92") (pin "1") (pinfunction "1_1") (pintype "passive"))
      (node (ref "U2") (pin "P71") (pinfunction "DONE_2_P71") (pintype "bidirectional"))
    )
    (net (code "262") (name "Net-(U2C-IO_L1P_CCLK_2)") (class "Default")
      (node (ref "U2") (pin "P70") (pinfunction "IO_L1P_CCLK_2_P70") (pintype "bidirectional"))
      (node (ref "U4") (pin "6") (pinfunction "CLK_6") (pintype "input"))
    )
    (net (code "263") (name "Net-(U2C-IO_L3N_MOSI_CSI_B_MISO0_2)") (class "Default")
      (node (ref "U2") (pin "P64") (pinfunction "IO_L3N_MOSI_CSI_B_MISO0_2_P64") (pintype "bidirectional"))
      (node (ref "U4") (pin "5") (pinfunction "DI_5") (pintype "input"))
    )
    (net (code "264") (name "Net-(U2C-IO_L3P_D0_DIN_MISO_MISO1_2)") (class "Default")
      (node (ref "R91") (pin "2") (pinfunction "2_2") (pintype "passive"))
      (node (ref "U2") (pin "P65") (pinfunction "IO_L3P_D0_DIN_MISO_MISO1_2_P65") (pintype "bidirectional"))
    )
    (net (code "265") (name "Net-(U2C-IO_L65N_CSO_B_2)") (class "Default")
      (node (ref "U2") (pin "P38") (pinfunction "IO_L65N_CSO_B_2_P38") (pintype "bidirectional"))
      (node (ref "U4") (pin "1") (pinfunction "~{CS}_1") (pintype "input"))
    )
    (net (code "266") (name "Net-(U2C-IO_L65P_INIT_B_2)") (class "Default")
      (node (ref "R93") (pin "1") (pinfunction "1_1") (pintype "passive"))
      (node (ref "U2") (pin "P39") (pinfunction "IO_L65P_INIT_B_2_P39") (pintype "bidirectional"))
    )
    (net (code "267") (name "Net-(U2C-PROGRAM_B_2)") (class "Default")
      (node (ref "R94") (pin "1") (pinfunction "1_1") (pintype "passive"))
      (node (ref "U2") (pin "P37") (pinfunction "PROGRAM_B_2_P37") (pintype "input"))
    )
    (net (code "268") (name "Net-(U2D-IO_L44N_GCLK20_3)") (class "Default")
      (node (ref "R96") (pin "2") (pinfunction "2_2") (pintype "passive"))
      (node (ref "U2") (pin "P14") (pinfunction "IO_L44N_GCLK20_3_P14") (pintype "bidirectional"))
    )
    (net (code "269") (name "Net-(U2F-TCK)") (class "Default")
      (node (ref "JTAG") (pin "1") (pinfunction "1_1") (pintype "passive"))
      (node (ref "U2") (pin "P109") (pinfunction "TCK_P109") (pintype "input"))
    )
    (net (code "270") (name "Net-(U2F-TDI)") (class "Default")
      (node (ref "JTAG") (pin "9") (pinfunction "9_9") (pintype "passive"))
      (node (ref "U2") (pin "P110") (pinfunction "TDI_P110") (pintype "input"))
    )
    (net (code "271") (name "Net-(U2F-TDO)") (class "Default")
      (node (ref "JTAG") (pin "3") (pinfunction "3_3") (pintype "passive"))
      (node (ref "U2") (pin "P106") (pinfunction "TDO_P106") (pintype "output"))
    )
    (net (code "272") (name "Net-(U2F-TMS)") (class "Default")
      (node (ref "JTAG") (pin "5") (pinfunction "5_5") (pintype "passive"))
      (node (ref "U2") (pin "P107") (pinfunction "TMS_P107") (pintype "input"))
    )
    (net (code "273") (name "Net-(U4-DO)") (class "Default")
      (node (ref "R91") (pin "1") (pinfunction "1_1") (pintype "passive"))
      (node (ref "U4") (pin "2") (pinfunction "DO_2") (pintype "output"))
    )
    (net (code "274") (name "PORT1LO1") (class "Default")
      (node (ref "C7") (pin "1") (pinfunction "1_1") (pintype "passive"))
      (node (ref "IC19") (pin "12") (pinfunction "RFOUTA_P_12") (pintype "bidirectional"))
      (node (ref "R63") (pin "1") (pinfunction "1_1") (pintype "passive"))
    )
    (net (code "275") (name "PORT1LO2") (class "Default")
      (node (ref "C15") (pin "1") (pinfunction "1_1") (pintype "passive"))
      (node (ref "C97") (pin "1") (pinfunction "1_1") (pintype "passive"))
      (node (ref "L32") (pin "2") (pinfunction "2_2") (pintype "passive"))
    )
    (net (code "276") (name "PORT1MIX_EN") (class "Default")
      (node (ref "IC1") (pin "5") (pinfunction "EN_5") (pintype "bidirectional"))
      (node (ref "IC2") (pin "2") (pinfunction "EN_2") (pintype "bidirectional"))
      (node (ref "IC3") (pin "7") (pinfunction "SHDN_7") (pintype "bidirectional"))
      (node (ref "R112") (pin "2") (pinfunction "2_2") (pintype "passive"))
      (node (ref "U2") (pin "P137") (pinfunction "IO_L4N_0_P137") (pintype "bidirectional"))
    )
    (net (code "277") (name "PORT1SRC") (class "Default")
      (node (ref "C2") (pin "1") (pinfunction "1_1") (pintype "passive"))
      (node (ref "IC26") (pin "13") (pinfunction "RF2_13") (pintype "bidirectional"))
    )
    (net (code "278") (name "PORT1_CONVSTART") (class "Default")
      (node (ref "IC4") (pin "6") (pinfunction "CONVST_6") (pintype "bidirectional"))
      (node (ref "U2") (pin "P134") (pinfunction "IO_L34P_GCLK19_0_P134") (pintype "bidirectional"))
    )
    (net (code "279") (name "PORT1_SCLK") (class "Default")
      (node (ref "IC4") (pin "8") (pinfunction "SCLK_8") (pintype "bidirectional"))
      (node (ref "U2") (pin "P132") (pinfunction "IO_L35P_GCLK17_0_P132") (pintype "bidirectional"))
    )
    (net (code "280") (name "PORT1_SDO") (class "Default")
      (node (ref "IC4") (pin "7") (pinfunction "SDO_7") (pintype "bidirectional"))
      (node (ref "U2") (pin "P133") (pinfunction "IO_L34N_GCLK18_0_P133") (pintype "bidirectional"))
    )
    (net (code "281") (name "PORT2LO1") (class "Default")
      (node (ref "C39") (pin "1") (pinfunction "1_1") (pintype "passive"))
      (node (ref "IC19") (pin "13") (pinfunction "RFOUTA_N_13") (pintype "bidirectional"))
      (node (ref "R62") (pin "1") (pinfunction "1_1") (pintype "passive"))
    )
    (net (code "282") (name "PORT2LO2") (class "Default")
      (node (ref "C100") (pin "1") (pinfunction "1_1") (pintype "passive"))
      (node (ref "C59") (pin "1") (pinfunction "1_1") (pintype "passive"))
      (node (ref "L34") (pin "2") (pinfunction "2_2") (pintype "passive"))
    )
    (net (code "283") (name "PORT2MIX_EN") (class "Default")
      (node (ref "IC5") (pin "5") (pinfunction "EN_5") (pintype "bidirectional"))
      (node (ref "IC6") (pin "2") (pinfunction "EN_2") (pintype "bidirectional"))
      (node (ref "IC7") (pin "7") (pinfunction "SHDN_7") (pintype "bidirectional"))
      (node (ref "R111") (pin "2") (pinfunction "2_2") (pintype "passive"))
      (node (ref "U2") (pin "P44") (pinfunction "IO_L62P_D5_2_P44") (pintype "bidirectional"))
    )
    (net (code "284") (name "PORT2SRC") (class "Default")
      (node (ref "C34") (pin "1") (pinfunction "1_1") (pintype "passive"))
      (node (ref "IC27") (pin "3") (pinfunction "RF1_3") (pintype "bidirectional"))
    )
    (net (code "285") (name "PORT2_CONVSTART") (class "Default")
      (node (ref "IC8") (pin "6") (pinfunction "CONVST_6") (pintype "bidirectional"))
      (node (ref "U2") (pin "P47") (pinfunction "IO_L48N_RDWR_B_VREF_2_P47") (pintype "bidirectional"))
    )
    (net (code "286") (name "PORT2_SCLK") (class "Default")
      (node (ref "IC8") (pin "8") (pinfunction "SCLK_8") (pintype "bidirectional"))
      (node (ref "U2") (pin "P45") (pinfunction "IO_L49N_D4_2_P45") (pintype "bidirectional"))
    )
    (net (code "287") (name "PORT2_SDO") (class "Default")
      (node (ref "IC8") (pin "7") (pinfunction "SDO_7") (pintype "bidirectional"))
      (node (ref "U2") (pin "P46") (pinfunction "IO_L49P_D3_2_P46") (pintype "bidirectional"))
    )
    (net (code "288") (name "PORT_SELECT") (class "Default")
      (node (ref "IC25") (pin "16") (pinfunction "CTL2_16") (pintype "bidirectional"))
      (node (ref "IC26") (pin "16") (pinfunction "CTL2_16") (pintype "bidirectional"))
      (node (ref "IC27") (pin "16") (pinfunction "CTL2_16") (pintype "bidirectional"))
      (node (ref "U2") (pin "P23") (pinfunction "IO_L41N_GCLK26_3_P23") (pintype "bidirectional"))
    )
    (net (code "289") (name "REFLO1") (class "Default")
      (node (ref "C71") (pin "1") (pinfunction "1_1") (pintype "passive"))
      (node (ref "IC19") (pin "14") (pinfunction "RFOUTB_P_14") (pintype "bidirectional"))
      (node (ref "R65") (pin "1") (pinfunction "1_1") (pintype "passive"))
    )
    (net (code "290") (name "REFLO2") (class "Default")
      (node (ref "C103") (pin "1") (pinfunction "1_1") (pintype "passive"))
      (node (ref "C91") (pin "1") (pinfunction "1_1") (pintype "passive"))
      (node (ref "L36") (pin "2") (pinfunction "2_2") (pintype "passive"))
    )
    (net (code "291") (name "REFMIX_EN") (class "Default")
      (node (ref "IC10") (pin "2") (pinfunction "EN_2") (pintype "bidirectional"))
      (node (ref "IC11") (pin "7") (pinfunction "SHDN_7") (pintype "bidirectional"))
      (node (ref "IC9") (pin "5") (pinfunction "EN_5") (pintype "bidirectional"))
      (node (ref "R113") (pin "2") (pinfunction "2_2") (pintype "passive"))
      (node (ref "U2") (pin "P35") (pinfunction "IO_L1P_3_P35") (pintype "bidirectional"))
    )
    (net (code "292") (name "REFSRC") (class "Default")
      (node (ref "C66") (pin "1") (pinfunction "1_1") (pintype "passive"))
      (node (ref "R71") (pin "1") (pinfunction "1_1") (pintype "passive"))
      (node (ref "R72") (pin "2") (pinfunction "2_2") (pintype "passive"))
    )
    (net (code "293") (name "REF_CONVSTART") (class "Default")
      (node (ref "IC12") (pin "6") (pinfunction "CONVST_6") (pintype "bidirectional"))
      (node (ref "U2") (pin "P43") (pinfunction "IO_L62N_D6_2_P43") (pintype "bidirectional"))
    )
    (net (code "294") (name "REF_SCLK") (class "Default")
      (node (ref "IC12") (pin "8") (pinfunction "SCLK_8") (pintype "bidirectional"))
      (node (ref "U2") (pin "P40") (pinfunction "IO_L64N_D9_2_P40") (pintype "bidirectional"))
    )
    (net (code "295") (name "REF_SDO") (class "Default")
      (node (ref "IC12") (pin "7") (pinfunction "SDO_7") (pintype "bidirectional"))
      (node (ref "U2") (pin "P41") (pinfunction "IO_L64P_D8_2_P41") (pintype "bidirectional"))
    )
    (net (code "296") (name "SCL") (class "Default")
      (node (ref "IC13") (pin "4") (pinfunction "SCL_4") (pintype "bidirectional"))
      (node (ref "IC33") (pin "19") (pinfunction "PA9/TIM1_CH2/I2C1_SCL/USART1_TX_19") (pintype "bidirectional"))
      (node (ref "R90") (pin "1") (pinfunction "1_1") (pintype "passive"))
      (node (ref "U2") (pin "P6") (pinfunction "IO_L52P_3_P6") (pintype "bidirectional"))
    )
    (net (code "297") (name "SDA") (class "Default")
      (node (ref "IC13") (pin "5") (pinfunction "SDA_5") (pintype "bidirectional"))
      (node (ref "IC33") (pin "20") (pinfunction "PA10/TIM1_CH3/I2C1_SDA/USART1_RX_20") (pintype "bidirectional"))
      (node (ref "R95") (pin "1") (pinfunction "1_1") (pintype "passive"))
      (node (ref "U2") (pin "P9") (pinfunction "IO_L50N_3_P9") (pintype "bidirectional"))
    )
    (net (code "298") (name "SOURCE_CE") (class "Default")
      (node (ref "IC14") (pin "4") (pinfunction "CE_4") (pintype "bidirectional"))
      (node (ref "R56") (pin "2") (pinfunction "2_2") (pintype "passive"))
      (node (ref "U2") (pin "P1") (pinfunction "IO_L83N_VREF_3_P1") (pintype "bidirectional"))
    )
    (net (code "299") (name "SOURCE_CLK") (class "Default")
      (node (ref "IC14") (pin "1") (pinfunction "CLK_1") (pintype "input"))
      (node (ref "U2") (pin "P7") (pinfunction "IO_L51N_3_P7") (pintype "bidirectional"))
    )
    (net (code "300") (name "SOURCE_HIGHBAND") (class "Default")
      (node (ref "C121") (pin "2") (pinfunction "2_2") (pintype "passive"))
      (node (ref "IC22") (pin "3") (pinfunction "RF1_3") (pintype "bidirectional"))
    )
    (net (code "301") (name "SOURCE_LD") (class "Default")
      (node (ref "IC14") (pin "25") (pinfunction "LD_25") (pintype "output"))
      (node (ref "U2") (pin "P10") (pinfunction "IO_L50P_3_P10") (pintype "bidirectional"))
    )
    (net (code "302") (name "SOURCE_LE") (class "Default")
      (node (ref "IC14") (pin "3") (pinfunction "LE_3") (pintype "input"))
      (node (ref "U2") (pin "P2") (pinfunction "IO_L83P_3_P2") (pintype "bidirectional"))
    )
    (net (code "303") (name "SOURCE_LOWBAND") (class "Default")
      (node (ref "C157") (pin "1") (pinfunction "1_1") (pintype "passive"))
      (node (ref "IC22") (pin "13") (pinfunction "RF2_13") (pintype "bidirectional"))
    )
    (net (code "304") (name "SOURCE_MOSI") (class "Default")
      (node (ref "IC14") (pin "2") (pinfunction "DATA_2") (pintype "input"))
      (node (ref "U2") (pin "P5") (pinfunction "IO_L52N_3_P5") (pintype "bidirectional"))
    )
    (net (code "305") (name "SOURCE_MUX") (class "Default")
      (node (ref "IC14") (pin "30") (pinfunction "MUX_30") (pintype "bidirectional"))
      (node (ref "U2") (pin "P8") (pinfunction "IO_L51P_3_P8") (pintype "bidirectional"))
    )
    (net (code "306") (name "SOURCE_REF") (class "Default")
      (node (ref "C130") (pin "1") (pinfunction "1_1") (pintype "passive"))
      (node (ref "IC13") (pin "8") (pinfunction "CLK3_8") (pintype "bidirectional"))
    )
    (net (code "307") (name "SOURCE_RF_EN") (class "Default")
      (node (ref "IC14") (pin "26") (pinfunction "RFOUT_EN_26") (pintype "input"))
      (node (ref "U2") (pin "P11") (pinfunction "IO_L49N_3_P11") (pintype "bidirectional"))
    )
    (net (code "308") (name "SOURCE_VCC") (class "Default")
      (node (ref "C128") (pin "1") (pinfunction "1_1") (pintype "passive"))
      (node (ref "IC14") (pin "10") (pinfunction "VCC_PLL_10") (pintype "bidirectional"))
      (node (ref "IC14") (pin "6") (pinfunction "VCC_CP_6") (pintype "bidirectional"))
      (node (ref "IC16") (pin "3") (pinfunction "VDD_3") (pintype "bidirectional"))
      (node (ref "IC18") (pin "3") (pinfunction "VDD_3") (pintype "bidirectional"))
      (node (ref "L39") (pin "2") (pinfunction "2_2") (pintype "passive"))
      (node (ref "TP17") (pin "TP") (pinfunction "TP_TP") (pintype "input"))
    )
    (net (code "309") (name "SWITCHING_SYNC") (class "Default")
      (node (ref "IC32") (pin "20") (pinfunction "ROSC_20") (pintype "bidirectional"))
      (node (ref "R78") (pin "2") (pinfunction "2_2") (pintype "passive"))
      (node (ref "U2") (pin "P62") (pinfunction "IO_L12P_D1_MISO2_2_P62") (pintype "bidirectional"))
    )
    (net (code "310") (name "VCCINT") (class "Default")
      (node (ref "C180") (pin "1") (pinfunction "1_1") (pintype "passive"))
      (node (ref "C184") (pin "1") (pinfunction "1_1") (pintype "passive"))
      (node (ref "C188") (pin "1") (pinfunction "1_1") (pintype "passive"))
      (node (ref "C208") (pin "1") (pinfunction "1_1") (pintype "passive"))
      (node (ref "C209") (pin "1") (pinfunction "1_1") (pintype "passive"))
      (node (ref "C210") (pin "1") (pinfunction "1_1") (pintype "passive"))
      (node (ref "C211") (pin "1") (pinfunction "1_1") (pintype "passive"))
      (node (ref "L54") (pin "P$2") (pinfunction "2_P$2") (pintype "passive"))
      (node (ref "R87") (pin "2") (pinfunction "2_2") (pintype "passive"))
      (node (ref "TP1") (pin "TP") (pinfunction "TP_TP") (pintype "input"))
      (node (ref "U2") (pin "P128") (pinfunction "VCCINT_P128") (pintype "input"))
      (node (ref "U2") (pin "P19") (pinfunction "VCCINT_P19") (pintype "input"))
      (node (ref "U2") (pin "P28") (pinfunction "VCCINT_P28") (pintype "input"))
      (node (ref "U2") (pin "P52") (pinfunction "VCCINT_P52") (pintype "input"))
      (node (ref "U2") (pin "P89") (pinfunction "VCCINT_P89") (pintype "input"))
    )
    (net (code "311") (name "unconnected-(IC1-TEMP-Pad1)") (class "Default")
      (node (ref "IC1") (pin "1") (pinfunction "TEMP_1") (pintype "bidirectional"))
    )
    (net (code "312") (name "unconnected-(IC5-TEMP-Pad1)") (class "Default")
      (node (ref "IC5") (pin "1") (pinfunction "TEMP_1") (pintype "bidirectional"))
    )
    (net (code "313") (name "unconnected-(IC9-TEMP-Pad1)") (class "Default")
      (node (ref "IC9") (pin "1") (pinfunction "TEMP_1") (pintype "bidirectional"))
    )
    (net (code "314") (name "unconnected-(IC13-INTR-Pad3)") (class "Default")
      (node (ref "IC13") (pin "3") (pinfunction "INTR_3") (pintype "bidirectional"))
    )
    (net (code "315") (name "unconnected-(IC14-RFOUTB_N-Pad15)") (class "Default")
      (node (ref "IC14") (pin "15") (pinfunction "RFOUTB_N_15") (pintype "bidirectional"))
    )
    (net (code "316") (name "unconnected-(IC14-RFOUTB_P-Pad14)") (class "Default")
      (node (ref "IC14") (pin "14") (pinfunction "RFOUTB_P_14") (pintype "bidirectional"))
    )
    (net (code "317") (name "unconnected-(IC22-CTL1-Pad17)") (class "Default")
      (node (ref "IC22") (pin "17") (pinfunction "CTL1_17") (pintype "bidirectional"))
    )
    (net (code "318") (name "unconnected-(IC23-CLK-Pad17)") (class "Default")
      (node (ref "IC23") (pin "17") (pinfunction "CLK_17") (pintype "bidirectional"))
    )
    (net (code "319") (name "unconnected-(IC23-DATA-Pad18)") (class "Default")
      (node (ref "IC23") (pin "18") (pinfunction "DATA_18") (pintype "bidirectional"))
    )
    (net (code "320") (name "unconnected-(IC23-LE-Pad16)") (class "Default")
      (node (ref "IC23") (pin "16") (pinfunction "LE_16") (pintype "bidirectional"))
    )
    (net (code "321") (name "unconnected-(IC25-CTL1-Pad17)") (class "Default")
      (node (ref "IC25") (pin "17") (pinfunction "CTL1_17") (pintype "bidirectional"))
    )
    (net (code "322") (name "unconnected-(IC26-CTL1-Pad17)") (class "Default")
      (node (ref "IC26") (pin "17") (pinfunction "CTL1_17") (pintype "bidirectional"))
    )
    (net (code "323") (name "unconnected-(IC26-RF1-Pad3)") (class "Default")
      (node (ref "IC26") (pin "3") (pinfunction "RF1_3") (pintype "bidirectional"))
    )
    (net (code "324") (name "unconnected-(IC27-CTL1-Pad17)") (class "Default")
      (node (ref "IC27") (pin "17") (pinfunction "CTL1_17") (pintype "bidirectional"))
    )
    (net (code "325") (name "unconnected-(IC27-RF2-Pad13)") (class "Default")
      (node (ref "IC27") (pin "13") (pinfunction "RF2_13") (pintype "bidirectional"))
    )
    (net (code "326") (name "unconnected-(IC32A-MODE-Pad8)") (class "Default")
      (node (ref "IC32") (pin "8") (pinfunction "MODE_8") (pintype "bidirectional"))
    )
    (net (code "327") (name "unconnected-(IC32A-PGOOD-Pad2)") (class "Default")
      (node (ref "IC32") (pin "2") (pinfunction "PGOOD_2") (pintype "bidirectional"))
    )
    (net (code "328") (name "unconnected-(IC32A-PG_DLY-Pad24)") (class "Default")
      (node (ref "IC32") (pin "24") (pinfunction "PG_DLY_24") (pintype "bidirectional"))
    )
    (net (code "329") (name "unconnected-(IC32A-SEQ_DLY-Pad17)") (class "Default")
      (node (ref "IC32") (pin "17") (pinfunction "SEQ_DLY_17") (pintype "bidirectional"))
    )
    (net (code "330") (name "unconnected-(IC32B-EN-Pad3)") (class "Default")
      (node (ref "IC32") (pin "3") (pinfunction "EN_3") (pintype "bidirectional"))
    )
    (net (code "331") (name "unconnected-(IC32C-EN-Pad4)") (class "Default")
      (node (ref "IC32") (pin "4") (pinfunction "EN_4") (pintype "bidirectional"))
    )
    (net (code "332") (name "unconnected-(IC32D-EN-Pad5)") (class "Default")
      (node (ref "IC32") (pin "5") (pinfunction "EN_5") (pintype "bidirectional"))
    )
    (net (code "333") (name "unconnected-(IC33-PA3{slash}TIM2_CH4{slash}USART2_RX-Pad9)") (class "Default")
      (node (ref "IC33") (pin "9") (pinfunction "PA3/TIM2_CH4/USART2_RX_9") (pintype "bidirectional"))
    )
    (net (code "334") (name "unconnected-(IC33-PA4{slash}SPI1_NSS{slash}SPI3_NSS-Pad10)") (class "Default")
      (node (ref "IC33") (pin "10") (pinfunction "PA4/SPI1_NSS/SPI3_NSS_10") (pintype "bidirectional"))
    )
    (net (code "335") (name "unconnected-(IC33-PA5{slash}TIM2_CH1{slash}SPI1_SCK-Pad11)") (class "Default")
      (node (ref "IC33") (pin "11") (pinfunction "PA5/TIM2_CH1/SPI1_SCK_11") (pintype "bidirectional"))
    )
    (net (code "336") (name "unconnected-(IC33-PA6{slash}SPI1_MISO{slash}TIM16_CH1-Pad12)") (class "Default")
      (node (ref "IC33") (pin "12") (pinfunction "PA6/SPI1_MISO/TIM16_CH1_12") (pintype "bidirectional"))
    )
    (net (code "337") (name "unconnected-(IC33-PA7{slash}I2C3_SCL{slash}SPI1_MOSI-Pad13)") (class "Default")
      (node (ref "IC33") (pin "13") (pinfunction "PA7/I2C3_SCL/SPI1_MOSI_13") (pintype "bidirectional"))
    )
    (net (code "338") (name "unconnected-(IC33-PA8{slash}TIM1_CH1-Pad18)") (class "Default")
      (node (ref "IC33") (pin "18") (pinfunction "PA8/TIM1_CH1_18") (pintype "bidirectional"))
    )
    (net (code "339") (name "unconnected-(IC33-PB0{slash}SPI1_NSS-Pad14)") (class "Default")
      (node (ref "IC33") (pin "14") (pinfunction "PB0/SPI1_NSS_14") (pintype "bidirectional"))
    )
    (net (code "340") (name "unconnected-(IC33-PB1-Pad15)") (class "Default")
      (node (ref "IC33") (pin "15") (pinfunction "PB1_15") (pintype "bidirectional"))
    )
    (net (code "341") (name "unconnected-(J3-Pad2)") (class "Default")
      (node (ref "J3") (pin "2") (pinfunction "2_2") (pintype "passive"))
    )
    (net (code "342") (name "unconnected-(JTAG-Pad6)") (class "Default")
      (node (ref "JTAG") (pin "6") (pinfunction "6_6") (pintype "passive"))
    )
    (net (code "343") (name "unconnected-(JTAG-Pad7)") (class "Default")
      (node (ref "JTAG") (pin "7") (pinfunction "7_7") (pintype "passive"))
    )
    (net (code "344") (name "unconnected-(JTAG-Pad8)") (class "Default")
      (node (ref "JTAG") (pin "8") (pinfunction "8_8") (pintype "passive"))
    )
    (net (code "345") (name "unconnected-(U2A-IO_L35N_GCLK16_0-PadP131)") (class "Default")
      (node (ref "U2") (pin "P131") (pinfunction "IO_L35N_GCLK16_0_P131") (pintype "bidirectional"))
    )
    (net (code "346") (name "unconnected-(U2A-IO_L36N_GCLK14_0-PadP126)") (class "Default")
      (node (ref "U2") (pin "P126") (pinfunction "IO_L36N_GCLK14_0_P126") (pintype "bidirectional"))
    )
    (net (code "347") (name "unconnected-(U2A-IO_L36P_GCLK15_0-PadP127)") (class "Default")
      (node (ref "U2") (pin "P127") (pinfunction "IO_L36P_GCLK15_0_P127") (pintype "bidirectional"))
    )
    (net (code "348") (name "unconnected-(U2A-IO_L37N_GCLK12_0-PadP123)") (class "Default")
      (node (ref "U2") (pin "P123") (pinfunction "IO_L37N_GCLK12_0_P123") (pintype "bidirectional"))
    )
    (net (code "349") (name "unconnected-(U2A-IO_L37P_GCLK13_0-PadP124)") (class "Default")
      (node (ref "U2") (pin "P124") (pinfunction "IO_L37P_GCLK13_0_P124") (pintype "bidirectional"))
    )
    (net (code "350") (name "unconnected-(U2A-IO_L62N_VREF_0-PadP120)") (class "Default")
      (node (ref "U2") (pin "P120") (pinfunction "IO_L62N_VREF_0_P120") (pintype "bidirectional"))
    )
    (net (code "351") (name "unconnected-(U2A-IO_L62P_0-PadP121)") (class "Default")
      (node (ref "U2") (pin "P121") (pinfunction "IO_L62P_0_P121") (pintype "bidirectional"))
    )
    (net (code "352") (name "unconnected-(U2A-IO_L63P_SCP7_0-PadP119)") (class "Default")
      (node (ref "U2") (pin "P119") (pinfunction "IO_L63P_SCP7_0_P119") (pintype "bidirectional"))
    )
    (net (code "353") (name "unconnected-(U2A-IO_L64N_SCP4_0-PadP116)") (class "Default")
      (node (ref "U2") (pin "P116") (pinfunction "IO_L64N_SCP4_0_P116") (pintype "bidirectional"))
    )
    (net (code "354") (name "unconnected-(U2A-IO_L64P_SCP5_0-PadP117)") (class "Default")
      (node (ref "U2") (pin "P117") (pinfunction "IO_L64P_SCP5_0_P117") (pintype "bidirectional"))
    )
    (net (code "355") (name "unconnected-(U2A-IO_L65N_SCP2_0-PadP114)") (class "Default")
      (node (ref "U2") (pin "P114") (pinfunction "IO_L65N_SCP2_0_P114") (pintype "bidirectional"))
    )
    (net (code "356") (name "unconnected-(U2A-IO_L65P_SCP3_0-PadP115)") (class "Default")
      (node (ref "U2") (pin "P115") (pinfunction "IO_L65P_SCP3_0_P115") (pintype "bidirectional"))
    )
    (net (code "357") (name "unconnected-(U2A-IO_L66N_SCP0_0-PadP111)") (class "Default")
      (node (ref "U2") (pin "P111") (pinfunction "IO_L66N_SCP0_0_P111") (pintype "bidirectional"))
    )
    (net (code "358") (name "unconnected-(U2A-IO_L66P_SCP1_0-PadP112)") (class "Default")
      (node (ref "U2") (pin "P112") (pinfunction "IO_L66P_SCP1_0_P112") (pintype "bidirectional"))
    )
    (net (code "359") (name "unconnected-(U2B-IO_L32N_1-PadP101)") (class "Default")
      (node (ref "U2") (pin "P101") (pinfunction "IO_L32N_1_P101") (pintype "bidirectional"))
    )
    (net (code "360") (name "unconnected-(U2B-IO_L32P_1-PadP102)") (class "Default")
      (node (ref "U2") (pin "P102") (pinfunction "IO_L32P_1_P102") (pintype "bidirectional"))
    )
    (net (code "361") (name "unconnected-(U2B-IO_L33P_1-PadP100)") (class "Default")
      (node (ref "U2") (pin "P100") (pinfunction "IO_L33P_1_P100") (pintype "bidirectional"))
    )
    (net (code "362") (name "unconnected-(U2B-IO_L34N_1-PadP97)") (class "Default")
      (node (ref "U2") (pin "P97") (pinfunction "IO_L34N_1_P97") (pintype "bidirectional"))
    )
    (net (code "363") (name "unconnected-(U2B-IO_L34P_1-PadP98)") (class "Default")
      (node (ref "U2") (pin "P98") (pinfunction "IO_L34P_1_P98") (pintype "bidirectional"))
    )
    (net (code "364") (name "unconnected-(U2B-IO_L40P_GCLK11_1-PadP95)") (class "Default")
      (node (ref "U2") (pin "P95") (pinfunction "IO_L40P_GCLK11_1_P95") (pintype "bidirectional"))
    )
    (net (code "365") (name "unconnected-(U2B-IO_L41N_GCLK8_1-PadP92)") (class "Default")
      (node (ref "U2") (pin "P92") (pinfunction "IO_L41N_GCLK8_1_P92") (pintype "bidirectional"))
    )
    (net (code "366") (name "unconnected-(U2B-IO_L41P_GCLK9_IRDY1_1-PadP93)") (class "Default")
      (node (ref "U2") (pin "P93") (pinfunction "IO_L41P_GCLK9_IRDY1_1_P93") (pintype "bidirectional"))
    )
    (net (code "367") (name "unconnected-(U2B-IO_L42N_GCLK6_TRDY1_1-PadP87)") (class "Default")
      (node (ref "U2") (pin "P87") (pinfunction "IO_L42N_GCLK6_TRDY1_1_P87") (pintype "bidirectional"))
    )
    (net (code "368") (name "unconnected-(U2B-IO_L42P_GCLK7_1-PadP88)") (class "Default")
      (node (ref "U2") (pin "P88") (pinfunction "IO_L42P_GCLK7_1_P88") (pintype "bidirectional"))
    )
    (net (code "369") (name "unconnected-(U2B-IO_L43N_GCLK4_1-PadP84)") (class "Default")
      (node (ref "U2") (pin "P84") (pinfunction "IO_L43N_GCLK4_1_P84") (pintype "bidirectional"))
    )
    (net (code "370") (name "unconnected-(U2B-IO_L45P_1-PadP83)") (class "Default")
      (node (ref "U2") (pin "P83") (pinfunction "IO_L45P_1_P83") (pintype "bidirectional"))
    )
    (net (code "371") (name "unconnected-(U2B-IO_L46N_1-PadP80)") (class "Default")
      (node (ref "U2") (pin "P80") (pinfunction "IO_L46N_1_P80") (pintype "bidirectional"))
    )
    (net (code "372") (name "unconnected-(U2B-IO_L46P_1-PadP81)") (class "Default")
      (node (ref "U2") (pin "P81") (pinfunction "IO_L46P_1_P81") (pintype "bidirectional"))
    )
    (net (code "373") (name "unconnected-(U2B-IO_L47N_1-PadP78)") (class "Default")
      (node (ref "U2") (pin "P78") (pinfunction "IO_L47N_1_P78") (pintype "bidirectional"))
    )
    (net (code "374") (name "unconnected-(U2B-IO_L47P_1-PadP79)") (class "Default")
      (node (ref "U2") (pin "P79") (pinfunction "IO_L47P_1_P79") (pintype "bidirectional"))
    )
    (net (code "375") (name "unconnected-(U2B-IO_L74N_DOUT_BUSY_1-PadP74)") (class "Default")
      (node (ref "U2") (pin "P74") (pinfunction "IO_L74N_DOUT_BUSY_1_P74") (pintype "bidirectional"))
    )
    (net (code "376") (name "unconnected-(U2C-CMPCS_B_2-PadP72)") (class "Default")
      (node (ref "U2") (pin "P72") (pinfunction "CMPCS_B_2_P72") (pintype "bidirectional"))
    )
    (net (code "377") (name "unconnected-(U2C-IO_L2N_CMPMOSI_2-PadP66)") (class "Default")
      (node (ref "U2") (pin "P66") (pinfunction "IO_L2N_CMPMOSI_2_P66") (pintype "bidirectional"))
    )
    (net (code "378") (name "unconnected-(U2C-IO_L2P_CMPCLK_2-PadP67)") (class "Default")
      (node (ref "U2") (pin "P67") (pinfunction "IO_L2P_CMPCLK_2_P67") (pintype "bidirectional"))
    )
    (net (code "379") (name "unconnected-(U2D-IO_L49P_3-PadP12)") (class "Default")
      (node (ref "U2") (pin "P12") (pinfunction "IO_L49P_3_P12") (pintype "bidirectional"))
    )
    (net (code "380") (name "unconnected-(X4-Pad1)") (class "Default")
      (node (ref "X4") (pin "1") (pinfunction "1_1") (pintype "passive"))
    )
    (net (code "381") (name "unconnected-(X4-Pad4)") (class "Default")
      (node (ref "X4") (pin "4") (pinfunction "4_4") (pintype "passive"))
    )
  )
)
